# MT-PowerDispatch_V1_0_0.net
KiCad netlist of a schematic drawn in Altium Designer
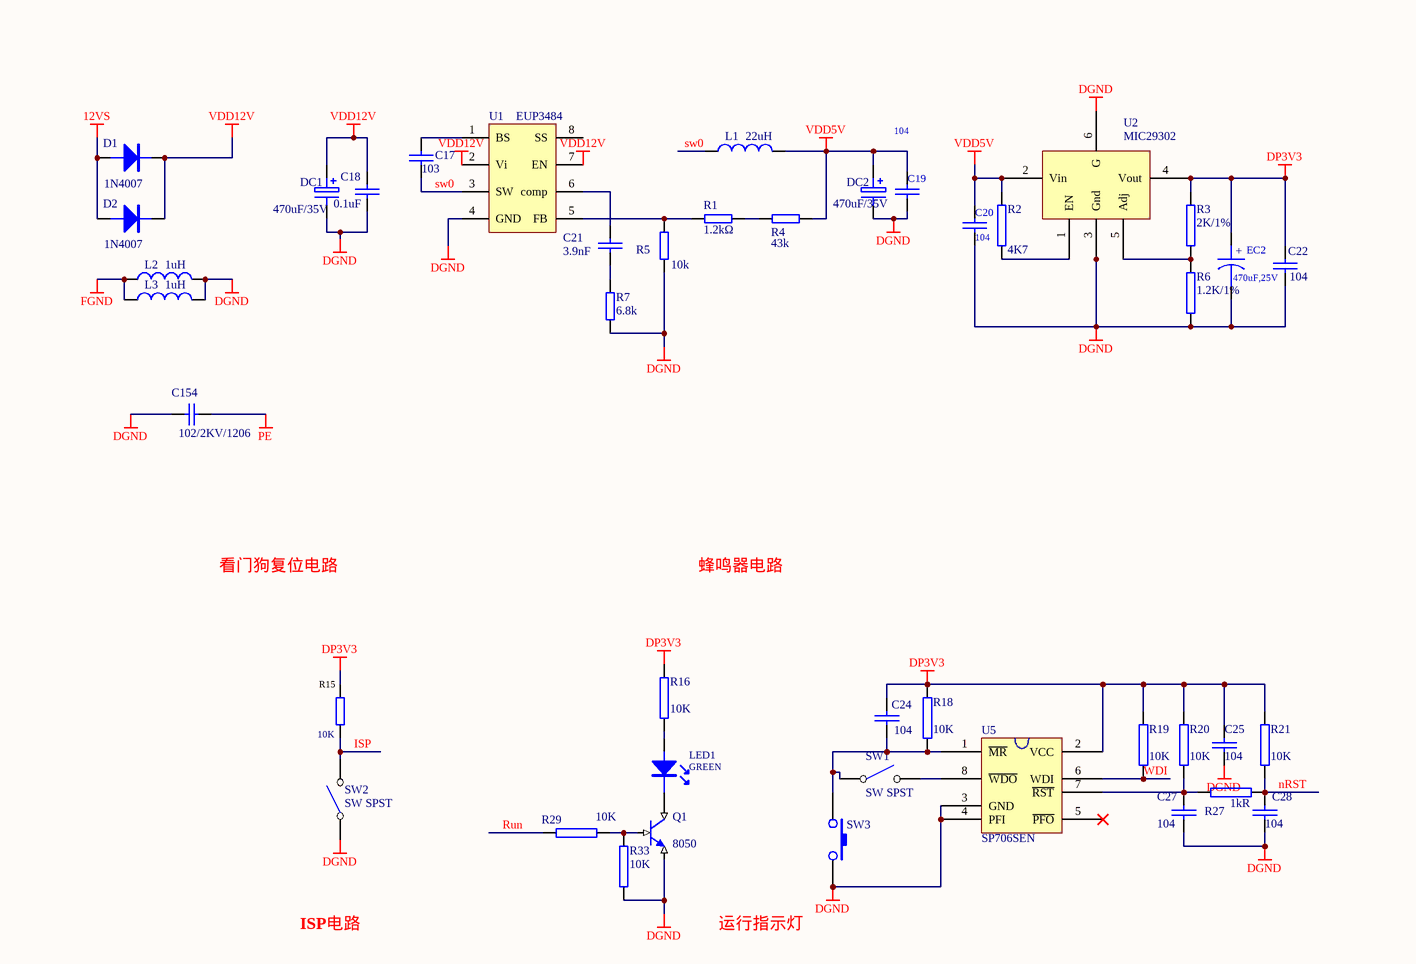
[diagram p0: MT-PowerDispatch V1.0.0.SchDoc, top left]
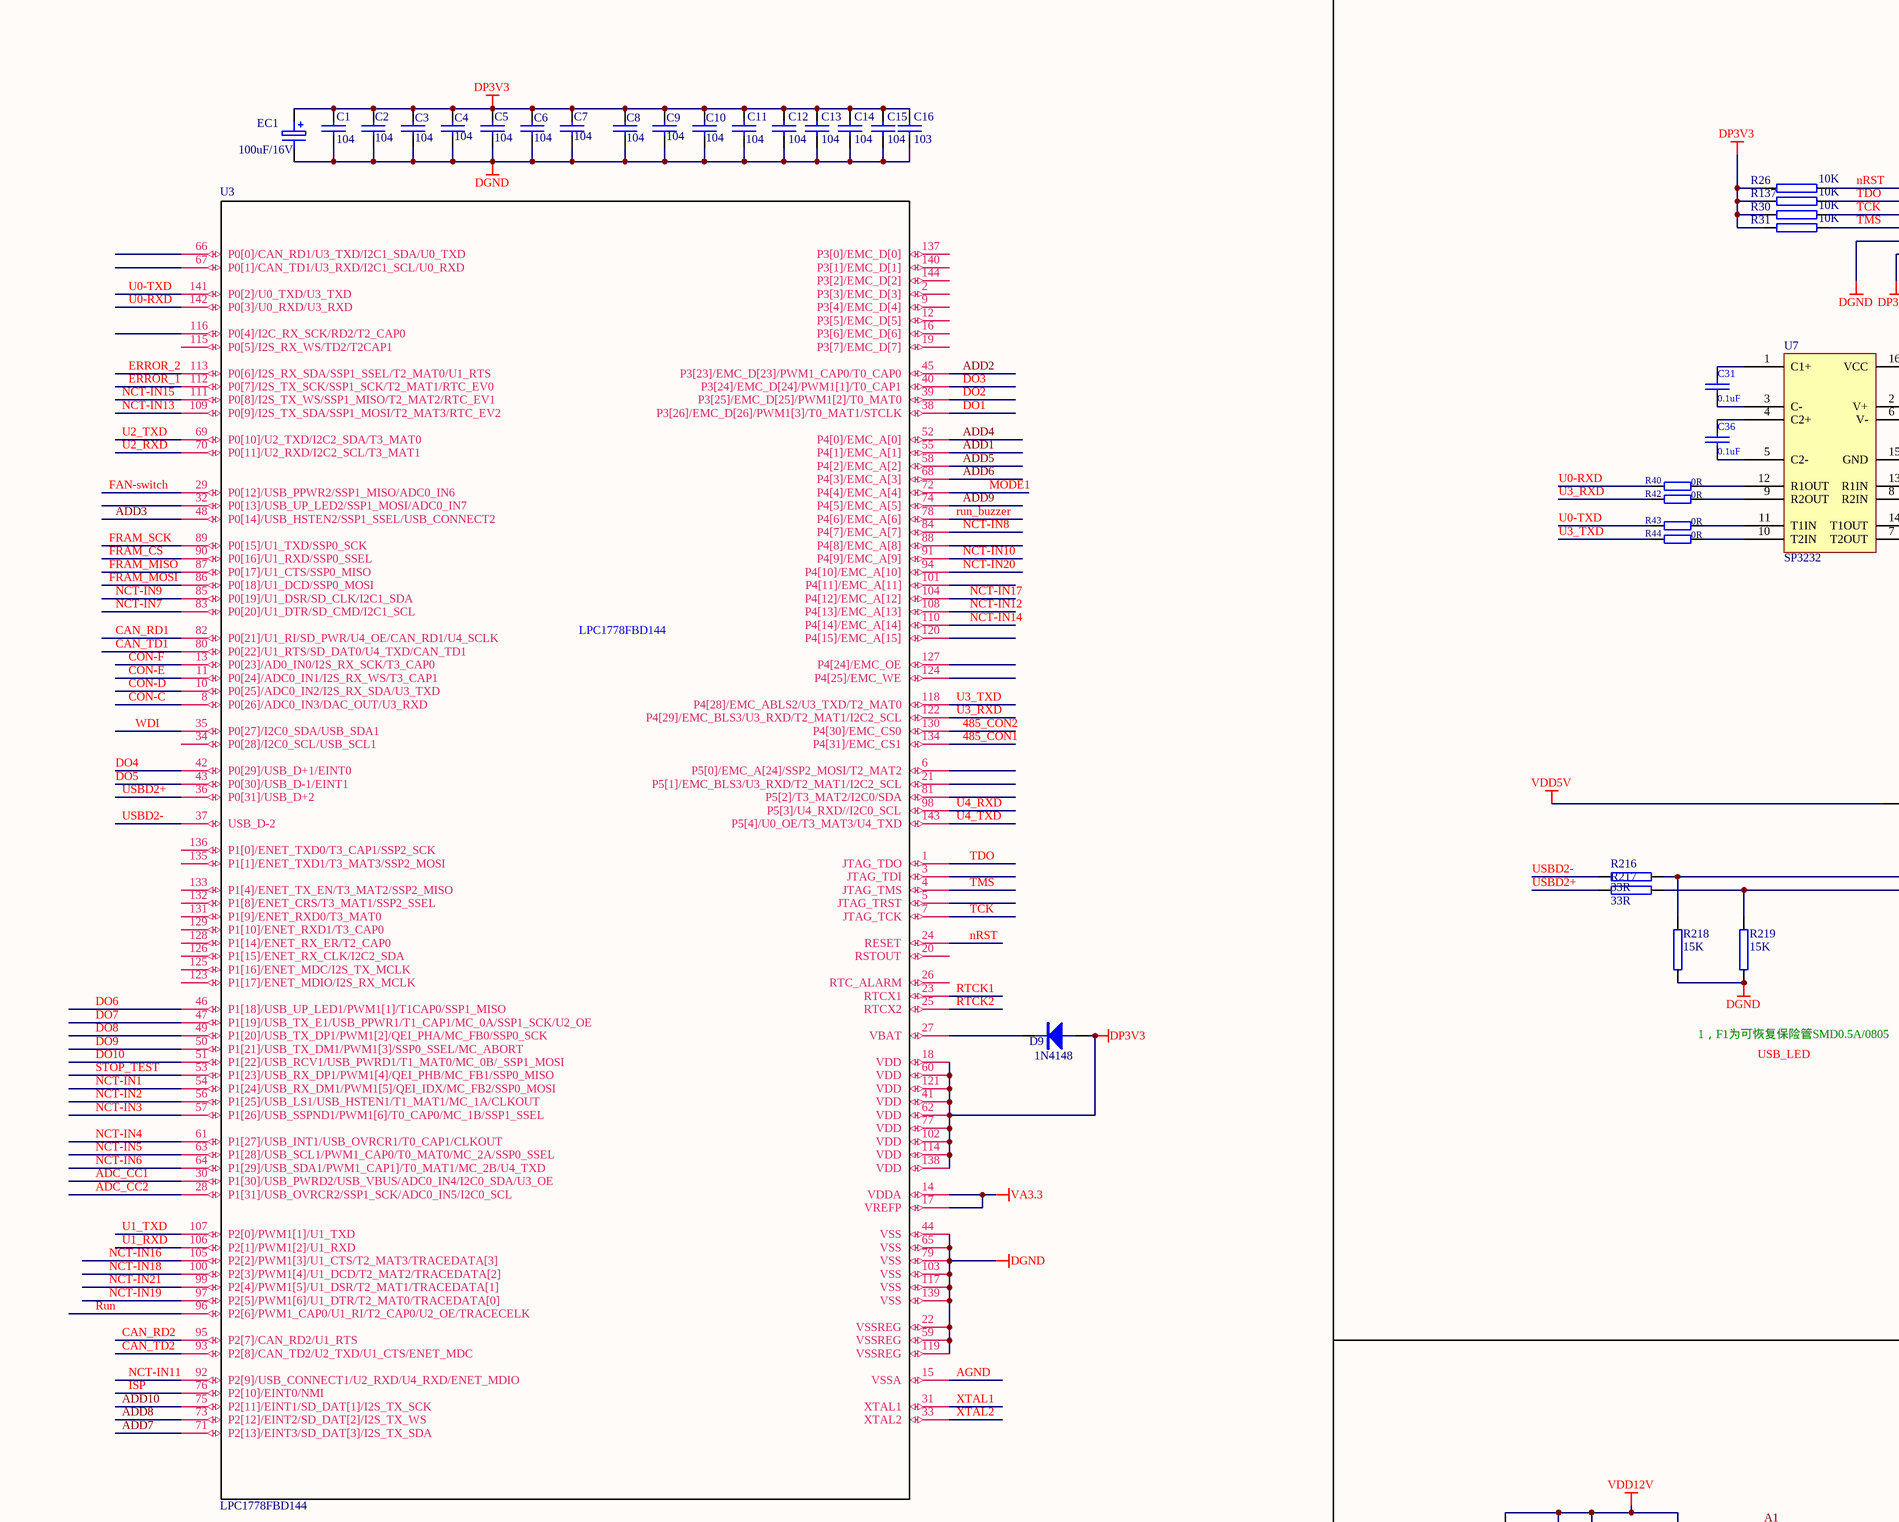
[diagram p1: MT-PowerDispatch V1.0.0.SchDoc, top middle]
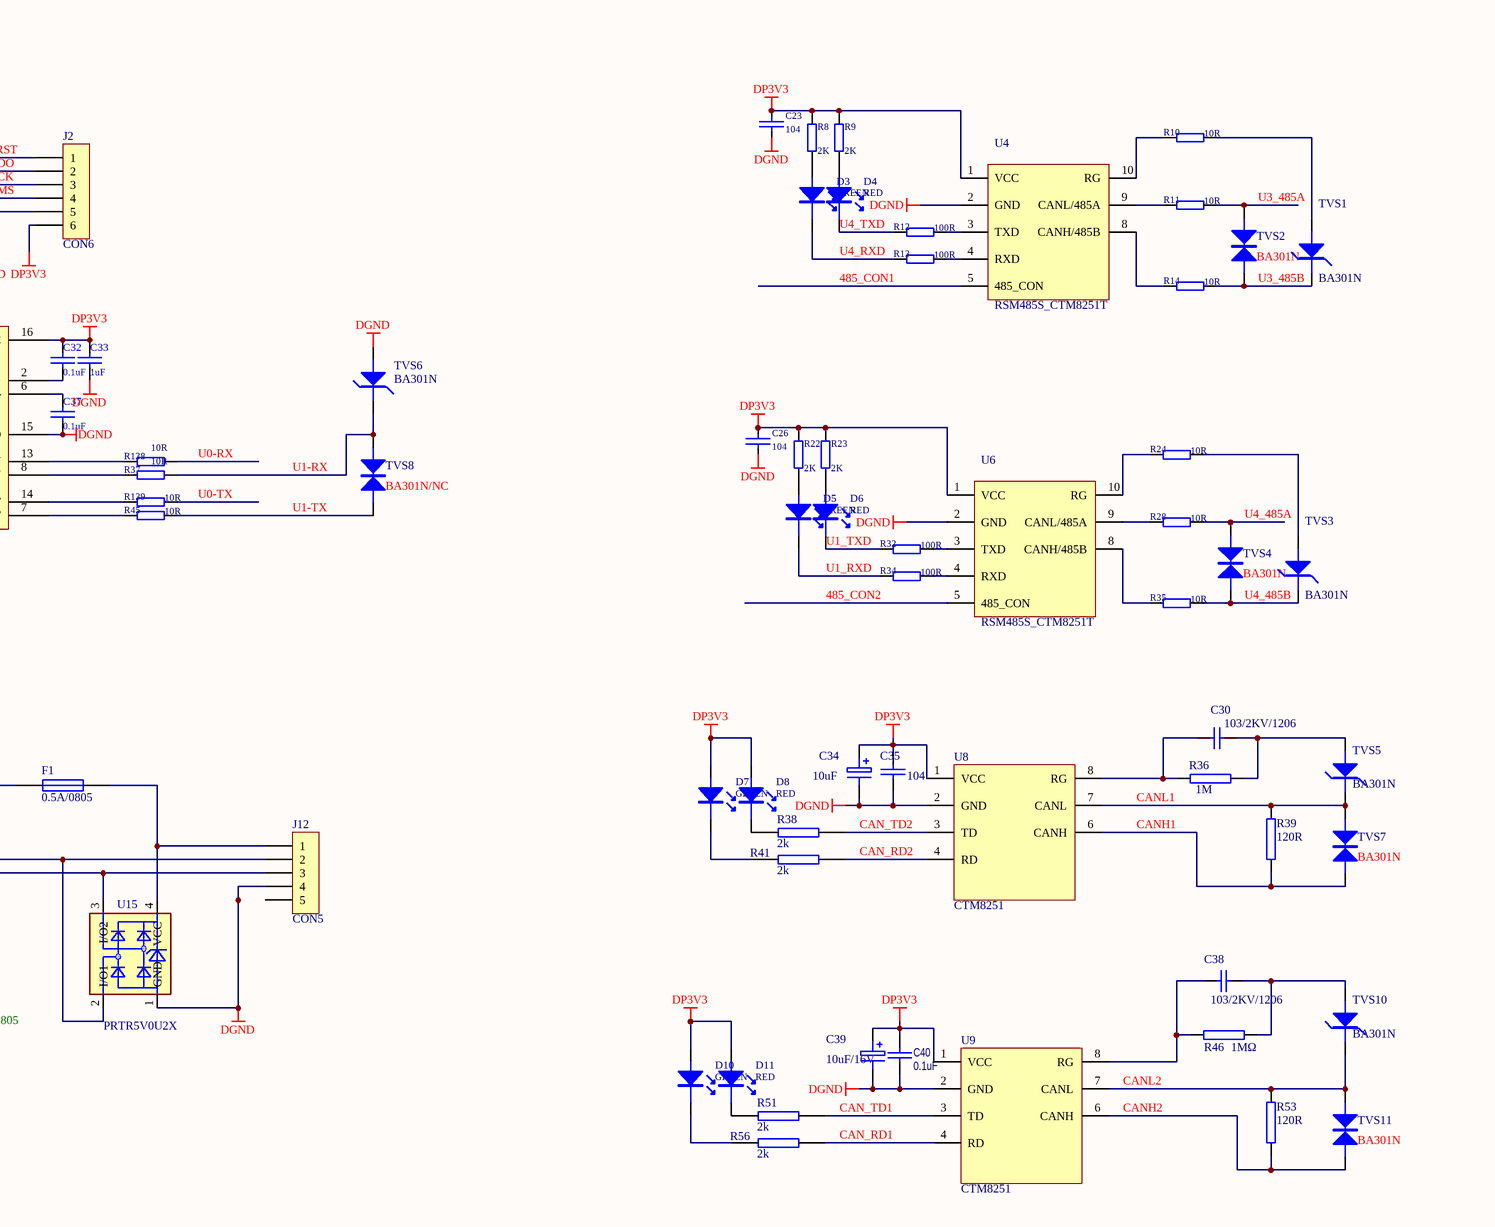
[diagram p2: MT-PowerDispatch V1.0.0.SchDoc, top right]
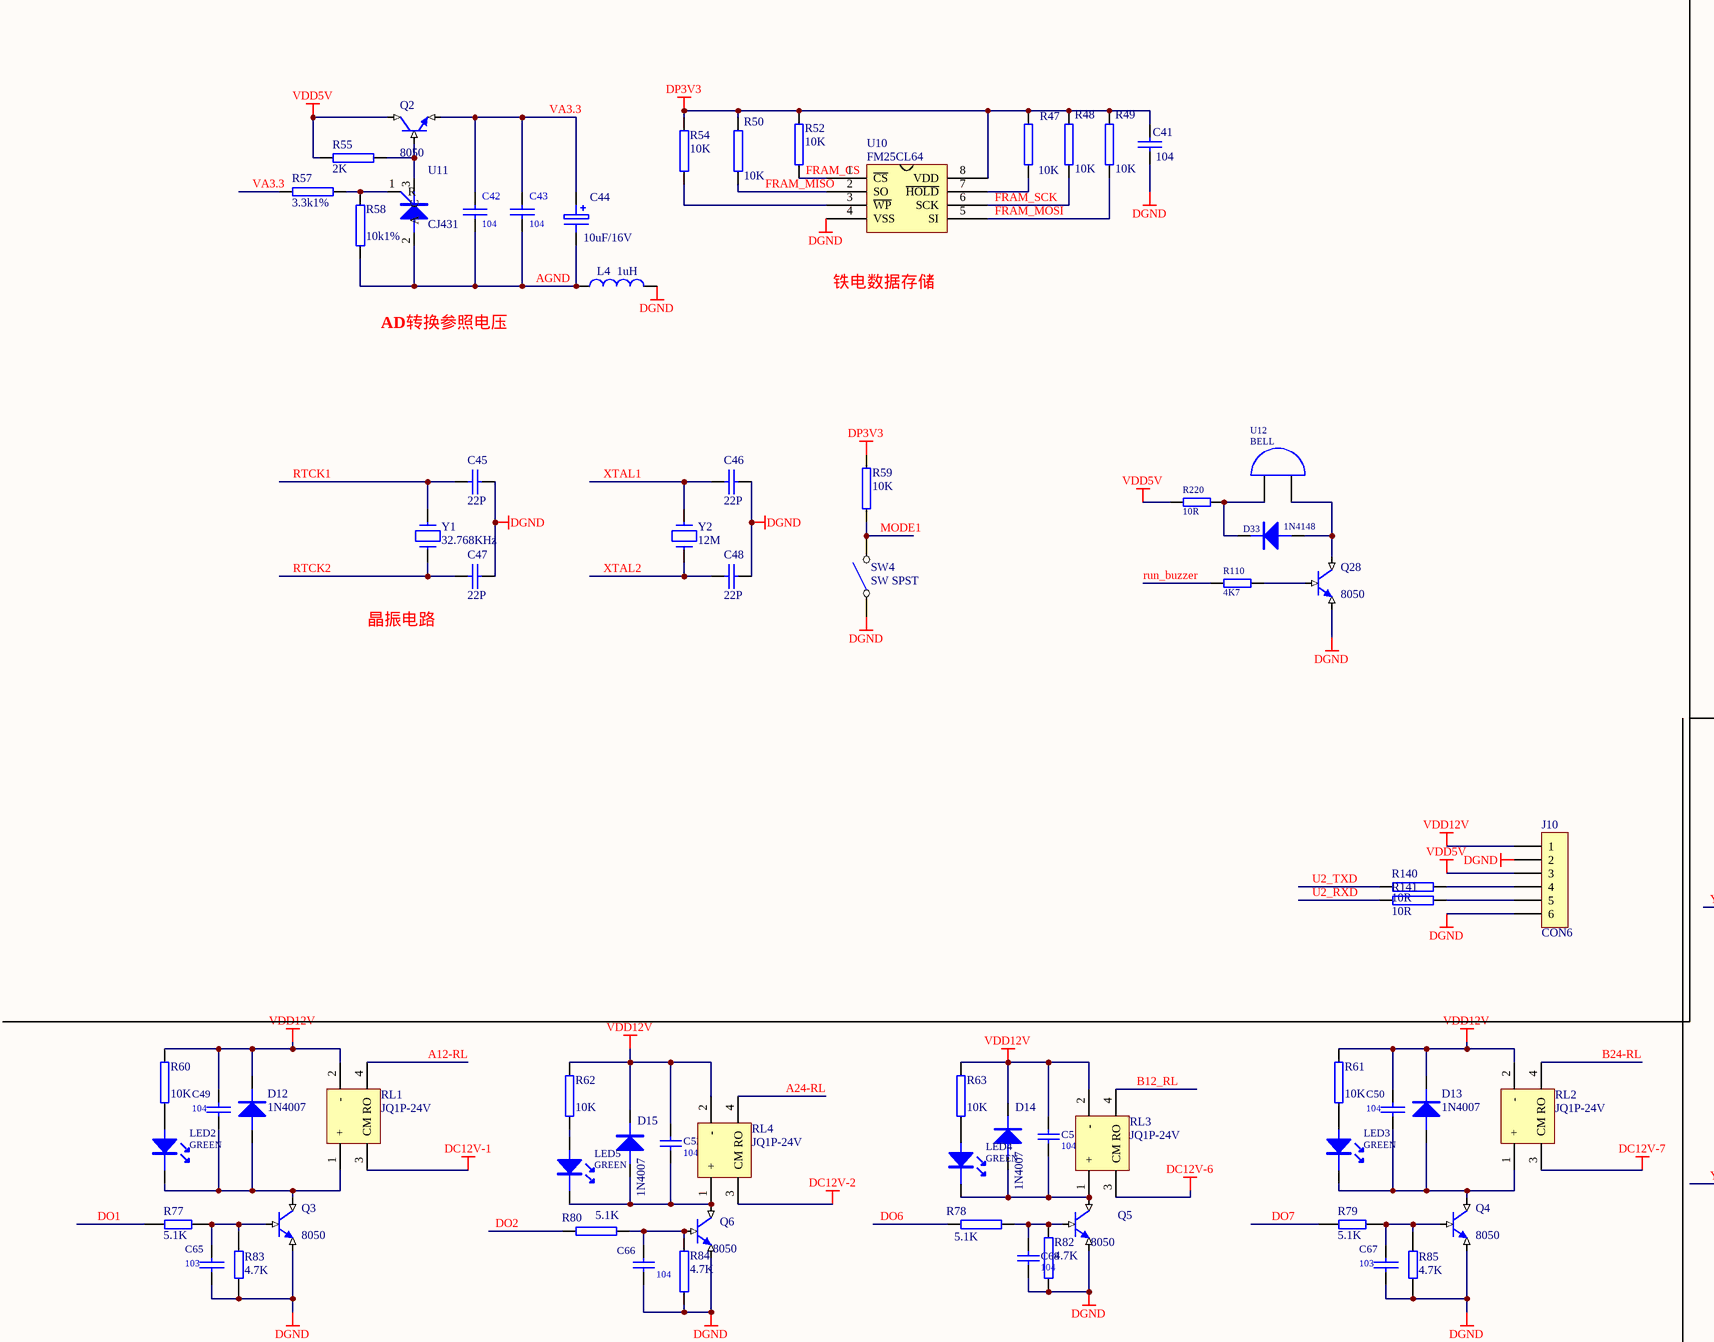
[diagram p3: MT-PowerDispatch V1.0.0.SchDoc, centre left]
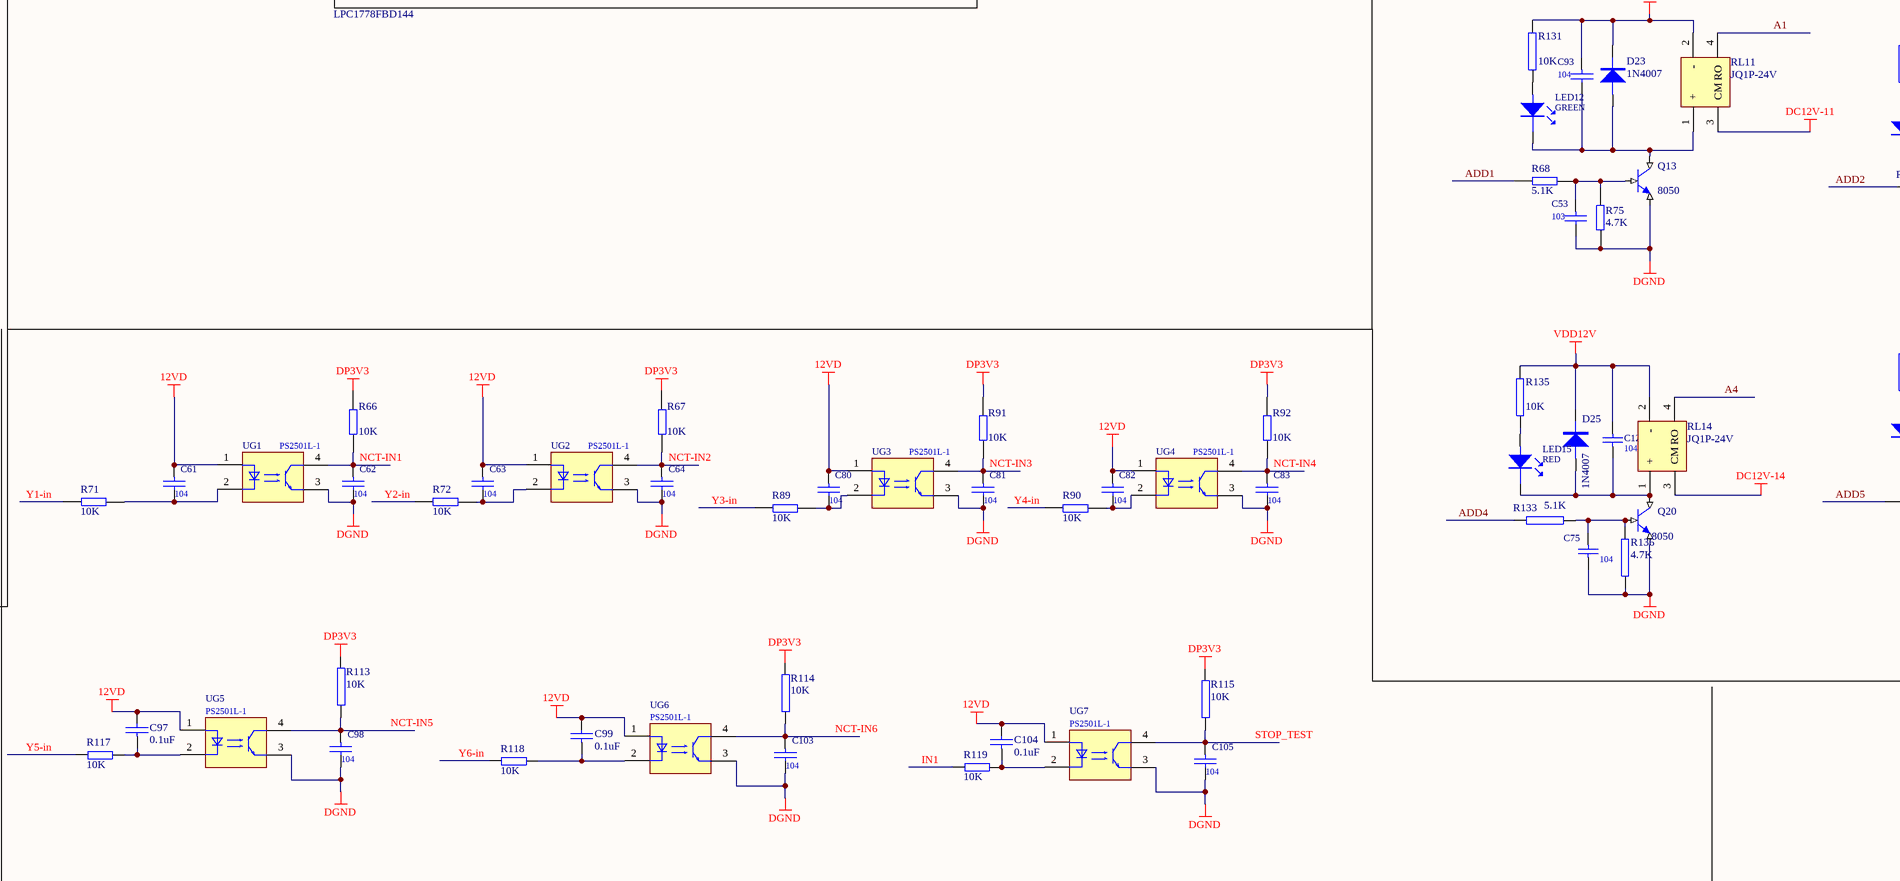
[diagram p4: MT-PowerDispatch V1.0.0.SchDoc, centre middle]
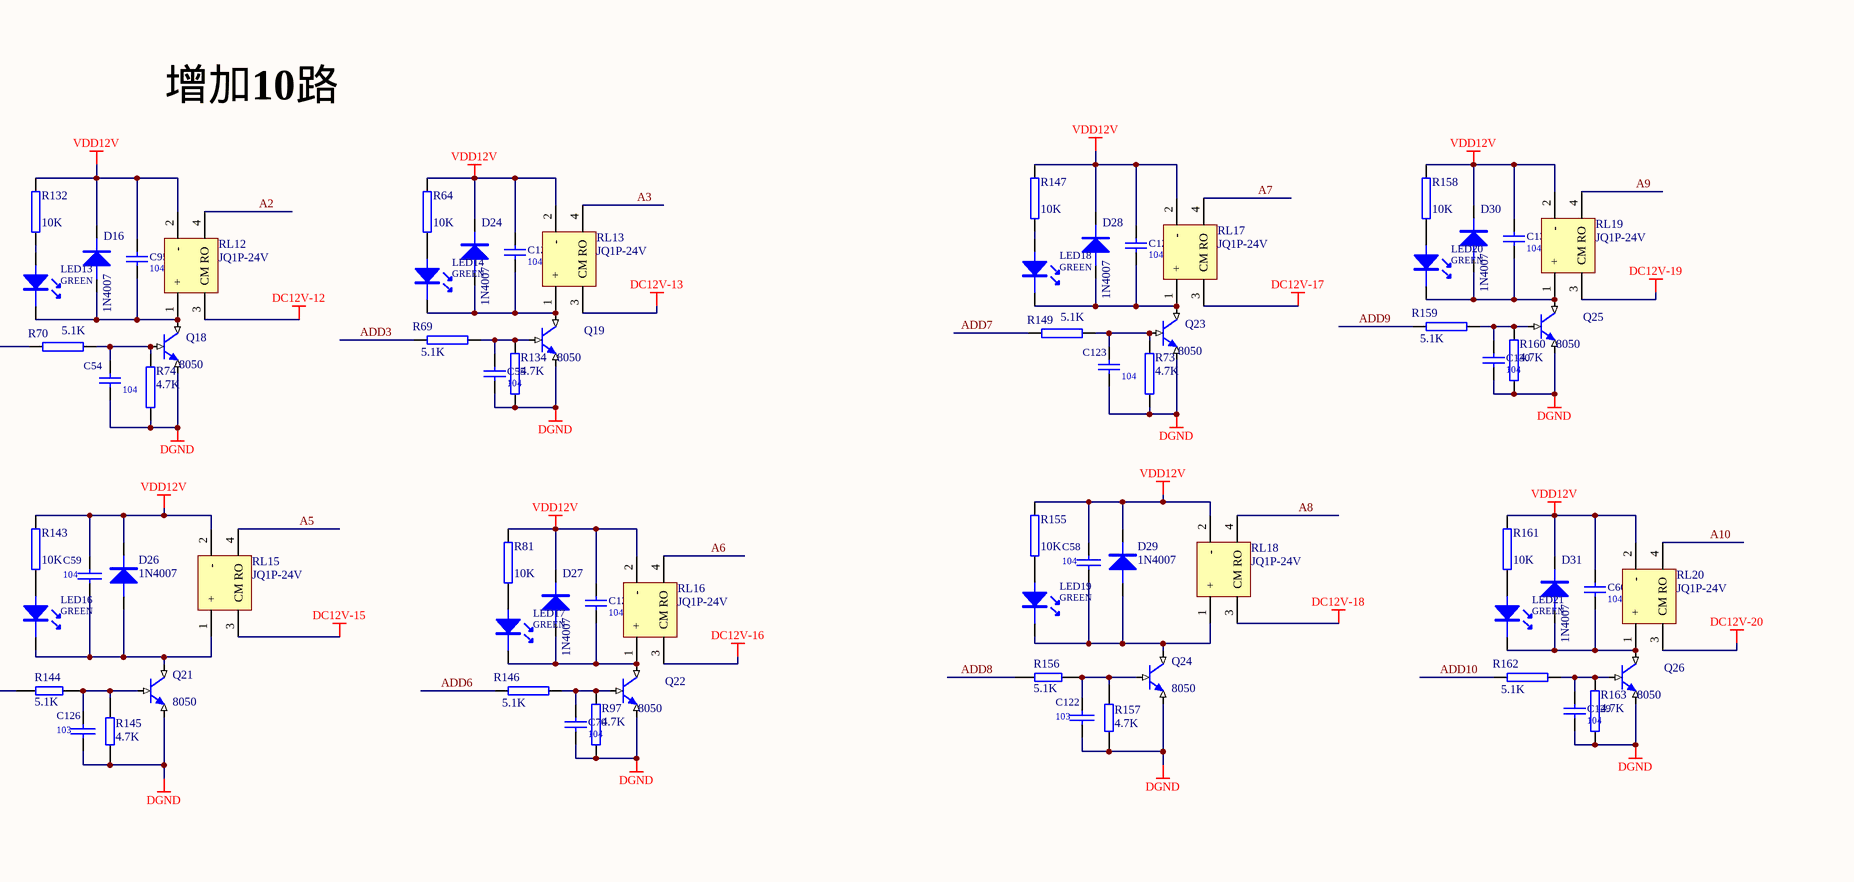
[diagram p5: MT-PowerDispatch V1.0.0.SchDoc, centre right]
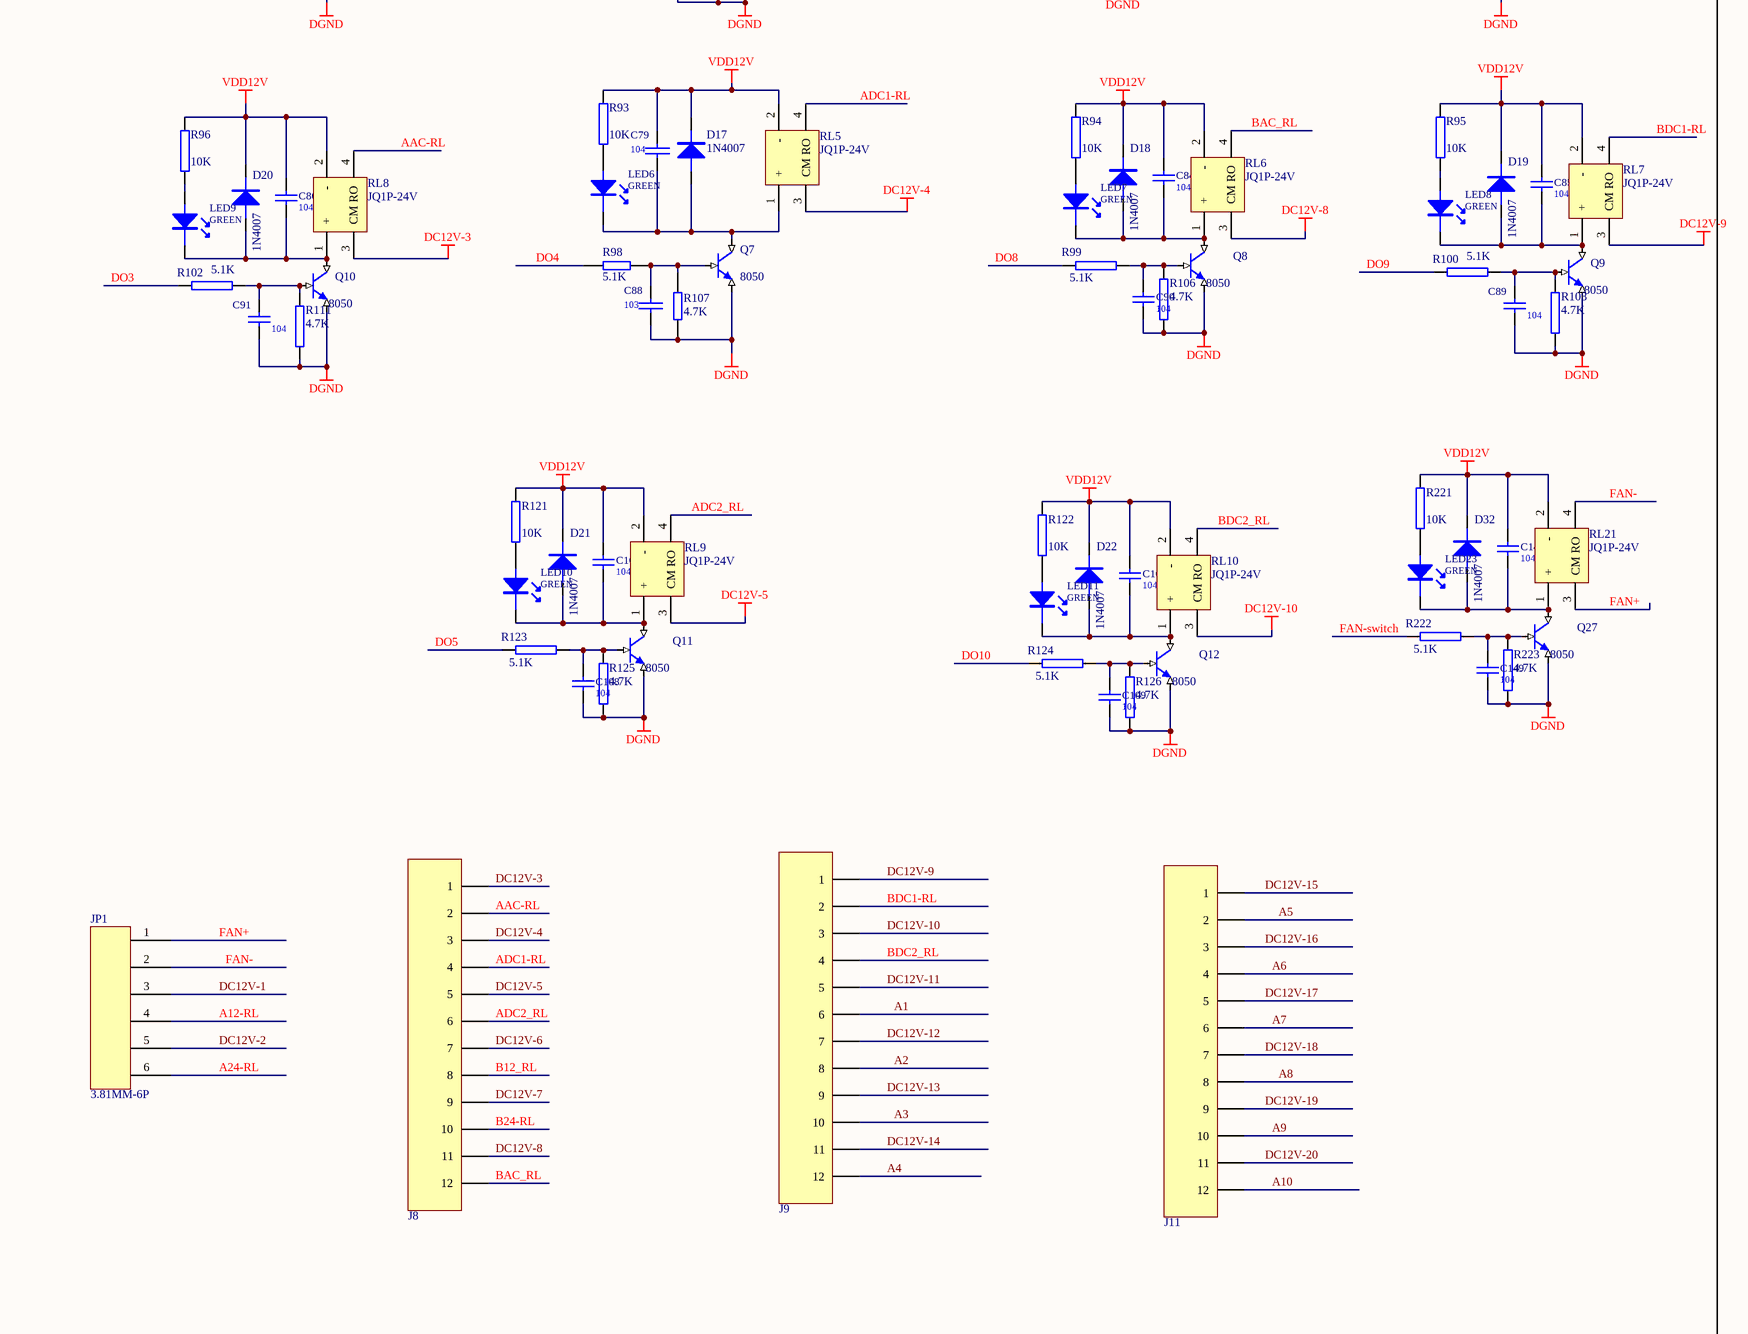
[diagram p6: MT-PowerDispatch V1.0.0.SchDoc, bottom left]
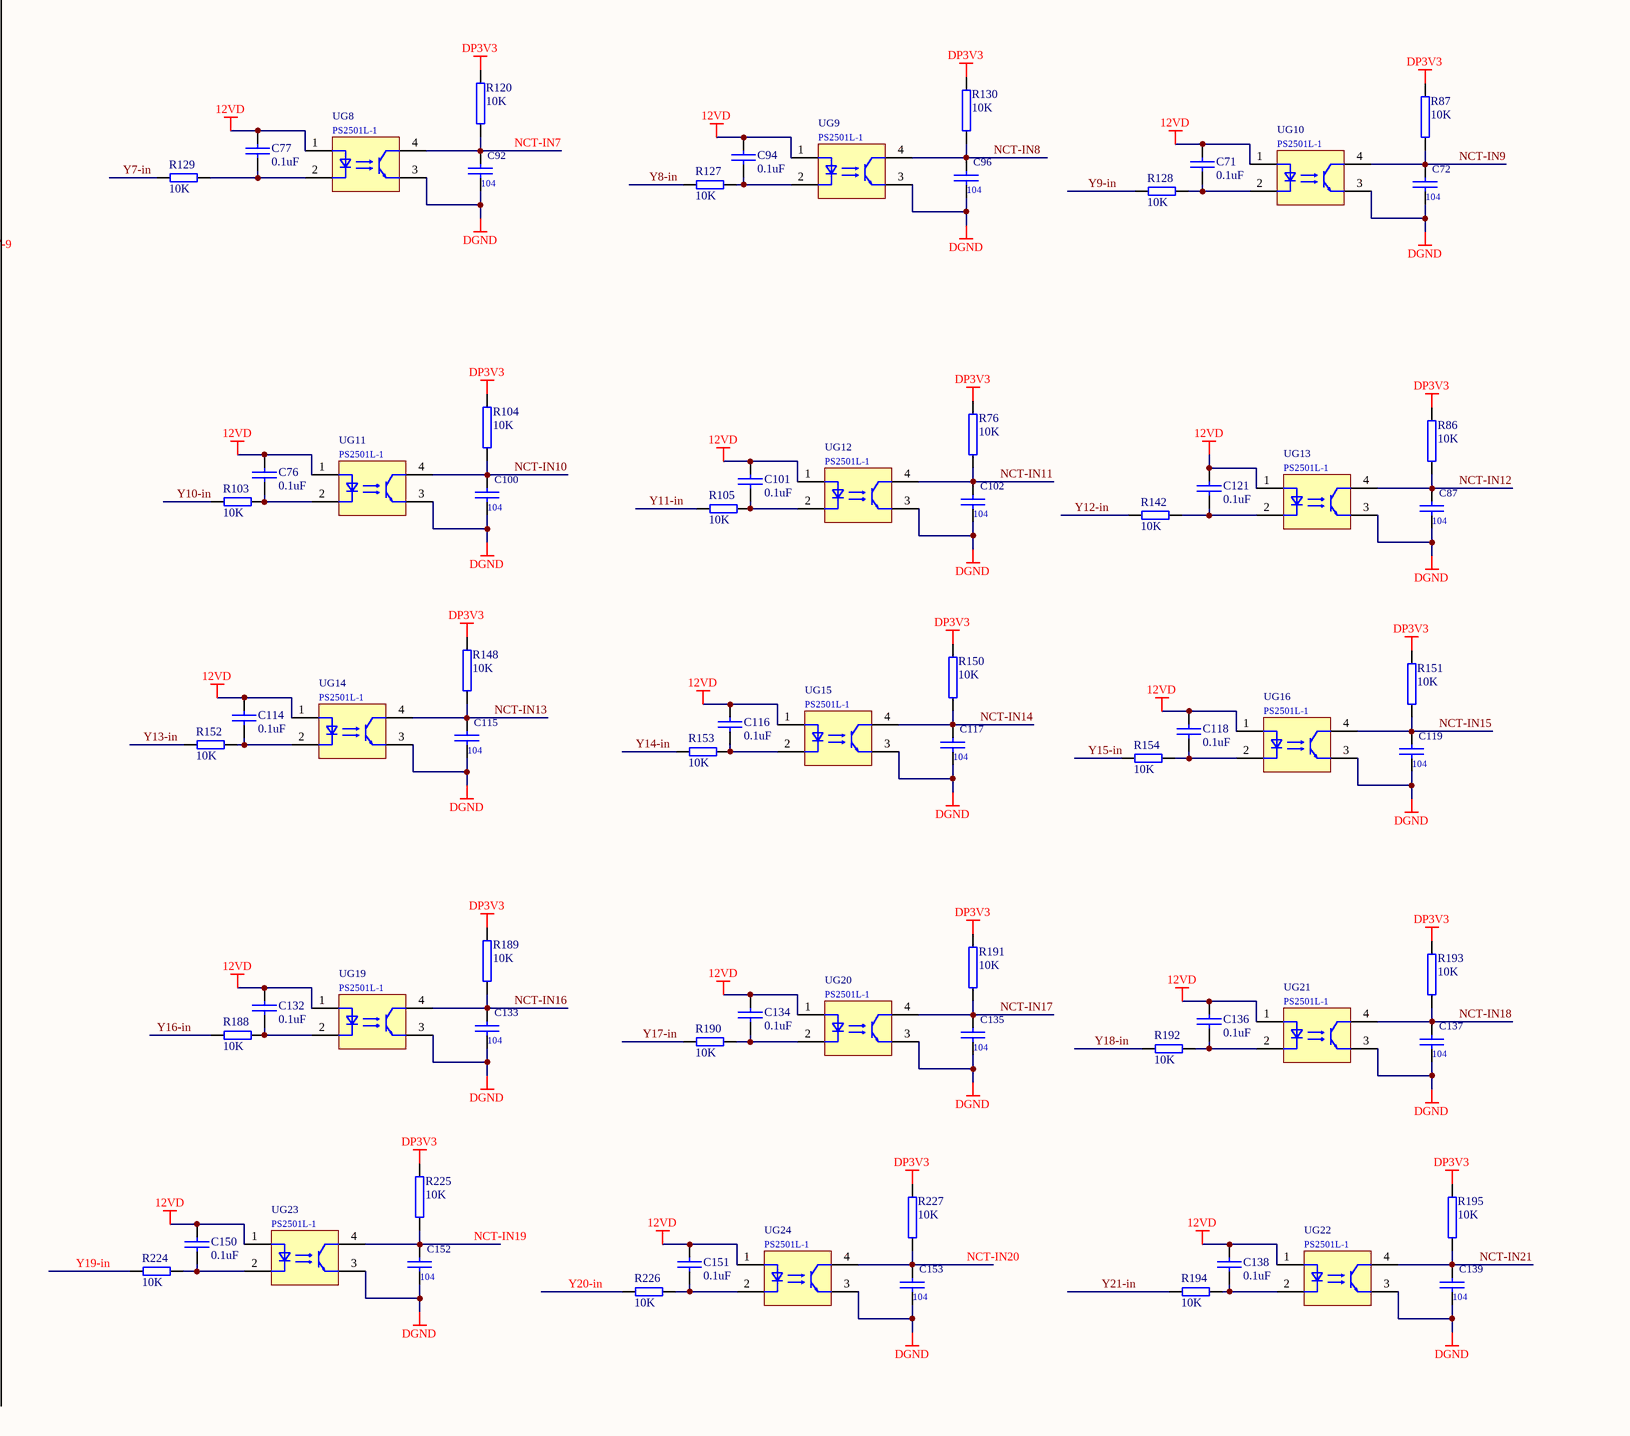
[diagram p7: MT-PowerDispatch V1.0.0.SchDoc, bottom middle]
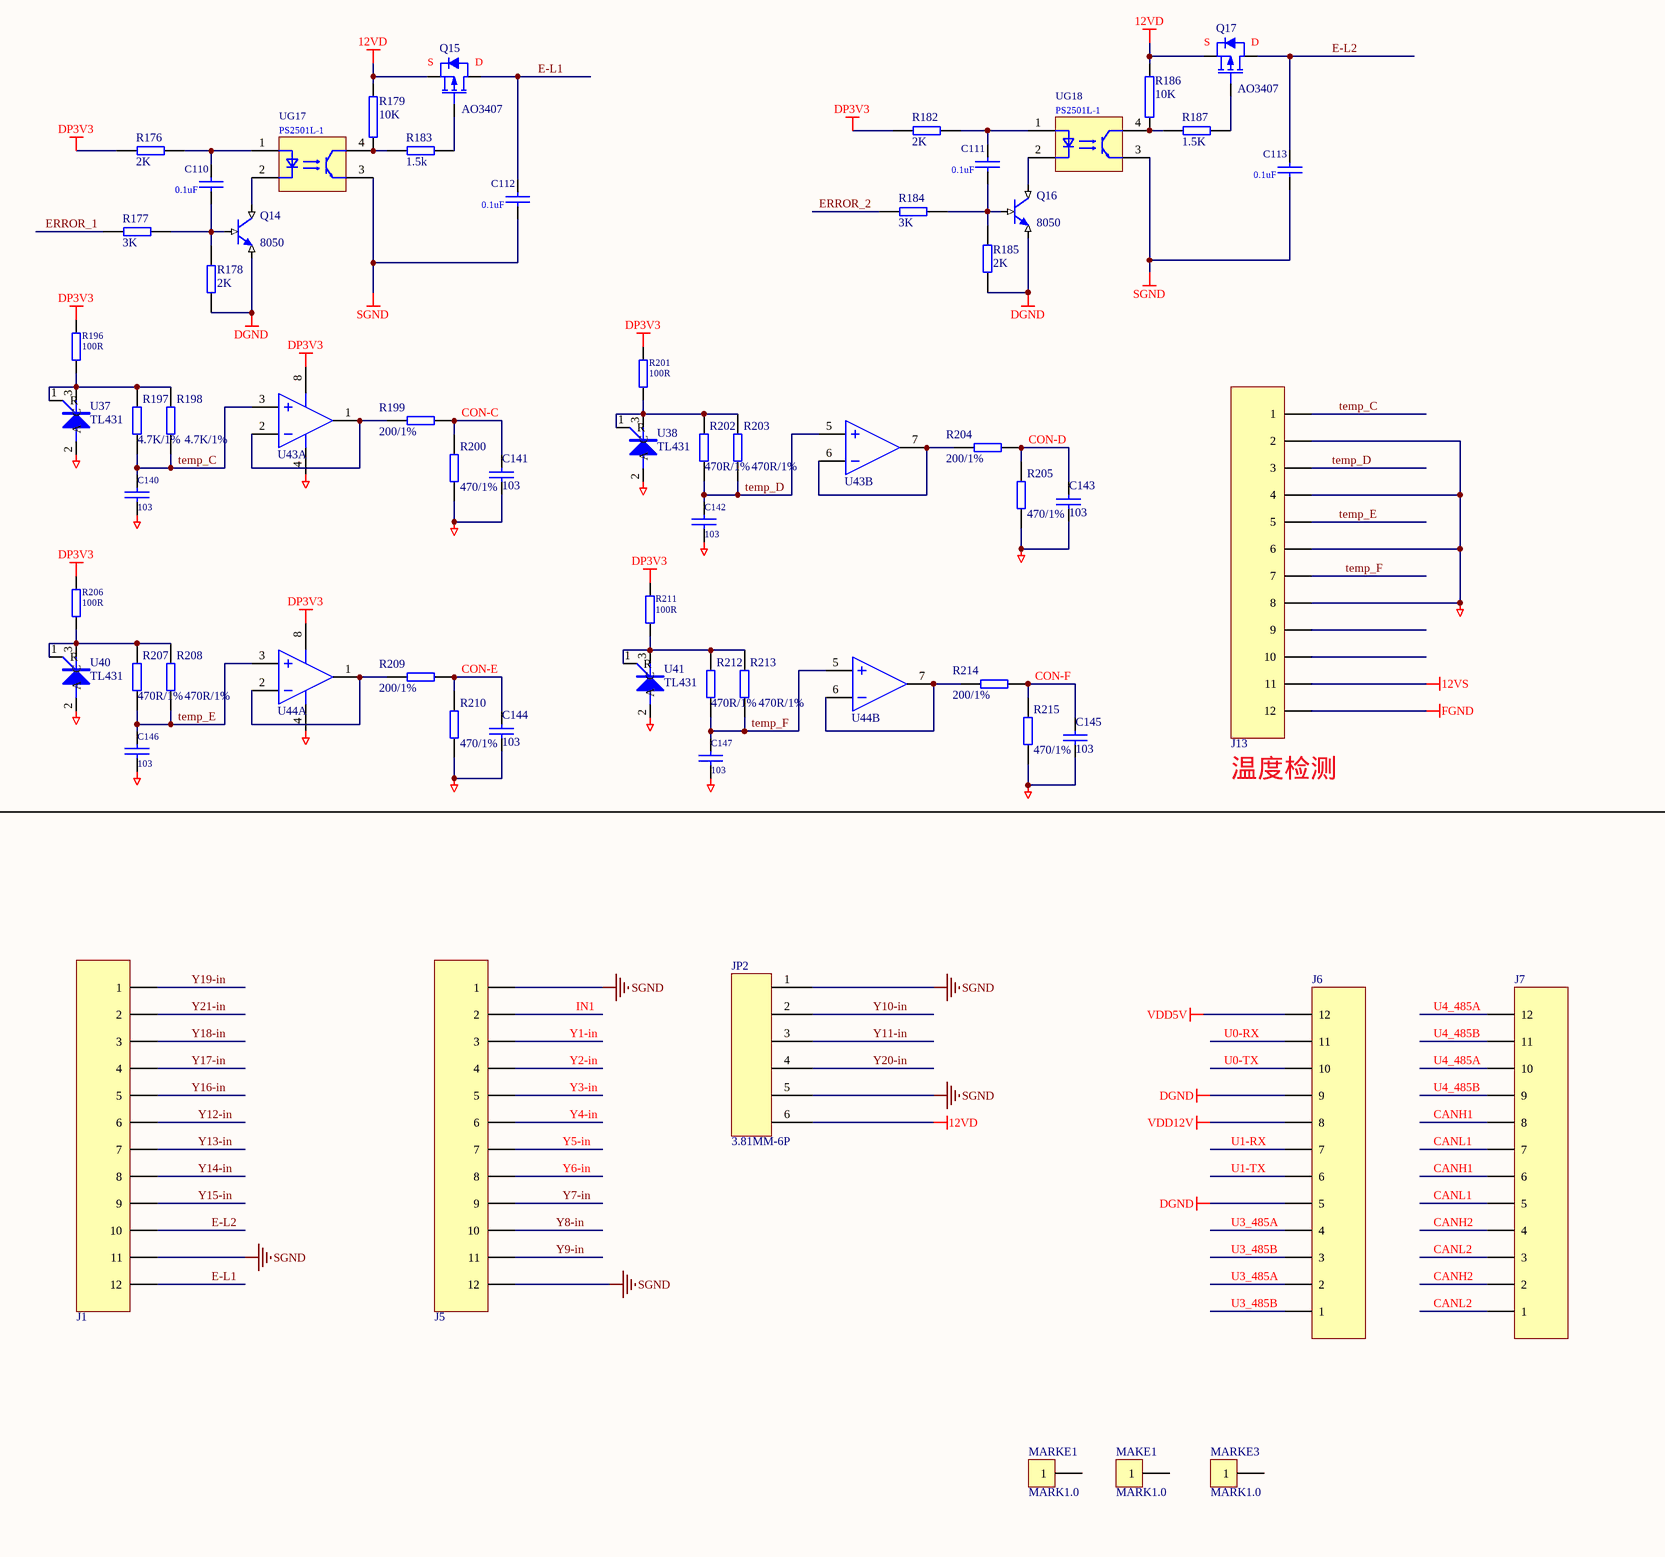
[diagram p8: MT-PowerDispatch V1.0.0.SchDoc, bottom right]

(export (version "E")
  (design (tool "Eeschema 10.0.6"))
  (components
    (comp (ref "C1") (value "104") (footprint "0603C") (libsource (lib "*") (part "CAP1")))
    (comp (ref "C2") (value "104") (footprint "0603C") (libsource (lib "*") (part "CAP1")))
    (comp (ref "C3") (value "104") (footprint "0603C") (libsource (lib "*") (part "CAP1")))
    (comp (ref "C4") (value "104") (footprint "0603C") (libsource (lib "*") (part "CAP1")))
    (comp (ref "C5") (value "104") (footprint "0603C") (libsource (lib "*") (part "CAP1")))
    (comp (ref "C6") (value "104") (footprint "0603C") (libsource (lib "*") (part "CAP1")))
    (comp (ref "C7") (value "104") (footprint "0603C") (libsource (lib "*") (part "CAP1")))
    (comp (ref "C8") (value "104") (footprint "0603C") (libsource (lib "*") (part "CAP1")))
    (comp (ref "C9") (value "104") (footprint "0603C") (libsource (lib "*") (part "CAP1")))
    (comp (ref "C10") (value "104") (footprint "0603C") (libsource (lib "*") (part "CAP1")))
    (comp (ref "C11") (value "104") (footprint "0603C") (libsource (lib "*") (part "CAP1")))
    (comp (ref "C12") (value "104") (footprint "0603C") (libsource (lib "") (part "CAP1_2")))
    (comp (ref "C13") (value "104") (footprint "0603C") (libsource (lib "*") (part "CAP1")))
    (comp (ref "C14") (value "104") (footprint "0603C") (libsource (lib "*") (part "CAP1")))
    (comp (ref "C15") (value "104") (footprint "0603C") (libsource (lib "*") (part "CAP1")))
    (comp (ref "C16") (value "103") (footprint "0603C") (libsource (lib "*") (part "CAP1")))
    (comp (ref "C17") (value "103") (footprint "0603C") (libsource (lib "") (part "CAP_1")))
    (comp (ref "C18") (value "0.1uF") (footprint "0805C") (libsource (lib "") (part "CAP_1")))
    (comp (ref "C19")
      (value "104")
      (footprint "0603C")
      (description "Capacitor")
      (libsource (lib "") (part "CAP_1"))
    )
    (comp (ref "C20")
      (value "104")
      (footprint "0603C")
      (description "Capacitor")
      (libsource (lib "") (part "CAP_1"))
    )
    (comp (ref "C21") (value "3.9nF") (footprint "0603C") (libsource (lib "") (part "CAP_1")))
    (comp (ref "C22")
      (value "104")
      (footprint "0603C")
      (description "CAP")
      (libsource (lib "*") (part "CAP1"))
    )
    (comp (ref "C23") (value "104") (footprint "0603C") (libsource (lib "*") (part "CAP_1")))
    (comp (ref "C24")
      (value "104")
      (footprint "0603C")
      (description "CAP")
      (libsource (lib "*") (part "CAP1"))
    )
    (comp (ref "C25")
      (value "104")
      (footprint "0603C")
      (description "CAP")
      (libsource (lib "*") (part "CAP1"))
    )
    (comp (ref "C26") (value "104") (footprint "0603C") (libsource (lib "*") (part "CAP_1")))
    (comp (ref "C27")
      (value "104")
      (footprint "0603C")
      (description "CAP")
      (libsource (lib "*") (part "CAP1"))
    )
    (comp (ref "C28")
      (value "104")
      (footprint "0603C")
      (description "CAP")
      (libsource (lib "*") (part "CAP1"))
    )
    (comp (ref "C30")
      (value "103/2KV/1206")
      (footprint "1206C")
      (description "C0603")
      (fields (field (name "PUBLISHER") "*"))
      (libsource (lib "*") (part "0.1uF"))
    )
    (comp (ref "C31")
      (value "0.1uF")
      (footprint "0603C")
      (description "Capacitor")
      (libsource (lib "") (part "CAP_1"))
    )
    (comp (ref "C32")
      (value "0.1uF")
      (footprint "0603C")
      (description "Capacitor")
      (libsource (lib "") (part "CAP_1"))
    )
    (comp (ref "C33")
      (value "1uF")
      (footprint "0603C")
      (description "Capacitor")
      (libsource (lib "") (part "CAP_1"))
    )
    (comp (ref "C34") (value "10uF") (footprint "CA1206") (libsource (lib "*") (part "CAP2")))
    (comp (ref "C35")
      (value "104")
      (footprint "0603C")
      (description "Capacitor")
      (libsource (lib "") (part "CAP_1"))
    )
    (comp (ref "C36")
      (value "0.1uF")
      (footprint "0603C")
      (description "Capacitor")
      (libsource (lib "") (part "CAP_1"))
    )
    (comp (ref "C37")
      (value "0.1uF")
      (footprint "0603C")
      (description "Capacitor")
      (libsource (lib "") (part "CAP_1"))
    )
    (comp (ref "C38")
      (value "103/2KV/1206")
      (footprint "1206C")
      (description "C0603")
      (fields (field (name "PUBLISHER") "*"))
      (libsource (lib "*") (part "0.1uF"))
    )
    (comp (ref "C39") (value "10uF/16V") (footprint "CA1206") (libsource (lib "*") (part "CAP2")))
    (comp (ref "C40")
      (value "0.1uF")
      (footprint "0603C")
      (description "Capacitor")
      (libsource (lib "") (part "CAP_1"))
    )
    (comp (ref "C41") (value "104") (footprint "0603C") (libsource (lib "*") (part "CAP1")))
    (comp (ref "C42")
      (value "104")
      (footprint "0603C")
      (description "Capacitor")
      (libsource (lib "") (part "CAP_1"))
    )
    (comp (ref "C43")
      (value "104")
      (footprint "0603C")
      (description "Capacitor")
      (libsource (lib "") (part "CAP_1"))
    )
    (comp (ref "C44") (value "10uF/16V") (footprint "CA1206") (libsource (lib "*") (part "CAP2")))
    (comp (ref "C45") (value "22P") (footprint "0603C") (libsource (lib "*") (part "CAP1")))
    (comp (ref "C46") (value "22P") (footprint "0603C") (libsource (lib "*") (part "CAP1")))
    (comp (ref "C47") (value "22P") (footprint "0603C") (libsource (lib "*") (part "CAP1")))
    (comp (ref "C48") (value "22P") (footprint "0603C") (libsource (lib "*") (part "CAP1")))
    (comp (ref "C49")
      (value "104")
      (footprint "0603C")
      (description "Capacitor")
      (libsource (lib "") (part "CAP_1"))
    )
    (comp (ref "C50")
      (value "104")
      (footprint "0603C")
      (description "Capacitor")
      (libsource (lib "") (part "CAP_1"))
    )
    (comp (ref "C51")
      (value "104")
      (footprint "0603C")
      (description "Capacitor")
      (fields (field (name "PUBLISHER") "*"))
      (libsource (lib "*") (part "Cap"))
    )
    (comp (ref "C52")
      (value "104")
      (footprint "0603C")
      (description "Capacitor")
      (fields (field (name "PUBLISHER") "*"))
      (libsource (lib "*") (part "Cap"))
    )
    (comp (ref "C53")
      (value "103")
      (footprint "0603C")
      (description "Capacitor")
      (libsource (lib "") (part "CAP_1"))
    )
    (comp (ref "C54")
      (value "104")
      (footprint "0603C")
      (description "Capacitor")
      (fields (field (name "PUBLISHER") "*"))
      (libsource (lib "*") (part "Cap"))
    )
    (comp (ref "C55")
      (value "104")
      (footprint "0603C")
      (description "Capacitor")
      (fields (field (name "PUBLISHER") "*"))
      (libsource (lib "*") (part "Cap"))
    )
    (comp (ref "C58")
      (value "104")
      (footprint "0603C")
      (description "Capacitor")
      (libsource (lib "") (part "CAP_1"))
    )
    (comp (ref "C59")
      (value "104")
      (footprint "0603C")
      (description "Capacitor")
      (libsource (lib "") (part "CAP_1"))
    )
    (comp (ref "C60")
      (value "104")
      (footprint "0603C")
      (description "Capacitor")
      (fields (field (name "PUBLISHER") "*"))
      (libsource (lib "*") (part "Cap"))
    )
    (comp (ref "C61")
      (value "104")
      (footprint "0603C")
      (description "Capacitor")
      (libsource (lib "") (part "CAP_1"))
    )
    (comp (ref "C62")
      (value "104")
      (footprint "0603C")
      (description "Capacitor")
      (libsource (lib "") (part "CAP_1"))
    )
    (comp (ref "C63")
      (value "104")
      (footprint "0603C")
      (description "Capacitor")
      (libsource (lib "") (part "CAP_1"))
    )
    (comp (ref "C64")
      (value "104")
      (footprint "0603C")
      (description "Capacitor")
      (libsource (lib "") (part "CAP_1"))
    )
    (comp (ref "C65")
      (value "103")
      (footprint "0603C")
      (description "Capacitor")
      (libsource (lib "") (part "CAP_1"))
    )
    (comp (ref "C66")
      (value "104")
      (footprint "0603C")
      (description "Capacitor")
      (fields (field (name "PUBLISHER") "*"))
      (libsource (lib "*") (part "Cap"))
    )
    (comp (ref "C67")
      (value "103")
      (footprint "0603C")
      (description "Capacitor")
      (libsource (lib "") (part "CAP_1"))
    )
    (comp (ref "C68")
      (value "104")
      (footprint "0603C")
      (description "Capacitor")
      (fields (field (name "PUBLISHER") "*"))
      (libsource (lib "*") (part "Cap"))
    )
    (comp (ref "C70")
      (value "104")
      (footprint "0603C")
      (description "Capacitor")
      (fields (field (name "PUBLISHER") "*"))
      (libsource (lib "*") (part "Cap"))
    )
    (comp (ref "C71")
      (value "0.1uF")
      (footprint "0603C")
      (description "Capacitor")
      (libsource (lib "") (part "CAP_1"))
    )
    (comp (ref "C72")
      (value "104")
      (footprint "0603C")
      (description "Capacitor")
      (libsource (lib "") (part "CAP_1"))
    )
    (comp (ref "C75")
      (value "104")
      (footprint "0603C")
      (description "Capacitor")
      (fields (field (name "PUBLISHER") "*"))
      (libsource (lib "*") (part "Cap"))
    )
    (comp (ref "C76")
      (value "0.1uF")
      (footprint "0603C")
      (description "Capacitor")
      (libsource (lib "") (part "CAP_1"))
    )
    (comp (ref "C77")
      (value "0.1uF")
      (footprint "0603C")
      (description "Capacitor")
      (libsource (lib "") (part "CAP_1"))
    )
    (comp (ref "C79")
      (value "104")
      (footprint "0603C")
      (description "Capacitor")
      (libsource (lib "") (part "CAP_1"))
    )
    (comp (ref "C80")
      (value "104")
      (footprint "0603C")
      (description "Capacitor")
      (libsource (lib "") (part "CAP_1"))
    )
    (comp (ref "C81")
      (value "104")
      (footprint "0603C")
      (description "Capacitor")
      (libsource (lib "") (part "CAP_1"))
    )
    (comp (ref "C82")
      (value "104")
      (footprint "0603C")
      (description "Capacitor")
      (libsource (lib "") (part "CAP_1"))
    )
    (comp (ref "C83")
      (value "104")
      (footprint "0603C")
      (description "Capacitor")
      (libsource (lib "") (part "CAP_1"))
    )
    (comp (ref "C84")
      (value "104")
      (footprint "0603C")
      (description "Capacitor")
      (fields (field (name "PUBLISHER") "*"))
      (libsource (lib "*") (part "Cap"))
    )
    (comp (ref "C85")
      (value "104")
      (footprint "0603C")
      (description "Capacitor")
      (fields (field (name "PUBLISHER") "*"))
      (libsource (lib "*") (part "Cap"))
    )
    (comp (ref "C86")
      (value "104")
      (footprint "0603C")
      (description "Capacitor")
      (fields (field (name "PUBLISHER") "*"))
      (libsource (lib "*") (part "Cap"))
    )
    (comp (ref "C87")
      (value "104")
      (footprint "0603C")
      (description "Capacitor")
      (libsource (lib "") (part "CAP_1"))
    )
    (comp (ref "C88")
      (value "103")
      (footprint "0603C")
      (description "Capacitor")
      (libsource (lib "") (part "CAP_1"))
    )
    (comp (ref "C89")
      (value "104")
      (footprint "0603C")
      (description "Capacitor")
      (fields (field (name "PUBLISHER") "*"))
      (libsource (lib "*") (part "Cap"))
    )
    (comp (ref "C90")
      (value "104")
      (footprint "0603C")
      (description "Capacitor")
      (fields (field (name "PUBLISHER") "*"))
      (libsource (lib "*") (part "Cap"))
    )
    (comp (ref "C91")
      (value "104")
      (footprint "0603C")
      (description "Capacitor")
      (fields (field (name "PUBLISHER") "*"))
      (libsource (lib "*") (part "Cap"))
    )
    (comp (ref "C92")
      (value "104")
      (footprint "0603C")
      (description "Capacitor")
      (libsource (lib "") (part "CAP_1"))
    )
    (comp (ref "C93")
      (value "104")
      (footprint "0603C")
      (description "Capacitor")
      (libsource (lib "") (part "CAP_1"))
    )
    (comp (ref "C94")
      (value "0.1uF")
      (footprint "0603C")
      (description "Capacitor")
      (libsource (lib "") (part "CAP_1"))
    )
    (comp (ref "C95")
      (value "104")
      (footprint "0603C")
      (description "Capacitor")
      (fields (field (name "PUBLISHER") "*"))
      (libsource (lib "*") (part "Cap"))
    )
    (comp (ref "C96")
      (value "104")
      (footprint "0603C")
      (description "Capacitor")
      (libsource (lib "") (part "CAP_1"))
    )
    (comp (ref "C97")
      (value "0.1uF")
      (footprint "0603C")
      (description "Capacitor")
      (libsource (lib "") (part "CAP_1"))
    )
    (comp (ref "C98")
      (value "104")
      (footprint "0603C")
      (description "Capacitor")
      (libsource (lib "") (part "CAP_1"))
    )
    (comp (ref "C99")
      (value "0.1uF")
      (footprint "0603C")
      (description "Capacitor")
      (libsource (lib "") (part "CAP_1"))
    )
    (comp (ref "C100")
      (value "104")
      (footprint "0603C")
      (description "Capacitor")
      (libsource (lib "") (part "CAP_1"))
    )
    (comp (ref "C101")
      (value "0.1uF")
      (footprint "0603C")
      (description "Capacitor")
      (libsource (lib "") (part "CAP_1"))
    )
    (comp (ref "C102")
      (value "104")
      (footprint "0603C")
      (description "Capacitor")
      (libsource (lib "") (part "CAP_1"))
    )
    (comp (ref "C103")
      (value "104")
      (footprint "0603C")
      (description "Capacitor")
      (libsource (lib "") (part "CAP_1"))
    )
    (comp (ref "C104")
      (value "0.1uF")
      (footprint "0603C")
      (description "Capacitor")
      (libsource (lib "") (part "CAP_1"))
    )
    (comp (ref "C105")
      (value "104")
      (footprint "0603C")
      (description "Capacitor")
      (libsource (lib "") (part "CAP_1"))
    )
    (comp (ref "C106")
      (value "104")
      (footprint "0603C")
      (description "Capacitor")
      (fields (field (name "PUBLISHER") "*"))
      (libsource (lib "*") (part "Cap"))
    )
    (comp (ref "C107")
      (value "104")
      (footprint "0603C")
      (description "Capacitor")
      (fields (field (name "PUBLISHER") "*"))
      (libsource (lib "*") (part "Cap"))
    )
    (comp (ref "C108")
      (value "104")
      (footprint "0603C")
      (description "Capacitor")
      (fields (field (name "PUBLISHER") "*"))
      (libsource (lib "*") (part "Cap"))
    )
    (comp (ref "C109")
      (value "104")
      (footprint "0603C")
      (description "Capacitor")
      (fields (field (name "PUBLISHER") "*"))
      (libsource (lib "*") (part "Cap"))
    )
    (comp (ref "C110")
      (value "0.1uF")
      (footprint "0603C")
      (description "Capacitor")
      (libsource (lib "*") (part "CAP"))
    )
    (comp (ref "C111")
      (value "0.1uF")
      (footprint "0603C")
      (description "Capacitor")
      (libsource (lib "*") (part "CAP"))
    )
    (comp (ref "C112")
      (value "0.1uF")
      (footprint "0603C")
      (description "Capacitor")
      (libsource (lib "*") (part "CAP"))
    )
    (comp (ref "C113")
      (value "0.1uF")
      (footprint "0603C")
      (description "Capacitor")
      (libsource (lib "*") (part "CAP"))
    )
    (comp (ref "C114")
      (value "0.1uF")
      (footprint "0603C")
      (description "Capacitor")
      (libsource (lib "") (part "CAP_1"))
    )
    (comp (ref "C115")
      (value "104")
      (footprint "0603C")
      (description "Capacitor")
      (libsource (lib "") (part "CAP_1"))
    )
    (comp (ref "C116")
      (value "0.1uF")
      (footprint "0603C")
      (description "Capacitor")
      (libsource (lib "") (part "CAP_1"))
    )
    (comp (ref "C117")
      (value "104")
      (footprint "0603C")
      (description "Capacitor")
      (libsource (lib "") (part "CAP_1"))
    )
    (comp (ref "C118")
      (value "0.1uF")
      (footprint "0603C")
      (description "Capacitor")
      (libsource (lib "") (part "CAP_1"))
    )
    (comp (ref "C119")
      (value "104")
      (footprint "0603C")
      (description "Capacitor")
      (libsource (lib "") (part "CAP_1"))
    )
    (comp (ref "C121")
      (value "0.1uF")
      (footprint "0603C")
      (description "Capacitor")
      (libsource (lib "") (part "CAP_1"))
    )
    (comp (ref "C122")
      (value "103")
      (footprint "0603C")
      (description "Capacitor")
      (libsource (lib "") (part "CAP_1"))
    )
    (comp (ref "C123")
      (value "104")
      (footprint "0603C")
      (description "Capacitor")
      (fields (field (name "PUBLISHER") "*"))
      (libsource (lib "*") (part "Cap"))
    )
    (comp (ref "C124")
      (value "104")
      (footprint "0603C")
      (description "Capacitor")
      (fields (field (name "PUBLISHER") "*"))
      (libsource (lib "*") (part "Cap"))
    )
    (comp (ref "C125")
      (value "104")
      (footprint "0603C")
      (description "Capacitor")
      (fields (field (name "PUBLISHER") "*"))
      (libsource (lib "*") (part "Cap"))
    )
    (comp (ref "C126")
      (value "103")
      (footprint "0603C")
      (description "Capacitor")
      (libsource (lib "") (part "CAP_1"))
    )
    (comp (ref "C127")
      (value "104")
      (footprint "0603C")
      (description "Capacitor")
      (fields (field (name "PUBLISHER") "*"))
      (libsource (lib "*") (part "Cap"))
    )
    (comp (ref "C128")
      (value "104")
      (footprint "0603C")
      (description "Capacitor")
      (fields (field (name "PUBLISHER") "*"))
      (libsource (lib "*") (part "Cap"))
    )
    (comp (ref "C129")
      (value "104")
      (footprint "0603C")
      (description "Capacitor")
      (fields (field (name "PUBLISHER") "*"))
      (libsource (lib "*") (part "Cap"))
    )
    (comp (ref "C130")
      (value "104")
      (footprint "0603C")
      (description "Capacitor")
      (fields (field (name "PUBLISHER") "*"))
      (libsource (lib "*") (part "Cap"))
    )
    (comp (ref "C131")
      (value "104")
      (footprint "0603C")
      (description "Capacitor")
      (fields (field (name "PUBLISHER") "*"))
      (libsource (lib "*") (part "Cap"))
    )
    (comp (ref "C132")
      (value "0.1uF")
      (footprint "0603C")
      (description "Capacitor")
      (libsource (lib "") (part "CAP_1"))
    )
    (comp (ref "C133")
      (value "104")
      (footprint "0603C")
      (description "Capacitor")
      (libsource (lib "") (part "CAP_1"))
    )
    (comp (ref "C134")
      (value "0.1uF")
      (footprint "0603C")
      (description "Capacitor")
      (libsource (lib "") (part "CAP_1"))
    )
    (comp (ref "C135")
      (value "104")
      (footprint "0603C")
      (description "Capacitor")
      (libsource (lib "") (part "CAP_1"))
    )
    (comp (ref "C136")
      (value "0.1uF")
      (footprint "0603C")
      (description "Capacitor")
      (libsource (lib "") (part "CAP_1"))
    )
    (comp (ref "C137")
      (value "104")
      (footprint "0603C")
      (description "Capacitor")
      (libsource (lib "") (part "CAP_1"))
    )
    (comp (ref "C138")
      (value "0.1uF")
      (footprint "0603C")
      (description "Capacitor")
      (libsource (lib "") (part "CAP_1"))
    )
    (comp (ref "C139")
      (value "104")
      (footprint "0603C")
      (description "Capacitor")
      (libsource (lib "") (part "CAP_1"))
    )
    (comp (ref "C140")
      (value "103")
      (footprint "0603C")
      (description "Capacitor")
      (libsource (lib "") (part "CAP_2"))
    )
    (comp (ref "C141")
      (value "103")
      (footprint "0603C")
      (description "Capacitor")
      (libsource (lib "") (part "CAP1_1"))
    )
    (comp (ref "C142")
      (value "103")
      (footprint "0603C")
      (description "Capacitor")
      (libsource (lib "") (part "CAP_2"))
    )
    (comp (ref "C143")
      (value "103")
      (footprint "0603C")
      (description "Capacitor")
      (libsource (lib "") (part "CAP1_1"))
    )
    (comp (ref "C144")
      (value "103")
      (footprint "0603C")
      (description "Capacitor")
      (libsource (lib "") (part "CAP1_1"))
    )
    (comp (ref "C145")
      (value "103")
      (footprint "0603C")
      (description "Capacitor")
      (libsource (lib "") (part "CAP1_1"))
    )
    (comp (ref "C146")
      (value "103")
      (footprint "0603C")
      (description "Capacitor")
      (libsource (lib "") (part "CAP_2"))
    )
    (comp (ref "C147")
      (value "103")
      (footprint "0603C")
      (description "Capacitor")
      (libsource (lib "") (part "CAP_2"))
    )
    (comp (ref "C148")
      (value "104")
      (footprint "0603C")
      (description "Capacitor")
      (fields (field (name "PUBLISHER") "*"))
      (libsource (lib "*") (part "Cap"))
    )
    (comp (ref "C149")
      (value "104")
      (footprint "0603C")
      (description "Capacitor")
      (fields (field (name "PUBLISHER") "*"))
      (libsource (lib "*") (part "Cap"))
    )
    (comp (ref "C150")
      (value "0.1uF")
      (footprint "0603C")
      (description "Capacitor")
      (libsource (lib "") (part "CAP_1"))
    )
    (comp (ref "C151")
      (value "0.1uF")
      (footprint "0603C")
      (description "Capacitor")
      (libsource (lib "") (part "CAP_1"))
    )
    (comp (ref "C152")
      (value "104")
      (footprint "0603C")
      (description "Capacitor")
      (libsource (lib "") (part "CAP_1"))
    )
    (comp (ref "C153")
      (value "104")
      (footprint "0603C")
      (description "Capacitor")
      (libsource (lib "") (part "CAP_1"))
    )
    (comp (ref "C154")
      (value "102/2KV/1206")
      (footprint "1206C")
      (description "C0603")
      (fields (field (name "PUBLISHER") "*"))
      (libsource (lib "*") (part "0.1uF"))
    )
    (comp (ref "D1") (value "1N4007") (footprint "1206D") (libsource (lib "*") (part "DIODE")))
    (comp (ref "D2") (value "1N4007") (footprint "1206D") (libsource (lib "*") (part "DIODE")))
    (comp (ref "D3") (value "GREEN") (footprint "D0805") (libsource (lib "*") (part "LED")))
    (comp (ref "D4") (value "RED") (footprint "D0805") (libsource (lib "*") (part "LED")))
    (comp (ref "D5") (value "GREEN") (footprint "D0805") (libsource (lib "*") (part "LED")))
    (comp (ref "D6") (value "RED") (footprint "D0805") (libsource (lib "*") (part "LED")))
    (comp (ref "D7") (value "GREEN") (footprint "D0805") (libsource (lib "*") (part "LED")))
    (comp (ref "D8") (value "RED") (footprint "D0805") (libsource (lib "*") (part "LED")))
    (comp (ref "D9") (value "1N4148") (footprint "1206D") (libsource (lib "*") (part "DIODE")))
    (comp (ref "D10") (value "GREEN") (footprint "D0805") (libsource (lib "*") (part "LED")))
    (comp (ref "D11") (value "RED") (footprint "D0805") (libsource (lib "*") (part "LED")))
    (comp (ref "D12") (value "1N4007") (footprint "1206D") (libsource (lib "*") (part "DIODE")))
    (comp (ref "D13") (value "1N4007") (footprint "1206D") (libsource (lib "*") (part "DIODE")))
    (comp (ref "D14") (value "1N4007") (footprint "1206D") (libsource (lib "*") (part "DIODE")))
    (comp (ref "D15") (value "1N4007") (footprint "1206D") (libsource (lib "*") (part "DIODE")))
    (comp (ref "D16") (value "1N4007") (footprint "1206D") (libsource (lib "*") (part "DIODE")))
    (comp (ref "D17") (value "1N4007") (footprint "1206D") (libsource (lib "*") (part "DIODE")))
    (comp (ref "D18") (value "1N4007") (footprint "1206D") (libsource (lib "*") (part "DIODE")))
    (comp (ref "D19") (value "1N4007") (footprint "1206D") (libsource (lib "*") (part "DIODE")))
    (comp (ref "D20") (value "1N4007") (footprint "1206D") (libsource (lib "*") (part "DIODE")))
    (comp (ref "D21") (value "1N4007") (footprint "1206D") (libsource (lib "*") (part "DIODE")))
    (comp (ref "D22") (value "1N4007") (footprint "1206D") (libsource (lib "*") (part "DIODE")))
    (comp (ref "D23") (value "1N4007") (footprint "1206D") (libsource (lib "*") (part "DIODE")))
    (comp (ref "D24") (value "1N4007") (footprint "1206D") (libsource (lib "*") (part "DIODE")))
    (comp (ref "D25") (value "1N4007") (footprint "1206D") (libsource (lib "*") (part "DIODE")))
    (comp (ref "D26") (value "1N4007") (footprint "1206D") (libsource (lib "*") (part "DIODE")))
    (comp (ref "D27") (value "1N4007") (footprint "1206D") (libsource (lib "*") (part "DIODE")))
    (comp (ref "D28") (value "1N4007") (footprint "1206D") (libsource (lib "*") (part "DIODE")))
    (comp (ref "D29") (value "1N4007") (footprint "1206D") (libsource (lib "*") (part "DIODE")))
    (comp (ref "D30") (value "1N4007") (footprint "1206D") (libsource (lib "*") (part "DIODE")))
    (comp (ref "D31") (value "1N4007") (footprint "1206D") (libsource (lib "*") (part "DIODE")))
    (comp (ref "D32") (value "1N4007") (footprint "1206D") (libsource (lib "*") (part "DIODE")))
    (comp (ref "D33") (value "1N4148") (footprint "1206D") (libsource (lib "*") (part "DIODE")))
    (comp (ref "DC1") (value "470uF/35V") (footprint "C470UF25VEJ") (libsource (lib "*") (part "CAP2")))
    (comp (ref "DC2") (value "470uF/35V") (footprint "C470UF25VEJ") (libsource (lib "*") (part "CAP2")))
    (comp (ref "EC1") (value "100uF/16V") (footprint "C100UF16VEJ") (libsource (lib "*") (part "CAP2")))
    (comp (ref "EC2")
      (value "470uF,25V")
      (footprint "C470UF25VEJ")
      (description "Capacitor")
      (libsource (lib "*") (part "CAPACITOR POL"))
    )
    (comp (ref "F1")
      (value "0.5A/0805")
      (footprint "0805R")
      (description "Fuse")
      (libsource (lib "EasyCortex M3-1752") (part "FUSE1"))
    )
    (comp (ref "J1")
      (value "J?")
      (footprint "KF2EDG-12P-3.81mm")
      (libsource (lib "UEEE20160408") (part "CON12"))
    )
    (comp (ref "J2")
      (value "CON6")
      (footprint "CON6-2.54mm-90")
      (description "Connector")
      (libsource (lib "*") (part "CON6"))
    )
    (comp (ref "J5")
      (value "J?")
      (footprint "KF2EDG-12P-3.81mm")
      (libsource (lib "UEEE20160408") (part "CON12"))
    )
    (comp (ref "J6") (value "J?") (footprint "KF2EDG-12P-3.81mm") (libsource (lib "") (part "CON12_1")))
    (comp (ref "J7") (value "J?") (footprint "KF2EDG-12P-3.81mm") (libsource (lib "") (part "CON12_1")))
    (comp (ref "J8")
      (value "J?")
      (footprint "KF2EDG-12P-3.81mm")
      (libsource (lib "UEEE20160408") (part "CON12"))
    )
    (comp (ref "J9")
      (value "J?")
      (footprint "KF2EDG-12P-3.81mm")
      (libsource (lib "UEEE20160408") (part "CON12"))
    )
    (comp (ref "J10")
      (value "CON6")
      (footprint "CON6-2.54mm-90")
      (description "Connector")
      (libsource (lib "*") (part "CON6"))
    )
    (comp (ref "J11")
      (value "J?")
      (footprint "KF2EDG-12P-3.81mm")
      (libsource (lib "UEEE20160408") (part "CON12"))
    )
    (comp (ref "J12")
      (value "CON5")
      (footprint "USB-A")
      (description "Connector")
      (libsource (lib "*") (part "CON5"))
    )
    (comp (ref "J13")
      (value "J?")
      (footprint "KF2EDG-12P-3.81mm")
      (libsource (lib "UEEE20160408") (part "CON12"))
    )
    (comp (ref "JP1")
      (value "3.81MM-6P")
      (footprint "CON-3.81MM-6P")
      (libsource (lib "xiaodong") (part "3.81MM-6P"))
    )
    (comp (ref "JP2")
      (value "3.81MM-6P")
      (footprint "CON-3.81MM-6P")
      (libsource (lib "xiaodong") (part "3.81MM-6P"))
    )
    (comp (ref "L1") (value "22uH") (footprint "LC7*7*3_L") (libsource (lib "*") (part "INDUCTOR")))
    (comp (ref "L2") (value "1uH") (footprint "1206R") (libsource (lib "*") (part "INDUCTOR")))
    (comp (ref "L3") (value "1uH") (footprint "1206R") (libsource (lib "*") (part "INDUCTOR")))
    (comp (ref "L4") (value "1uH") (footprint "1206R") (libsource (lib "*") (part "INDUCTOR")))
    (comp (ref "LED1") (value "GREEN") (footprint "D0805") (libsource (lib "*") (part "LED")))
    (comp (ref "LED2") (value "GREEN") (footprint "D0805") (libsource (lib "*") (part "LED")))
    (comp (ref "LED3") (value "GREEN") (footprint "D0805") (libsource (lib "*") (part "LED")))
    (comp (ref "LED4") (value "GREEN") (footprint "D0805") (libsource (lib "*") (part "LED")))
    (comp (ref "LED5") (value "GREEN") (footprint "D0805") (libsource (lib "*") (part "LED")))
    (comp (ref "LED6") (value "GREEN") (footprint "D0805") (libsource (lib "*") (part "LED")))
    (comp (ref "LED7") (value "GREEN") (footprint "D0805") (libsource (lib "*") (part "LED")))
    (comp (ref "LED8") (value "GREEN") (footprint "D0805") (libsource (lib "*") (part "LED")))
    (comp (ref "LED9") (value "GREEN") (footprint "D0805") (libsource (lib "*") (part "LED")))
    (comp (ref "LED10") (value "GREEN") (footprint "D0805") (libsource (lib "*") (part "LED")))
    (comp (ref "LED11") (value "GREEN") (footprint "D0805") (libsource (lib "*") (part "LED")))
    (comp (ref "LED12") (value "GREEN") (footprint "D0805") (libsource (lib "*") (part "LED")))
    (comp (ref "LED13") (value "GREEN") (footprint "D0805") (libsource (lib "*") (part "LED")))
    (comp (ref "LED14") (value "GREEN") (footprint "D0805") (libsource (lib "*") (part "LED")))
    (comp (ref "LED15") (value "RED") (footprint "D0805") (libsource (lib "*") (part "LED")))
    (comp (ref "LED16") (value "GREEN") (footprint "D0805") (libsource (lib "*") (part "LED")))
    (comp (ref "LED17") (value "GREEN") (footprint "D0805") (libsource (lib "*") (part "LED")))
    (comp (ref "LED18") (value "GREEN") (footprint "D0805") (libsource (lib "*") (part "LED")))
    (comp (ref "LED19") (value "GREEN") (footprint "D0805") (libsource (lib "*") (part "LED")))
    (comp (ref "LED20") (value "GREEN") (footprint "D0805") (libsource (lib "*") (part "LED")))
    (comp (ref "LED21") (value "GREEN") (footprint "D0805") (libsource (lib "*") (part "LED")))
    (comp (ref "LED23") (value "GREEN") (footprint "D0805") (libsource (lib "*") (part "LED")))
    (comp (ref "MAKE1")
      (value "MARK1.0")
      (footprint "MARK1.0")
      (description "Connector")
      (libsource (lib "*") (part "CON1"))
    )
    (comp (ref "MARKE1")
      (value "MARK1.0")
      (footprint "MARK1.0")
      (description "Connector")
      (libsource (lib "*") (part "CON1"))
    )
    (comp (ref "MARKE3")
      (value "MARK1.0")
      (footprint "MARK1.0")
      (description "Connector")
      (libsource (lib "*") (part "CON1"))
    )
    (comp (ref "Q1") (value "8050") (footprint "SOT23") (libsource (lib "*") (part "NPN")))
    (comp (ref "Q2") (value "8050") (footprint "SOT23") (libsource (lib "*") (part "NPN")))
    (comp (ref "Q3") (value "8050") (footprint "SOT23") (libsource (lib "*") (part "NPN")))
    (comp (ref "Q4") (value "8050") (footprint "SOT23") (libsource (lib "*") (part "NPN")))
    (comp (ref "Q5") (value "8050") (footprint "SOT23") (libsource (lib "*") (part "NPN")))
    (comp (ref "Q6") (value "8050") (footprint "SOT23") (libsource (lib "*") (part "NPN")))
    (comp (ref "Q7") (value "8050") (footprint "SOT23") (libsource (lib "*") (part "NPN")))
    (comp (ref "Q8") (value "8050") (footprint "SOT23") (libsource (lib "*") (part "NPN")))
    (comp (ref "Q9") (value "8050") (footprint "SOT23") (libsource (lib "*") (part "NPN")))
    (comp (ref "Q10") (value "8050") (footprint "SOT23") (libsource (lib "*") (part "NPN")))
    (comp (ref "Q11") (value "8050") (footprint "SOT23") (libsource (lib "*") (part "NPN")))
    (comp (ref "Q12") (value "8050") (footprint "SOT23") (libsource (lib "*") (part "NPN")))
    (comp (ref "Q13") (value "8050") (footprint "SOT23") (libsource (lib "*") (part "NPN")))
    (comp (ref "Q14") (value "8050") (footprint "SOT23") (libsource (lib "*") (part "NPN")))
    (comp (ref "Q15") (value "AO3407") (footprint "SOT-23L") (libsource (lib "SCH") (part "PMOS")))
    (comp (ref "Q16") (value "8050") (footprint "SOT23") (libsource (lib "*") (part "NPN")))
    (comp (ref "Q17") (value "AO3407") (footprint "SOT-23L") (libsource (lib "SCH") (part "PMOS")))
    (comp (ref "Q18") (value "8050") (footprint "SOT23") (libsource (lib "*") (part "NPN")))
    (comp (ref "Q19") (value "8050") (footprint "SOT23") (libsource (lib "*") (part "NPN")))
    (comp (ref "Q20") (value "8050") (footprint "SOT23") (libsource (lib "*") (part "NPN")))
    (comp (ref "Q21") (value "8050") (footprint "SOT23") (libsource (lib "*") (part "NPN")))
    (comp (ref "Q22") (value "8050") (footprint "SOT23") (libsource (lib "*") (part "NPN")))
    (comp (ref "Q23") (value "8050") (footprint "SOT23") (libsource (lib "*") (part "NPN")))
    (comp (ref "Q24") (value "8050") (footprint "SOT23") (libsource (lib "*") (part "NPN")))
    (comp (ref "Q25") (value "8050") (footprint "SOT23") (libsource (lib "*") (part "NPN")))
    (comp (ref "Q26") (value "8050") (footprint "SOT23") (libsource (lib "*") (part "NPN")))
    (comp (ref "Q27") (value "8050") (footprint "SOT23") (libsource (lib "*") (part "NPN")))
    (comp (ref "Q28") (value "8050") (footprint "SOT23") (libsource (lib "*") (part "NPN")))
    (comp (ref "R1") (value "1.2kΩ") (footprint "0603R") (libsource (lib "*") (part "R_S")))
    (comp (ref "R2") (value "4K7") (footprint "0603R") (libsource (lib "*") (part "RES1")))
    (comp (ref "R3") (value "2K/1%") (footprint "0603R") (libsource (lib "*") (part "RES1")))
    (comp (ref "R4") (value "43k") (footprint "0603R") (libsource (lib "*") (part "R_S")))
    (comp (ref "R5") (value "10k") (footprint "0603R") (libsource (lib "*") (part "R_S")))
    (comp (ref "R6") (value "1.2K/1%") (footprint "0603R") (libsource (lib "*") (part "RES1")))
    (comp (ref "R7") (value "6.8k") (footprint "0603R") (libsource (lib "*") (part "R_S")))
    (comp (ref "R8")
      (value "2K")
      (footprint "0603R")
      (description "RES")
      (libsource (lib "*") (part "RES-1"))
    )
    (comp (ref "R9")
      (value "2K")
      (footprint "0603R")
      (description "RES")
      (libsource (lib "*") (part "RES-1"))
    )
    (comp (ref "R10")
      (value "10R")
      (footprint "0603R")
      (description "RES")
      (libsource (lib "*") (part "RES-1"))
    )
    (comp (ref "R11")
      (value "10R")
      (footprint "0603R")
      (description "RES")
      (libsource (lib "*") (part "RES-1"))
    )
    (comp (ref "R12")
      (value "100R")
      (footprint "0603R")
      (description "RES")
      (libsource (lib "*") (part "RES-1"))
    )
    (comp (ref "R13")
      (value "100R")
      (footprint "0603R")
      (description "RES")
      (libsource (lib "*") (part "RES-1"))
    )
    (comp (ref "R14")
      (value "10R")
      (footprint "0603R")
      (description "RES")
      (libsource (lib "*") (part "RES-1"))
    )
    (comp (ref "R15")
      (value "10K")
      (footprint "0603R")
      (description "RES")
      (libsource (lib "*") (part "RES-1"))
    )
    (comp (ref "R16") (value "10K") (footprint "0603R") (libsource (lib "*") (part "RES1")))
    (comp (ref "R18") (value "10K") (footprint "0603R") (libsource (lib "*") (part "RES1")))
    (comp (ref "R19") (value "10K") (footprint "0603R") (libsource (lib "*") (part "RES1")))
    (comp (ref "R20") (value "10K") (footprint "0603R") (libsource (lib "*") (part "RES1")))
    (comp (ref "R21") (value "10K") (footprint "0603R") (libsource (lib "*") (part "RES1")))
    (comp (ref "R22")
      (value "2K")
      (footprint "0603R")
      (description "RES")
      (libsource (lib "*") (part "RES-1"))
    )
    (comp (ref "R23")
      (value "2K")
      (footprint "0603R")
      (description "RES")
      (libsource (lib "*") (part "RES-1"))
    )
    (comp (ref "R24")
      (value "10R")
      (footprint "0603R")
      (description "RES")
      (libsource (lib "*") (part "RES-1"))
    )
    (comp (ref "R26") (value "10K") (footprint "0603R") (libsource (lib "*") (part "RES1")))
    (comp (ref "R27") (value "1kR") (footprint "0603R") (libsource (lib "*") (part "RES1")))
    (comp (ref "R28")
      (value "10R")
      (footprint "0603R")
      (description "RES")
      (libsource (lib "*") (part "RES-1"))
    )
    (comp (ref "R29") (value "10K") (footprint "0603R") (libsource (lib "*") (part "RES1")))
    (comp (ref "R30") (value "10K") (footprint "0603R") (libsource (lib "*") (part "RES1")))
    (comp (ref "R31") (value "10K") (footprint "0603R") (libsource (lib "*") (part "RES1")))
    (comp (ref "R32")
      (value "100R")
      (footprint "0603R")
      (description "RES")
      (libsource (lib "*") (part "RES-1"))
    )
    (comp (ref "R33") (value "10K") (footprint "0603R") (libsource (lib "*") (part "RES1")))
    (comp (ref "R34")
      (value "100R")
      (footprint "0603R")
      (description "RES")
      (libsource (lib "*") (part "RES-1"))
    )
    (comp (ref "R35")
      (value "10R")
      (footprint "0603R")
      (description "RES")
      (libsource (lib "*") (part "RES-1"))
    )
    (comp (ref "R36") (value "1M") (footprint "1206R") (libsource (lib "") (part "RES2_1")))
    (comp (ref "R37")
      (value "10R")
      (footprint "0603R")
      (description "RES")
      (libsource (lib "*") (part "RES-1"))
    )
    (comp (ref "R38") (value "2k") (footprint "0603R") (libsource (lib "*") (part "RES2")))
    (comp (ref "R39") (value "120R") (footprint "1206R") (libsource (lib "") (part "RES2_1")))
    (comp (ref "R40")
      (value "0R")
      (footprint "0603R")
      (description "RES")
      (libsource (lib "*") (part "RES-1"))
    )
    (comp (ref "R41") (value "2k") (footprint "0603R") (libsource (lib "*") (part "RES2")))
    (comp (ref "R42")
      (value "0R")
      (footprint "0603R")
      (description "RES")
      (libsource (lib "*") (part "RES-1"))
    )
    (comp (ref "R43")
      (value "0R")
      (footprint "0603R")
      (description "RES")
      (libsource (lib "*") (part "RES-1"))
    )
    (comp (ref "R44")
      (value "0R")
      (footprint "0603R")
      (description "RES")
      (libsource (lib "*") (part "RES-1"))
    )
    (comp (ref "R45")
      (value "10R")
      (footprint "0603R")
      (description "RES")
      (libsource (lib "*") (part "RES-1"))
    )
    (comp (ref "R46")
      (value "1MΩ")
      (footprint "1206R")
      (fields (field (name "Comment") "1M"))
      (libsource (lib "") (part "RES2_1"))
    )
    (comp (ref "R47") (value "10K") (footprint "0603R") (libsource (lib "*") (part "RES1")))
    (comp (ref "R48") (value "10K") (footprint "0603R") (libsource (lib "*") (part "RES1")))
    (comp (ref "R49") (value "10K") (footprint "0603R") (libsource (lib "*") (part "RES1")))
    (comp (ref "R50") (value "10K") (footprint "0603R") (libsource (lib "*") (part "RES1")))
    (comp (ref "R51") (value "2k") (footprint "0603R") (libsource (lib "*") (part "RES2")))
    (comp (ref "R52") (value "10K") (footprint "0603R") (libsource (lib "*") (part "RES1")))
    (comp (ref "R53") (value "120R") (footprint "1206R") (libsource (lib "") (part "RES2_1")))
    (comp (ref "R54") (value "10K") (footprint "0603R") (libsource (lib "*") (part "RES1")))
    (comp (ref "R55") (value "2K") (footprint "0603R") (libsource (lib "*") (part "RES1")))
    (comp (ref "R56") (value "2k") (footprint "0603R") (libsource (lib "*") (part "RES2")))
    (comp (ref "R57") (value "3.3k1%") (footprint "0603R") (libsource (lib "*") (part "RES1")))
    (comp (ref "R58") (value "10k1%") (footprint "0603R") (libsource (lib "*") (part "RES1")))
    (comp (ref "R59") (value "10K") (footprint "0603R") (libsource (lib "*") (part "RES1")))
    (comp (ref "R60") (value "10K") (footprint "0603R") (libsource (lib "*") (part "RES1")))
    (comp (ref "R61") (value "10K") (footprint "0603R") (libsource (lib "*") (part "RES1")))
    (comp (ref "R62") (value "10K") (footprint "0603R") (libsource (lib "*") (part "RES1")))
    (comp (ref "R63") (value "10K") (footprint "0603R") (libsource (lib "*") (part "RES1")))
    (comp (ref "R64") (value "10K") (footprint "0603R") (libsource (lib "*") (part "RES1")))
    (comp (ref "R66") (value "10K") (footprint "0603R") (libsource (lib "") (part "RES1_1")))
    (comp (ref "R67") (value "10K") (footprint "0603R") (libsource (lib "") (part "RES1_1")))
    (comp (ref "R68") (value "5.1K") (footprint "0603R") (libsource (lib "") (part "RES1_1")))
    (comp (ref "R69") (value "5.1K") (footprint "0603R") (libsource (lib "*") (part "RES1")))
    (comp (ref "R70") (value "5.1K") (footprint "0603R") (libsource (lib "*") (part "RES1")))
    (comp (ref "R71") (value "10K") (footprint "0603R") (libsource (lib "") (part "RES1_1")))
    (comp (ref "R72") (value "10K") (footprint "0603R") (libsource (lib "") (part "RES1_1")))
    (comp (ref "R73") (value "4.7K") (footprint "0603R") (libsource (lib "*") (part "RES1")))
    (comp (ref "R74") (value "4.7K") (footprint "0603R") (libsource (lib "*") (part "RES1")))
    (comp (ref "R75") (value "4.7K") (footprint "0603R") (libsource (lib "") (part "RES1_1")))
    (comp (ref "R76") (value "10K") (footprint "0603R") (libsource (lib "*") (part "RES1")))
    (comp (ref "R77") (value "5.1K") (footprint "0603R") (libsource (lib "") (part "RES1_1")))
    (comp (ref "R78") (value "5.1K") (footprint "0603R") (libsource (lib "*") (part "RES1")))
    (comp (ref "R79") (value "5.1K") (footprint "0603R") (libsource (lib "") (part "RES1_1")))
    (comp (ref "R80") (value "5.1K") (footprint "0603R") (libsource (lib "*") (part "RES1")))
    (comp (ref "R81") (value "10K") (footprint "0603R") (libsource (lib "*") (part "RES1")))
    (comp (ref "R82") (value "4.7K") (footprint "0603R") (libsource (lib "*") (part "RES1")))
    (comp (ref "R83") (value "4.7K") (footprint "0603R") (libsource (lib "") (part "RES1_1")))
    (comp (ref "R84") (value "4.7K") (footprint "0603R") (libsource (lib "*") (part "RES1")))
    (comp (ref "R85") (value "4.7K") (footprint "0603R") (libsource (lib "") (part "RES1_1")))
    (comp (ref "R86") (value "10K") (footprint "0603R") (libsource (lib "*") (part "RES1")))
    (comp (ref "R87") (value "10K") (footprint "0603R") (libsource (lib "*") (part "RES1")))
    (comp (ref "R89") (value "10K") (footprint "0603R") (libsource (lib "") (part "RES1_1")))
    (comp (ref "R90") (value "10K") (footprint "0603R") (libsource (lib "") (part "RES1_1")))
    (comp (ref "R91") (value "10K") (footprint "0603R") (libsource (lib "") (part "RES1_1")))
    (comp (ref "R92") (value "10K") (footprint "0603R") (libsource (lib "") (part "RES1_1")))
    (comp (ref "R93") (value "10K") (footprint "0603R") (libsource (lib "*") (part "RES1")))
    (comp (ref "R94") (value "10K") (footprint "0603R") (libsource (lib "*") (part "RES1")))
    (comp (ref "R95") (value "10K") (footprint "0603R") (libsource (lib "*") (part "RES1")))
    (comp (ref "R96") (value "10K") (footprint "0603R") (libsource (lib "*") (part "RES1")))
    (comp (ref "R97") (value "4.7K") (footprint "0603R") (libsource (lib "*") (part "RES1")))
    (comp (ref "R98") (value "5.1K") (footprint "0603R") (libsource (lib "") (part "RES1_1")))
    (comp (ref "R99") (value "5.1K") (footprint "0603R") (libsource (lib "*") (part "RES1")))
    (comp (ref "R100") (value "5.1K") (footprint "0603R") (libsource (lib "*") (part "RES1")))
    (comp (ref "R102") (value "5.1K") (footprint "0603R") (libsource (lib "*") (part "RES1")))
    (comp (ref "R103")
      (value "10K")
      (footprint "0603R")
      (description "RES")
      (libsource (lib "*") (part "RES-1"))
    )
    (comp (ref "R104") (value "10K") (footprint "0603R") (libsource (lib "*") (part "RES1")))
    (comp (ref "R105")
      (value "10K")
      (footprint "0603R")
      (description "RES")
      (libsource (lib "*") (part "RES-1"))
    )
    (comp (ref "R106") (value "4.7K") (footprint "0603R") (libsource (lib "*") (part "RES1")))
    (comp (ref "R107") (value "4.7K") (footprint "0603R") (libsource (lib "") (part "RES1_1")))
    (comp (ref "R108") (value "4.7K") (footprint "0603R") (libsource (lib "*") (part "RES1")))
    (comp (ref "R110")
      (value "4K7")
      (footprint "0603R")
      (description "RES")
      (libsource (lib "*") (part "RES-1"))
    )
    (comp (ref "R111") (value "4.7K") (footprint "0603R") (libsource (lib "*") (part "RES1")))
    (comp (ref "R113") (value "10K") (footprint "0603R") (libsource (lib "*") (part "RES1")))
    (comp (ref "R114") (value "10K") (footprint "0603R") (libsource (lib "*") (part "RES1")))
    (comp (ref "R115") (value "10K") (footprint "0603R") (libsource (lib "*") (part "RES1")))
    (comp (ref "R117")
      (value "10K")
      (footprint "0603R")
      (description "RES")
      (libsource (lib "*") (part "RES-1"))
    )
    (comp (ref "R118")
      (value "10K")
      (footprint "0603R")
      (description "RES")
      (libsource (lib "*") (part "RES-1"))
    )
    (comp (ref "R119")
      (value "10K")
      (footprint "0603R")
      (description "RES")
      (libsource (lib "*") (part "RES-1"))
    )
    (comp (ref "R120") (value "10K") (footprint "0603R") (libsource (lib "*") (part "RES1")))
    (comp (ref "R121") (value "10K") (footprint "0603R") (libsource (lib "*") (part "RES1")))
    (comp (ref "R122") (value "10K") (footprint "0603R") (libsource (lib "*") (part "RES1")))
    (comp (ref "R123") (value "5.1K") (footprint "0603R") (libsource (lib "*") (part "RES1")))
    (comp (ref "R124") (value "5.1K") (footprint "0603R") (libsource (lib "*") (part "RES1")))
    (comp (ref "R125") (value "4.7K") (footprint "0603R") (libsource (lib "*") (part "RES1")))
    (comp (ref "R126") (value "4.7K") (footprint "0603R") (libsource (lib "*") (part "RES1")))
    (comp (ref "R127")
      (value "10K")
      (footprint "0603R")
      (description "RES")
      (libsource (lib "*") (part "RES-1"))
    )
    (comp (ref "R128")
      (value "10K")
      (footprint "0603R")
      (description "RES")
      (libsource (lib "*") (part "RES-1"))
    )
    (comp (ref "R129")
      (value "10K")
      (footprint "0603R")
      (description "RES")
      (libsource (lib "*") (part "RES-1"))
    )
    (comp (ref "R130") (value "10K") (footprint "0603R") (libsource (lib "*") (part "RES1")))
    (comp (ref "R131") (value "10K") (footprint "0603R") (libsource (lib "*") (part "RES1")))
    (comp (ref "R132") (value "10K") (footprint "0603R") (libsource (lib "*") (part "RES1")))
    (comp (ref "R133") (value "5.1K") (footprint "0603R") (libsource (lib "*") (part "RES1")))
    (comp (ref "R134") (value "4.7K") (footprint "0603R") (libsource (lib "*") (part "RES1")))
    (comp (ref "R135") (value "10K") (footprint "0603R") (libsource (lib "*") (part "RES1")))
    (comp (ref "R136") (value "4.7K") (footprint "0603R") (libsource (lib "*") (part "RES1")))
    (comp (ref "R137") (value "10K") (footprint "0603R") (libsource (lib "*") (part "RES1")))
    (comp (ref "R138")
      (value "10R")
      (footprint "0603R")
      (description "RES")
      (libsource (lib "*") (part "RES-1"))
    )
    (comp (ref "R139")
      (value "10R")
      (footprint "0603R")
      (description "RES")
      (libsource (lib "*") (part "RES-1"))
    )
    (comp (ref "R140") (value "10R") (footprint "0603R") (libsource (lib "*") (part "RES1")))
    (comp (ref "R141") (value "10R") (footprint "0603R") (libsource (lib "*") (part "RES1")))
    (comp (ref "R142")
      (value "10K")
      (footprint "0603R")
      (description "RES")
      (libsource (lib "*") (part "RES-1"))
    )
    (comp (ref "R143") (value "10K") (footprint "0603R") (libsource (lib "*") (part "RES1")))
    (comp (ref "R144") (value "5.1K") (footprint "0603R") (libsource (lib "") (part "RES1_1")))
    (comp (ref "R145") (value "4.7K") (footprint "0603R") (libsource (lib "") (part "RES1_1")))
    (comp (ref "R146") (value "5.1K") (footprint "0603R") (libsource (lib "*") (part "RES1")))
    (comp (ref "R147") (value "10K") (footprint "0603R") (libsource (lib "*") (part "RES1")))
    (comp (ref "R148") (value "10K") (footprint "0603R") (libsource (lib "*") (part "RES1")))
    (comp (ref "R149") (value "5.1K") (footprint "0603R") (libsource (lib "*") (part "RES1")))
    (comp (ref "R150") (value "10K") (footprint "0603R") (libsource (lib "*") (part "RES1")))
    (comp (ref "R151") (value "10K") (footprint "0603R") (libsource (lib "*") (part "RES1")))
    (comp (ref "R152")
      (value "10K")
      (footprint "0603R")
      (description "RES")
      (libsource (lib "*") (part "RES-1"))
    )
    (comp (ref "R153")
      (value "10K")
      (footprint "0603R")
      (description "RES")
      (libsource (lib "*") (part "RES-1"))
    )
    (comp (ref "R154")
      (value "10K")
      (footprint "0603R")
      (description "RES")
      (libsource (lib "*") (part "RES-1"))
    )
    (comp (ref "R155") (value "10K") (footprint "0603R") (libsource (lib "*") (part "RES1")))
    (comp (ref "R156") (value "5.1K") (footprint "0603R") (libsource (lib "") (part "RES1_1")))
    (comp (ref "R157") (value "4.7K") (footprint "0603R") (libsource (lib "") (part "RES1_1")))
    (comp (ref "R158") (value "10K") (footprint "0603R") (libsource (lib "*") (part "RES1")))
    (comp (ref "R159") (value "5.1K") (footprint "0603R") (libsource (lib "*") (part "RES1")))
    (comp (ref "R160") (value "4.7K") (footprint "0603R") (libsource (lib "*") (part "RES1")))
    (comp (ref "R161") (value "10K") (footprint "0603R") (libsource (lib "*") (part "RES1")))
    (comp (ref "R162") (value "5.1K") (footprint "0603R") (libsource (lib "*") (part "RES1")))
    (comp (ref "R163") (value "4.7K") (footprint "0603R") (libsource (lib "*") (part "RES1")))
    (comp (ref "R176") (value "2K") (footprint "0603R") (libsource (lib "") (part "RES1_2")))
    (comp (ref "R177") (value "3K") (footprint "0603R") (libsource (lib "") (part "RES1_2")))
    (comp (ref "R178") (value "2K") (footprint "0603R") (libsource (lib "") (part "RES1_2")))
    (comp (ref "R179") (value "10K") (footprint "0603R") (libsource (lib "") (part "RES1_3")))
    (comp (ref "R182") (value "2K") (footprint "0603R") (libsource (lib "") (part "RES1_2")))
    (comp (ref "R183") (value "1.5k") (footprint "0603R") (libsource (lib "") (part "RES1_2")))
    (comp (ref "R184") (value "3K") (footprint "0603R") (libsource (lib "") (part "RES1_2")))
    (comp (ref "R185") (value "2K") (footprint "0603R") (libsource (lib "") (part "RES1_2")))
    (comp (ref "R186") (value "10K") (footprint "0603R") (libsource (lib "") (part "RES1_3")))
    (comp (ref "R187") (value "1.5K") (footprint "0603R") (libsource (lib "") (part "RES1_2")))
    (comp (ref "R188")
      (value "10K")
      (footprint "0603R")
      (description "RES")
      (libsource (lib "*") (part "RES-1"))
    )
    (comp (ref "R189") (value "10K") (footprint "0603R") (libsource (lib "*") (part "RES1")))
    (comp (ref "R190")
      (value "10K")
      (footprint "0603R")
      (description "RES")
      (libsource (lib "*") (part "RES-1"))
    )
    (comp (ref "R191") (value "10K") (footprint "0603R") (libsource (lib "*") (part "RES1")))
    (comp (ref "R192")
      (value "10K")
      (footprint "0603R")
      (description "RES")
      (libsource (lib "*") (part "RES-1"))
    )
    (comp (ref "R193") (value "10K") (footprint "0603R") (libsource (lib "*") (part "RES1")))
    (comp (ref "R194")
      (value "10K")
      (footprint "0603R")
      (description "RES")
      (libsource (lib "*") (part "RES-1"))
    )
    (comp (ref "R195") (value "10K") (footprint "0603R") (libsource (lib "*") (part "RES1")))
    (comp (ref "R196")
      (value "100R")
      (footprint "0603R")
      (description "RES")
      (libsource (lib "*") (part "RES-1"))
    )
    (comp (ref "R197") (value "4.7K/1%") (footprint "0603R") (libsource (lib "") (part "RES1_2")))
    (comp (ref "R198") (value "4.7K/1%") (footprint "0603R") (libsource (lib "") (part "RES1_2")))
    (comp (ref "R199") (value "200/1%") (footprint "0603R") (libsource (lib "") (part "RES1_2")))
    (comp (ref "R200") (value "470/1%") (footprint "0603R") (libsource (lib "") (part "RES1_2")))
    (comp (ref "R201")
      (value "100R")
      (footprint "0603R")
      (description "RES")
      (libsource (lib "*") (part "RES-1"))
    )
    (comp (ref "R202") (value "470R/1%") (footprint "0603R") (libsource (lib "") (part "RES1_2")))
    (comp (ref "R203") (value "470R/1%") (footprint "0603R") (libsource (lib "") (part "RES1_2")))
    (comp (ref "R204") (value "200/1%") (footprint "0603R") (libsource (lib "") (part "RES1_2")))
    (comp (ref "R205") (value "470/1%") (footprint "0603R") (libsource (lib "") (part "RES1_2")))
    (comp (ref "R206")
      (value "100R")
      (footprint "0603R")
      (description "RES")
      (libsource (lib "*") (part "RES-1"))
    )
    (comp (ref "R207") (value "470R/1%") (footprint "0603R") (libsource (lib "") (part "RES1_2")))
    (comp (ref "R208") (value "470R/1%") (footprint "0603R") (libsource (lib "") (part "RES1_2")))
    (comp (ref "R209") (value "200/1%") (footprint "0603R") (libsource (lib "") (part "RES1_2")))
    (comp (ref "R210") (value "470/1%") (footprint "0603R") (libsource (lib "") (part "RES1_2")))
    (comp (ref "R211")
      (value "100R")
      (footprint "0603R")
      (description "RES")
      (libsource (lib "*") (part "RES-1"))
    )
    (comp (ref "R212") (value "470R/1%") (footprint "0603R") (libsource (lib "") (part "RES1_2")))
    (comp (ref "R213") (value "470R/1%") (footprint "0603R") (libsource (lib "") (part "RES1_2")))
    (comp (ref "R214") (value "200/1%") (footprint "0603R") (libsource (lib "") (part "RES1_2")))
    (comp (ref "R215") (value "470/1%") (footprint "0603R") (libsource (lib "") (part "RES1_2")))
    (comp (ref "R216") (value "33R") (footprint "0603R") (libsource (lib "UEEE160329") (part "RES2")))
    (comp (ref "R217") (value "33R") (footprint "0603R") (libsource (lib "UEEE160329") (part "RES2")))
    (comp (ref "R218") (value "15K") (footprint "0603R") (libsource (lib "UEEE160329") (part "RES2")))
    (comp (ref "R219") (value "15K") (footprint "0603R") (libsource (lib "UEEE160329") (part "RES2")))
    (comp (ref "R220")
      (value "10R")
      (footprint "0603R")
      (description "RES")
      (libsource (lib "*") (part "RES-1"))
    )
    (comp (ref "R221") (value "10K") (footprint "0603R") (libsource (lib "*") (part "RES1")))
    (comp (ref "R222") (value "5.1K") (footprint "0603R") (libsource (lib "*") (part "RES1")))
    (comp (ref "R223") (value "4.7K") (footprint "0603R") (libsource (lib "*") (part "RES1")))
    (comp (ref "R224")
      (value "10K")
      (footprint "0603R")
      (description "RES")
      (libsource (lib "*") (part "RES-1"))
    )
    (comp (ref "R225") (value "10K") (footprint "0603R") (libsource (lib "*") (part "RES1")))
    (comp (ref "R226")
      (value "10K")
      (footprint "0603R")
      (description "RES")
      (libsource (lib "*") (part "RES-1"))
    )
    (comp (ref "R227") (value "10K") (footprint "0603R") (libsource (lib "*") (part "RES1")))
    (comp (ref "RL1")
      (value "JQ1P-24V")
      (footprint "HF32F-12V")
      (libsource (lib "UEEE20160408") (part "JQ1P-12V"))
    )
    (comp (ref "RL2")
      (value "JQ1P-24V")
      (footprint "HF32F-12V")
      (libsource (lib "UEEE20160408") (part "JQ1P-12V"))
    )
    (comp (ref "RL3")
      (value "JQ1P-24V")
      (footprint "HF32F-12V")
      (libsource (lib "UEEE20160408") (part "JQ1P-12V"))
    )
    (comp (ref "RL4")
      (value "JQ1P-24V")
      (footprint "HF32F-12V")
      (libsource (lib "UEEE20160408") (part "JQ1P-12V"))
    )
    (comp (ref "RL5")
      (value "JQ1P-24V")
      (footprint "HF32F-12V")
      (libsource (lib "UEEE20160408") (part "JQ1P-12V"))
    )
    (comp (ref "RL6")
      (value "JQ1P-24V")
      (footprint "HF32F-12V")
      (libsource (lib "UEEE20160408") (part "JQ1P-12V"))
    )
    (comp (ref "RL7")
      (value "JQ1P-24V")
      (footprint "HF32F-12V")
      (libsource (lib "UEEE20160408") (part "JQ1P-12V"))
    )
    (comp (ref "RL8")
      (value "JQ1P-24V")
      (footprint "HF32F-12V")
      (libsource (lib "UEEE20160408") (part "JQ1P-12V"))
    )
    (comp (ref "RL9")
      (value "JQ1P-24V")
      (footprint "HF32F-12V")
      (libsource (lib "UEEE20160408") (part "JQ1P-12V"))
    )
    (comp (ref "RL10")
      (value "JQ1P-24V")
      (footprint "HF32F-12V")
      (libsource (lib "UEEE20160408") (part "JQ1P-12V"))
    )
    (comp (ref "RL11")
      (value "JQ1P-24V")
      (footprint "HF32F-12V")
      (libsource (lib "UEEE20160408") (part "JQ1P-12V"))
    )
    (comp (ref "RL12")
      (value "JQ1P-24V")
      (footprint "HF32F-12V")
      (libsource (lib "UEEE20160408") (part "JQ1P-12V"))
    )
    (comp (ref "RL13")
      (value "JQ1P-24V")
      (footprint "HF32F-12V")
      (libsource (lib "UEEE20160408") (part "JQ1P-12V"))
    )
    (comp (ref "RL14")
      (value "JQ1P-24V")
      (footprint "HF32F-12V")
      (libsource (lib "UEEE20160408") (part "JQ1P-12V"))
    )
    (comp (ref "RL15")
      (value "JQ1P-24V")
      (footprint "HF32F-12V")
      (libsource (lib "UEEE20160408") (part "JQ1P-12V"))
    )
    (comp (ref "RL16")
      (value "JQ1P-24V")
      (footprint "HF32F-12V")
      (libsource (lib "UEEE20160408") (part "JQ1P-12V"))
    )
    (comp (ref "RL17")
      (value "JQ1P-24V")
      (footprint "HF32F-12V")
      (libsource (lib "UEEE20160408") (part "JQ1P-12V"))
    )
    (comp (ref "RL18")
      (value "JQ1P-24V")
      (footprint "HF32F-12V")
      (libsource (lib "UEEE20160408") (part "JQ1P-12V"))
    )
    (comp (ref "RL19")
      (value "JQ1P-24V")
      (footprint "HF32F-12V")
      (libsource (lib "UEEE20160408") (part "JQ1P-12V"))
    )
    (comp (ref "RL20")
      (value "JQ1P-24V")
      (footprint "HF32F-12V")
      (libsource (lib "UEEE20160408") (part "JQ1P-12V"))
    )
    (comp (ref "RL21")
      (value "JQ1P-24V")
      (footprint "HF32F-12V")
      (libsource (lib "UEEE20160408") (part "JQ1P-12V"))
    )
    (comp (ref "SW1") (value "SW SPST") (footprint "SW1") (libsource (lib "*") (part "SW SPST")))
    (comp (ref "SW2") (value "SW SPST") (footprint "SW1") (libsource (lib "*") (part "SW SPST")))
    (comp (ref "SW3") (value "按键") (footprint "SW") (libsource (lib "*") (part "SW-PB")))
    (comp (ref "SW4") (value "SW SPST") (footprint "SW1") (libsource (lib "*") (part "SW SPST")))
    (comp (ref "TVS1") (value "BA301N") (footprint "3528TVS") (libsource (lib "*") (part "TVS-D")))
    (comp (ref "TVS2") (value "BA301N") (footprint "3528TVS") (libsource (lib "*") (part "TVS")))
    (comp (ref "TVS3") (value "BA301N") (footprint "3528TVS") (libsource (lib "*") (part "TVS-D")))
    (comp (ref "TVS4") (value "BA301N") (footprint "3528TVS") (libsource (lib "*") (part "TVS")))
    (comp (ref "TVS5") (value "BA301N") (footprint "3528TVS") (libsource (lib "*") (part "TVS-D")))
    (comp (ref "TVS6") (value "BA301N") (footprint "3528TVS") (libsource (lib "*") (part "TVS-D")))
    (comp (ref "TVS7") (value "BA301N") (footprint "3528TVS") (libsource (lib "*") (part "TVS")))
    (comp (ref "TVS8") (value "BA301N/NC") (footprint "3528TVS") (libsource (lib "*") (part "TVS")))
    (comp (ref "TVS10") (value "BA301N") (footprint "3528TVS") (libsource (lib "*") (part "TVS-D")))
    (comp (ref "TVS11") (value "BA301N") (footprint "3528TVS") (libsource (lib "*") (part "TVS")))
    (comp (ref "U1") (value "EUP3484") (footprint "SOP-8") (libsource (lib "*") (part "EUP3484")))
    (comp (ref "U2") (value "MIC29302") (footprint "TO5B") (libsource (lib "*") (part "MIC29302")))
    (comp (ref "U3")
      (value "LPC1778FBD144")
      (footprint "LC-LQFP-144_20x20x05P")
      (libsource (lib "直流原理图库") (part "LPC1778LQFP144"))
    )
    (comp (ref "U4")
      (value "RSM485S_CTM8251T")
      (footprint "RSM485")
      (libsource (lib "*") (part "RSM485S_CTM8251T"))
    )
    (comp (ref "U5") (value "SP706SEN") (footprint "SOP8") (libsource (lib "*") (part "SP706SEN")))
    (comp (ref "U6")
      (value "RSM485S_CTM8251T")
      (footprint "RSM485")
      (libsource (lib "*") (part "RSM485S_CTM8251T"))
    )
    (comp (ref "U7") (value "SP3232") (footprint "SO-16") (libsource (lib "*") (part "MAX232ESE")))
    (comp (ref "U8") (value "CTM8251") (footprint "CTM8251KT") (libsource (lib "直流原理图库") (part "CTM8251")))
    (comp (ref "U9") (value "CTM8251") (footprint "CTM8251KT") (libsource (lib "直流原理图库") (part "CTM8251")))
    (comp (ref "U10") (value "FM25CL64") (footprint "SOP8") (libsource (lib "*") (part "FM25CL64")))
    (comp (ref "U11")
      (value "CJ431")
      (footprint "SOT23")
      (description "TL431,SOT23/ST/ON")
      (libsource (lib "*") (part "TL431"))
    )
    (comp (ref "U12")
      (value "BELL")
      (footprint "BUZ")
      (description "Bell")
      (libsource (lib "*") (part "BELL"))
    )
    (comp (ref "U15") (value "PRTR5V0U2X") (footprint "SOT-143B") (libsource (lib "*") (part "PRTR5V0U2X_1")))
    (comp (ref "U37") (value "TL431") (footprint "SOT23") (libsource (lib "*") (part "TL431")))
    (comp (ref "U38") (value "TL431") (footprint "SOT23") (libsource (lib "*") (part "TL431")))
    (comp (ref "U40") (value "TL431") (footprint "SOT23") (libsource (lib "*") (part "TL431")))
    (comp (ref "U41") (value "TL431") (footprint "SOT23") (libsource (lib "*") (part "TL431")))
    (comp (ref "U43") (value "LM258") (footprint "SOP8") (libsource (lib "Mini9") (part "AS358P-E1")))
    (comp (ref "U44") (value "LM258") (footprint "SOP8") (libsource (lib "Mini9") (part "AS358P-E1")))
    (comp (ref "UG1") (value "PS2501L-1") (footprint "DIP-4") (libsource (lib "*") (part "PS2501-1")))
    (comp (ref "UG2") (value "PS2501L-1") (footprint "DIP-4") (libsource (lib "*") (part "PS2501-1")))
    (comp (ref "UG3") (value "PS2501L-1") (footprint "DIP-4") (libsource (lib "*") (part "PS2501-1")))
    (comp (ref "UG4") (value "PS2501L-1") (footprint "DIP-4") (libsource (lib "*") (part "PS2501-1")))
    (comp (ref "UG5") (value "PS2501L-1") (footprint "DIP-4") (libsource (lib "*") (part "PS2501-1")))
    (comp (ref "UG6") (value "PS2501L-1") (footprint "DIP-4") (libsource (lib "*") (part "PS2501-1")))
    (comp (ref "UG7") (value "PS2501L-1") (footprint "DIP-4") (libsource (lib "*") (part "PS2501-1")))
    (comp (ref "UG8") (value "PS2501L-1") (footprint "DIP-4") (libsource (lib "*") (part "PS2501-1")))
    (comp (ref "UG9") (value "PS2501L-1") (footprint "DIP-4") (libsource (lib "*") (part "PS2501-1")))
    (comp (ref "UG10") (value "PS2501L-1") (footprint "DIP-4") (libsource (lib "*") (part "PS2501-1")))
    (comp (ref "UG11") (value "PS2501L-1") (footprint "DIP-4") (libsource (lib "*") (part "PS2501-1")))
    (comp (ref "UG12") (value "PS2501L-1") (footprint "DIP-4") (libsource (lib "*") (part "PS2501-1")))
    (comp (ref "UG13") (value "PS2501L-1") (footprint "DIP-4") (libsource (lib "*") (part "PS2501-1")))
    (comp (ref "UG14") (value "PS2501L-1") (footprint "DIP-4") (libsource (lib "*") (part "PS2501-1")))
    (comp (ref "UG15") (value "PS2501L-1") (footprint "DIP-4") (libsource (lib "*") (part "PS2501-1")))
    (comp (ref "UG16") (value "PS2501L-1") (footprint "DIP-4") (libsource (lib "*") (part "PS2501-1")))
    (comp (ref "UG17") (value "PS2501L-1") (footprint "DIP-4") (libsource (lib "*") (part "PS2501-1")))
    (comp (ref "UG18") (value "PS2501L-1") (footprint "DIP-4") (libsource (lib "*") (part "PS2501-1")))
    (comp (ref "UG19") (value "PS2501L-1") (footprint "DIP-4") (libsource (lib "*") (part "PS2501-1")))
    (comp (ref "UG20") (value "PS2501L-1") (footprint "DIP-4") (libsource (lib "*") (part "PS2501-1")))
    (comp (ref "UG21") (value "PS2501L-1") (footprint "DIP-4") (libsource (lib "*") (part "PS2501-1")))
    (comp (ref "UG22") (value "PS2501L-1") (footprint "DIP-4") (libsource (lib "*") (part "PS2501-1")))
    (comp (ref "UG23") (value "PS2501L-1") (footprint "DIP-4") (libsource (lib "*") (part "PS2501-1")))
    (comp (ref "UG24") (value "PS2501L-1") (footprint "DIP-4") (libsource (lib "*") (part "PS2501-1")))
    (comp (ref "Y1") (value "32.768KHz") (footprint "ZS-32.768") (libsource (lib "*") (part "CRYSTAL")))
    (comp (ref "Y2") (value "12M") (footprint "ZS_SMD") (libsource (lib "*") (part "CRYSTAL")))
  )
  (nets
    (net (code "1") (name "/485_CON1") (class "Default")
      (node (ref "U3") (pin "134") (pinfunction "P4[31]/EMC_CS1_134") (pintype "bidirectional"))
      (node (ref "U4") (pin "5") (pinfunction "485_CON_5") (pintype "passive"))
    )
    (net (code "2") (name "/485_CON2") (class "Default")
      (node (ref "U3") (pin "130") (pinfunction "P4[30]/EMC_CS0_130") (pintype "bidirectional"))
      (node (ref "U6") (pin "5") (pinfunction "485_CON_5") (pintype "passive"))
    )
    (net (code "3") (name "/A1") (class "Default")
      (node (ref "J9") (pin "6") (pinfunction "6_6") (pintype "passive"))
      (node (ref "RL11") (pin "4") (pinfunction "RO_4") (pintype "passive"))
    )
    (net (code "4") (name "/A2") (class "Default")
      (node (ref "J9") (pin "8") (pinfunction "8_8") (pintype "passive"))
      (node (ref "RL12") (pin "4") (pinfunction "RO_4") (pintype "passive"))
    )
    (net (code "5") (name "/A3") (class "Default")
      (node (ref "J9") (pin "10") (pinfunction "10_10") (pintype "passive"))
      (node (ref "RL13") (pin "4") (pinfunction "RO_4") (pintype "passive"))
    )
    (net (code "6") (name "/A4") (class "Default")
      (node (ref "J9") (pin "12") (pinfunction "12_12") (pintype "passive"))
      (node (ref "RL14") (pin "4") (pinfunction "RO_4") (pintype "passive"))
    )
    (net (code "7") (name "/A5") (class "Default")
      (node (ref "J11") (pin "2") (pinfunction "2_2") (pintype "passive"))
      (node (ref "RL15") (pin "4") (pinfunction "RO_4") (pintype "passive"))
    )
    (net (code "8") (name "/A6") (class "Default")
      (node (ref "J11") (pin "4") (pinfunction "4_4") (pintype "passive"))
      (node (ref "RL16") (pin "4") (pinfunction "RO_4") (pintype "passive"))
    )
    (net (code "9") (name "/A7") (class "Default")
      (node (ref "J11") (pin "6") (pinfunction "6_6") (pintype "passive"))
      (node (ref "RL17") (pin "4") (pinfunction "RO_4") (pintype "passive"))
    )
    (net (code "10") (name "/A8") (class "Default")
      (node (ref "J11") (pin "8") (pinfunction "8_8") (pintype "passive"))
      (node (ref "RL18") (pin "4") (pinfunction "RO_4") (pintype "passive"))
    )
    (net (code "11") (name "/A9") (class "Default")
      (node (ref "J11") (pin "10") (pinfunction "10_10") (pintype "passive"))
      (node (ref "RL19") (pin "4") (pinfunction "RO_4") (pintype "passive"))
    )
    (net (code "12") (name "/A10") (class "Default")
      (node (ref "J11") (pin "12") (pinfunction "12_12") (pintype "passive"))
      (node (ref "RL20") (pin "4") (pinfunction "RO_4") (pintype "passive"))
    )
    (net (code "13") (name "/A12-RL") (class "Default")
      (node (ref "JP1") (pin "4") (pinfunction "4_4") (pintype "passive"))
      (node (ref "RL1") (pin "4") (pinfunction "RO_4") (pintype "passive"))
    )
    (net (code "14") (name "/A24-RL") (class "Default")
      (node (ref "JP1") (pin "6") (pinfunction "6_6") (pintype "passive"))
      (node (ref "RL4") (pin "4") (pinfunction "RO_4") (pintype "passive"))
    )
    (net (code "15") (name "/AAC-RL") (class "Default")
      (node (ref "J8") (pin "2") (pinfunction "2_2") (pintype "passive"))
      (node (ref "RL8") (pin "4") (pinfunction "RO_4") (pintype "passive"))
    )
    (net (code "16") (name "/ADC1-RL") (class "Default")
      (node (ref "J8") (pin "4") (pinfunction "4_4") (pintype "passive"))
      (node (ref "RL5") (pin "4") (pinfunction "RO_4") (pintype "passive"))
    )
    (net (code "17") (name "/ADC2_RL") (class "Default")
      (node (ref "J8") (pin "6") (pinfunction "6_6") (pintype "passive"))
      (node (ref "RL9") (pin "4") (pinfunction "RO_4") (pintype "passive"))
    )
    (net (code "18") (name "/ADC_CC1") (class "Default")
      (node (ref "U3") (pin "30") (pinfunction "P1[30]/USB_PWRD2/USB_VBUS/ADC0_IN4/I2C0_SDA/U3_OE_30") (pintype "bidirectional"))
    )
    (net (code "19") (name "/ADC_CC2") (class "Default")
      (node (ref "U3") (pin "28") (pinfunction "P1[31]/USB_OVRCR2/SSP1_SCK/ADC0_IN5/I2C0_SCL_28") (pintype "bidirectional"))
    )
    (net (code "20") (name "/ADD1") (class "Default")
      (node (ref "R68") (pin "1") (pinfunction "1_1") (pintype "passive"))
      (node (ref "U3") (pin "55") (pinfunction "P4[1]/EMC_A[1]_55") (pintype "bidirectional"))
    )
    (net (code "21") (name "/ADD2") (class "Default")
      (node (ref "R70") (pin "1") (pinfunction "1_1") (pintype "passive"))
      (node (ref "U3") (pin "45") (pinfunction "P3[23]/EMC_D[23]/PWM1_CAP0/T0_CAP0_45") (pintype "bidirectional"))
    )
    (net (code "22") (name "/ADD3") (class "Default")
      (node (ref "R69") (pin "1") (pinfunction "1_1") (pintype "passive"))
      (node (ref "U3") (pin "48") (pinfunction "P0[14]/USB_HSTEN2/SSP1_SSEL/USB_CONNECT2_48") (pintype "bidirectional"))
    )
    (net (code "23") (name "/ADD4") (class "Default")
      (node (ref "R133") (pin "1") (pinfunction "1_1") (pintype "passive"))
      (node (ref "U3") (pin "52") (pinfunction "P4[0]/EMC_A[0]_52") (pintype "bidirectional"))
    )
    (net (code "24") (name "/ADD5") (class "Default")
      (node (ref "R144") (pin "1") (pinfunction "1_1") (pintype "passive"))
      (node (ref "U3") (pin "58") (pinfunction "P4[2]/EMC_A[2]_58") (pintype "bidirectional"))
    )
    (net (code "25") (name "/ADD6") (class "Default")
      (node (ref "R146") (pin "1") (pinfunction "1_1") (pintype "passive"))
      (node (ref "U3") (pin "68") (pinfunction "P4[3]/EMC_A[3]_68") (pintype "bidirectional"))
    )
    (net (code "26") (name "/ADD7") (class "Default")
      (node (ref "R149") (pin "1") (pinfunction "1_1") (pintype "passive"))
      (node (ref "U3") (pin "71") (pinfunction "P2[13]/EINT3/SD_DAT[3]/I2S_TX_SDA_71") (pintype "bidirectional"))
    )
    (net (code "27") (name "/ADD8") (class "Default")
      (node (ref "R156") (pin "1") (pinfunction "1_1") (pintype "passive"))
      (node (ref "U3") (pin "73") (pinfunction "P2[12]/EINT2/SD_DAT[2]/I2S_TX_WS_73") (pintype "bidirectional"))
    )
    (net (code "28") (name "/ADD9") (class "Default")
      (node (ref "R159") (pin "1") (pinfunction "1_1") (pintype "passive"))
      (node (ref "U3") (pin "74") (pinfunction "P4[5]/EMC_A[5]_74") (pintype "bidirectional"))
    )
    (net (code "29") (name "/ADD10") (class "Default")
      (node (ref "R162") (pin "1") (pinfunction "1_1") (pintype "passive"))
      (node (ref "U3") (pin "75") (pinfunction "P2[11]/EINT1/SD_DAT[1]/I2S_TX_SCK_75") (pintype "bidirectional"))
    )
    (net (code "30") (name "/AGND") (class "Default")
      (node (ref "C42") (pin "2") (pintype "passive"))
      (node (ref "C43") (pin "2") (pintype "passive"))
      (node (ref "C44") (pin "2") (pinfunction "2_2") (pintype "passive"))
      (node (ref "L4") (pin "1") (pinfunction "1_1") (pintype "passive"))
      (node (ref "R58") (pin "1") (pinfunction "1_1") (pintype "passive"))
      (node (ref "U11") (pin "2") (pinfunction "A_2") (pintype "passive"))
      (node (ref "U3") (pin "15") (pinfunction "VSSA_15") (pintype "bidirectional"))
    )
    (net (code "31") (name "/B12_RL") (class "Default")
      (node (ref "J8") (pin "8") (pinfunction "8_8") (pintype "passive"))
      (node (ref "RL3") (pin "4") (pinfunction "RO_4") (pintype "passive"))
    )
    (net (code "32") (name "/B24-RL") (class "Default")
      (node (ref "J8") (pin "10") (pinfunction "10_10") (pintype "passive"))
      (node (ref "RL2") (pin "4") (pinfunction "RO_4") (pintype "passive"))
    )
    (net (code "33") (name "/BAC_RL") (class "Default")
      (node (ref "J8") (pin "12") (pinfunction "12_12") (pintype "passive"))
      (node (ref "RL6") (pin "4") (pinfunction "RO_4") (pintype "passive"))
    )
    (net (code "34") (name "/BDC1-RL") (class "Default")
      (node (ref "J9") (pin "2") (pinfunction "2_2") (pintype "passive"))
      (node (ref "RL7") (pin "4") (pinfunction "RO_4") (pintype "passive"))
    )
    (net (code "35") (name "/BDC2_RL") (class "Default")
      (node (ref "J9") (pin "4") (pinfunction "4_4") (pintype "passive"))
      (node (ref "RL10") (pin "4") (pinfunction "RO_4") (pintype "passive"))
    )
    (net (code "36") (name "/CANH1") (class "Default")
      (node (ref "J7") (pin "6") (pinfunction "6_6") (pintype "passive"))
      (node (ref "J7") (pin "8") (pinfunction "8_8") (pintype "passive"))
      (node (ref "R39") (pin "2") (pinfunction "2_2") (pintype "passive"))
      (node (ref "TVS7") (pin "1") (pintype "passive"))
      (node (ref "U8") (pin "6") (pinfunction "CANH_6") (pintype "passive"))
    )
    (net (code "37") (name "/CANH2") (class "Default")
      (node (ref "J7") (pin "2") (pinfunction "2_2") (pintype "passive"))
      (node (ref "J7") (pin "4") (pinfunction "4_4") (pintype "passive"))
      (node (ref "R53") (pin "2") (pinfunction "2_2") (pintype "passive"))
      (node (ref "TVS11") (pin "1") (pintype "passive"))
      (node (ref "U9") (pin "6") (pinfunction "CANH_6") (pintype "passive"))
    )
    (net (code "38") (name "/CANL1") (class "Default")
      (node (ref "J7") (pin "5") (pinfunction "5_5") (pintype "passive"))
      (node (ref "J7") (pin "7") (pinfunction "7_7") (pintype "passive"))
      (node (ref "R39") (pin "1") (pinfunction "1_1") (pintype "passive"))
      (node (ref "TVS5") (pin "2") (pintype "passive"))
      (node (ref "TVS7") (pin "2") (pintype "passive"))
      (node (ref "U8") (pin "7") (pinfunction "CANL_7") (pintype "passive"))
    )
    (net (code "39") (name "/CANL2") (class "Default")
      (node (ref "J7") (pin "1") (pinfunction "1_1") (pintype "passive"))
      (node (ref "J7") (pin "3") (pinfunction "3_3") (pintype "passive"))
      (node (ref "R53") (pin "1") (pinfunction "1_1") (pintype "passive"))
      (node (ref "TVS10") (pin "2") (pintype "passive"))
      (node (ref "TVS11") (pin "2") (pintype "passive"))
      (node (ref "U9") (pin "7") (pinfunction "CANL_7") (pintype "passive"))
    )
    (net (code "40") (name "/CAN_RD1") (class "Default")
      (node (ref "R56") (pin "2") (pinfunction "2_2") (pintype "passive"))
      (node (ref "U3") (pin "82") (pinfunction "P0[21]/U1_RI/SD_PWR/U4_OE/CAN_RD1/U4_SCLK_82") (pintype "bidirectional"))
      (node (ref "U9") (pin "4") (pinfunction "RD_4") (pintype "passive"))
    )
    (net (code "41") (name "/CAN_RD2") (class "Default")
      (node (ref "R41") (pin "2") (pinfunction "2_2") (pintype "passive"))
      (node (ref "U3") (pin "95") (pinfunction "P2[7]/CAN_RD2/U1_RTS_95") (pintype "bidirectional"))
      (node (ref "U8") (pin "4") (pinfunction "RD_4") (pintype "passive"))
    )
    (net (code "42") (name "/CAN_TD1") (class "Default")
      (node (ref "R51") (pin "2") (pinfunction "2_2") (pintype "passive"))
      (node (ref "U3") (pin "80") (pinfunction "P0[22]/U1_RTS/SD_DAT0/U4_TXD/CAN_TD1_80") (pintype "bidirectional"))
      (node (ref "U9") (pin "3") (pinfunction "TD_3") (pintype "passive"))
    )
    (net (code "43") (name "/CAN_TD2") (class "Default")
      (node (ref "R38") (pin "2") (pinfunction "2_2") (pintype "passive"))
      (node (ref "U3") (pin "93") (pinfunction "P2[8]/CAN_TD2/U2_TXD/U1_CTS/ENET_MDC_93") (pintype "bidirectional"))
      (node (ref "U8") (pin "3") (pinfunction "TD_3") (pintype "passive"))
    )
    (net (code "44") (name "/CON-C") (class "Default")
      (node (ref "C141") (pin "2") (pinfunction "2_2") (pintype "passive"))
      (node (ref "R199") (pin "1") (pinfunction "1_1") (pintype "passive"))
      (node (ref "R200") (pin "2") (pinfunction "2_2") (pintype "passive"))
      (node (ref "U3") (pin "8") (pinfunction "P0[26]/ADC0_IN3/DAC_OUT/U3_RXD_8") (pintype "bidirectional"))
    )
    (net (code "45") (name "/CON-D") (class "Default")
      (node (ref "C143") (pin "2") (pinfunction "2_2") (pintype "passive"))
      (node (ref "R204") (pin "1") (pinfunction "1_1") (pintype "passive"))
      (node (ref "R205") (pin "2") (pinfunction "2_2") (pintype "passive"))
      (node (ref "U3") (pin "10") (pinfunction "P0[25]/ADC0_IN2/I2S_RX_SDA/U3_TXD_10") (pintype "bidirectional"))
    )
    (net (code "46") (name "/CON-E") (class "Default")
      (node (ref "C144") (pin "2") (pinfunction "2_2") (pintype "passive"))
      (node (ref "R209") (pin "1") (pinfunction "1_1") (pintype "passive"))
      (node (ref "R210") (pin "2") (pinfunction "2_2") (pintype "passive"))
      (node (ref "U3") (pin "11") (pinfunction "P0[24]/ADC0_IN1/I2S_RX_WS/T3_CAP1_11") (pintype "bidirectional"))
    )
    (net (code "47") (name "/CON-F") (class "Default")
      (node (ref "C145") (pin "2") (pinfunction "2_2") (pintype "passive"))
      (node (ref "R214") (pin "1") (pinfunction "1_1") (pintype "passive"))
      (node (ref "R215") (pin "2") (pinfunction "2_2") (pintype "passive"))
      (node (ref "U3") (pin "13") (pinfunction "P0[23]/AD0_IN0/I2S_RX_SCK/T3_CAP0_13") (pintype "bidirectional"))
    )
    (net (code "48") (name "/DO1") (class "Default")
      (node (ref "R77") (pin "1") (pinfunction "1_1") (pintype "passive"))
      (node (ref "U3") (pin "38") (pinfunction "P3[26]/EMC_D[26]/PWM1[3]/T0_MAT1/STCLK_38") (pintype "bidirectional"))
    )
    (net (code "49") (name "/DO2") (class "Default")
      (node (ref "R80") (pin "1") (pinfunction "1_1") (pintype "passive"))
      (node (ref "U3") (pin "39") (pinfunction "P3[25]/EMC_D[25]/PWM1[2]/T0_MAT0_39") (pintype "bidirectional"))
    )
    (net (code "50") (name "/DO3") (class "Default")
      (node (ref "R102") (pin "1") (pinfunction "1_1") (pintype "passive"))
      (node (ref "U3") (pin "40") (pinfunction "P3[24]/EMC_D[24]/PWM1[1]/T0_CAP1_40") (pintype "bidirectional"))
    )
    (net (code "51") (name "/DO4") (class "Default")
      (node (ref "R98") (pin "1") (pinfunction "1_1") (pintype "passive"))
      (node (ref "U3") (pin "42") (pinfunction "P0[29]/USB_D+1/EINT0_42") (pintype "bidirectional"))
    )
    (net (code "52") (name "/DO5") (class "Default")
      (node (ref "R123") (pin "1") (pinfunction "1_1") (pintype "passive"))
      (node (ref "U3") (pin "43") (pinfunction "P0[30]/USB_D-1/EINT1_43") (pintype "bidirectional"))
    )
    (net (code "53") (name "/DO6") (class "Default")
      (node (ref "R78") (pin "1") (pinfunction "1_1") (pintype "passive"))
      (node (ref "U3") (pin "46") (pinfunction "P1[18]/USB_UP_LED1/PWM1[1]/T1CAP0/SSP1_MISO_46") (pintype "bidirectional"))
    )
    (net (code "54") (name "/DO7") (class "Default")
      (node (ref "R79") (pin "1") (pinfunction "1_1") (pintype "passive"))
      (node (ref "U3") (pin "47") (pinfunction "P1[19]/USB_TX_E1/USB_PPWR1/T1_CAP1/MC_0A/SSP1_SCK/U2_OE_47") (pintype "bidirectional"))
    )
    (net (code "55") (name "/DO8") (class "Default")
      (node (ref "R99") (pin "1") (pinfunction "1_1") (pintype "passive"))
      (node (ref "U3") (pin "49") (pinfunction "P1[20]/USB_TX_DP1/PWM1[2]/QEI_PHA/MC_FB0/SSP0_SCK_49") (pintype "bidirectional"))
    )
    (net (code "56") (name "/DO9") (class "Default")
      (node (ref "R100") (pin "1") (pinfunction "1_1") (pintype "passive"))
      (node (ref "U3") (pin "50") (pinfunction "P1[21]/USB_TX_DM1/PWM1[3]/SSP0_SSEL/MC_ABORT_50") (pintype "bidirectional"))
    )
    (net (code "57") (name "/DO10") (class "Default")
      (node (ref "R124") (pin "1") (pinfunction "1_1") (pintype "passive"))
      (node (ref "U3") (pin "51") (pinfunction "P1[22]/USB_RCV1/USB_PWRD1/T1_MAT0/MC_0B/_SSP1_MOSI_51") (pintype "bidirectional"))
    )
    (net (code "58") (name "/E-L1") (class "Default")
      (node (ref "C112") (pin "1") (pintype "passive"))
      (node (ref "J1") (pin "12") (pinfunction "12_12") (pintype "passive"))
      (node (ref "Q15") (pin "2") (pinfunction "D_2") (pintype "passive"))
    )
    (net (code "59") (name "/E-L2") (class "Default")
      (node (ref "C113") (pin "1") (pintype "passive"))
      (node (ref "J1") (pin "10") (pinfunction "10_10") (pintype "passive"))
      (node (ref "Q17") (pin "2") (pinfunction "D_2") (pintype "passive"))
    )
    (net (code "60") (name "/ERROR_1") (class "Default")
      (node (ref "R177") (pin "2") (pinfunction "2_2") (pintype "passive"))
      (node (ref "U3") (pin "112") (pinfunction "P0[7]/I2S_TX_SCK/SSP1_SCK/T2_MAT1/RTC_EV0_112") (pintype "bidirectional"))
    )
    (net (code "61") (name "/ERROR_2") (class "Default")
      (node (ref "R184") (pin "2") (pinfunction "2_2") (pintype "passive"))
      (node (ref "U3") (pin "113") (pinfunction "P0[6]/I2S_RX_SDA/SSP1_SSEL/T2_MAT0/U1_RTS_113") (pintype "bidirectional"))
    )
    (net (code "62") (name "/FAN+") (class "Default")
      (node (ref "JP1") (pin "1") (pinfunction "1_1") (pintype "passive"))
      (node (ref "RL21") (pin "3") (pinfunction "CM_3") (pintype "passive"))
    )
    (net (code "63") (name "/FAN-") (class "Default")
      (node (ref "JP1") (pin "2") (pinfunction "2_2") (pintype "passive"))
      (node (ref "RL21") (pin "4") (pinfunction "RO_4") (pintype "passive"))
    )
    (net (code "64") (name "/FAN-switch") (class "Default")
      (node (ref "R222") (pin "1") (pinfunction "1_1") (pintype "passive"))
      (node (ref "U3") (pin "29") (pinfunction "P0[12]/USB_PPWR2/SSP1_MISO/ADC0_IN6_29") (pintype "bidirectional"))
    )
    (net (code "65") (name "/FRAM_CS") (class "Default")
      (node (ref "R52") (pin "2") (pinfunction "2_2") (pintype "passive"))
      (node (ref "U10") (pin "1") (pinfunction "~{CS}_1") (pintype "passive"))
      (node (ref "U3") (pin "90") (pinfunction "P0[16]/U1_RXD/SSP0_SSEL_90") (pintype "bidirectional"))
    )
    (net (code "66") (name "/FRAM_MISO") (class "Default")
      (node (ref "R50") (pin "2") (pinfunction "2_2") (pintype "passive"))
      (node (ref "U10") (pin "2") (pinfunction "SO_2") (pintype "passive"))
      (node (ref "U3") (pin "87") (pinfunction "P0[17]/U1_CTS/SSP0_MISO_87") (pintype "bidirectional"))
    )
    (net (code "67") (name "/FRAM_MOSI") (class "Default")
      (node (ref "R49") (pin "2") (pinfunction "2_2") (pintype "passive"))
      (node (ref "U10") (pin "5") (pinfunction "SI_5") (pintype "passive"))
      (node (ref "U3") (pin "86") (pinfunction "P0[18]/U1_DCD/SSP0_MOSI_86") (pintype "bidirectional"))
    )
    (net (code "68") (name "/FRAM_SCK") (class "Default")
      (node (ref "R48") (pin "2") (pinfunction "2_2") (pintype "passive"))
      (node (ref "U10") (pin "6") (pinfunction "SCK_6") (pintype "passive"))
      (node (ref "U3") (pin "89") (pinfunction "P0[15]/U1_TXD/SSP0_SCK_89") (pintype "bidirectional"))
    )
    (net (code "69") (name "/IN1") (class "Default")
      (node (ref "J5") (pin "2") (pinfunction "2_2") (pintype "passive"))
      (node (ref "R119") (pin "1") (pintype "passive"))
    )
    (net (code "70") (name "/ISP") (class "Default")
      (node (ref "R15") (pin "1") (pintype "passive"))
      (node (ref "SW2") (pin "2") (pinfunction "NO_2") (pintype "passive"))
      (node (ref "U3") (pin "76") (pinfunction "P2[10]/EINT0/NMI_76") (pintype "bidirectional"))
    )
    (net (code "71") (name "/MODE1") (class "Default")
      (node (ref "R59") (pin "1") (pinfunction "1_1") (pintype "passive"))
      (node (ref "SW4") (pin "2") (pinfunction "NO_2") (pintype "passive"))
      (node (ref "U3") (pin "72") (pinfunction "P4[4]/EMC_A[4]_72") (pintype "bidirectional"))
    )
    (net (code "72") (name "/NCT-IN1") (class "Default")
      (node (ref "C62") (pin "1") (pintype "passive"))
      (node (ref "R66") (pin "2") (pinfunction "2_2") (pintype "passive"))
      (node (ref "U3") (pin "54") (pinfunction "P1[24]/USB_RX_DM1/PWM1[5]/QEI_IDX/MC_FB2/SSP0_MOSI_54") (pintype "bidirectional"))
      (node (ref "UG1") (pin "4") (pintype "passive"))
    )
    (net (code "73") (name "/NCT-IN2") (class "Default")
      (node (ref "C64") (pin "1") (pintype "passive"))
      (node (ref "R67") (pin "2") (pinfunction "2_2") (pintype "passive"))
      (node (ref "U3") (pin "56") (pinfunction "P1[25]/USB_LS1/USB_HSTEN1/T1_MAT1/MC_1A/CLKOUT_56") (pintype "bidirectional"))
      (node (ref "UG2") (pin "4") (pintype "passive"))
    )
    (net (code "74") (name "/NCT-IN3") (class "Default")
      (node (ref "C81") (pin "1") (pintype "passive"))
      (node (ref "R91") (pin "2") (pinfunction "2_2") (pintype "passive"))
      (node (ref "U3") (pin "57") (pinfunction "P1[26]/USB_SSPND1/PWM1[6]/T0_CAP0/MC_1B/SSP1_SSEL_57") (pintype "bidirectional"))
      (node (ref "UG3") (pin "4") (pintype "passive"))
    )
    (net (code "75") (name "/NCT-IN4") (class "Default")
      (node (ref "C83") (pin "1") (pintype "passive"))
      (node (ref "R92") (pin "2") (pinfunction "2_2") (pintype "passive"))
      (node (ref "U3") (pin "61") (pinfunction "P1[27]/USB_INT1/USB_OVRCR1/T0_CAP1/CLKOUT_61") (pintype "bidirectional"))
      (node (ref "UG4") (pin "4") (pintype "passive"))
    )
    (net (code "76") (name "/NCT-IN5") (class "Default")
      (node (ref "C98") (pin "1") (pintype "passive"))
      (node (ref "R113") (pin "2") (pinfunction "2_2") (pintype "passive"))
      (node (ref "U3") (pin "63") (pinfunction "P1[28]/USB_SCL1/PWM1_CAP0/T0_MAT0/MC_2A/SSP0_SSEL_63") (pintype "bidirectional"))
      (node (ref "UG5") (pin "4") (pintype "passive"))
    )
    (net (code "77") (name "/NCT-IN6") (class "Default")
      (node (ref "C103") (pin "1") (pintype "passive"))
      (node (ref "R114") (pin "2") (pinfunction "2_2") (pintype "passive"))
      (node (ref "U3") (pin "64") (pinfunction "P1[29]/USB_SDA1/PWM1_CAP1]/T0_MAT1/MC_2B/U4_TXD_64") (pintype "bidirectional"))
      (node (ref "UG6") (pin "4") (pintype "passive"))
    )
    (net (code "78") (name "/NCT-IN7") (class "Default")
      (node (ref "C92") (pin "1") (pintype "passive"))
      (node (ref "R120") (pin "2") (pinfunction "2_2") (pintype "passive"))
      (node (ref "U3") (pin "83") (pinfunction "P0[20]/U1_DTR/SD_CMD/I2C1_SCL_83") (pintype "bidirectional"))
      (node (ref "UG8") (pin "4") (pintype "passive"))
    )
    (net (code "79") (name "/NCT-IN8") (class "Default")
      (node (ref "C96") (pin "1") (pintype "passive"))
      (node (ref "R130") (pin "2") (pinfunction "2_2") (pintype "passive"))
      (node (ref "U3") (pin "84") (pinfunction "P4[7]/EMC_A[7]_84") (pintype "bidirectional"))
      (node (ref "UG9") (pin "4") (pintype "passive"))
    )
    (net (code "80") (name "/NCT-IN9") (class "Default")
      (node (ref "C72") (pin "1") (pintype "passive"))
      (node (ref "R87") (pin "2") (pinfunction "2_2") (pintype "passive"))
      (node (ref "U3") (pin "85") (pinfunction "P0[19]/U1_DSR/SD_CLK/I2C1_SDA_85") (pintype "bidirectional"))
      (node (ref "UG10") (pin "4") (pintype "passive"))
    )
    (net (code "81") (name "/NCT-IN10") (class "Default")
      (node (ref "C100") (pin "1") (pintype "passive"))
      (node (ref "R104") (pin "2") (pinfunction "2_2") (pintype "passive"))
      (node (ref "U3") (pin "91") (pinfunction "P4[9]/EMC_A[9]_91") (pintype "bidirectional"))
      (node (ref "UG11") (pin "4") (pintype "passive"))
    )
    (net (code "82") (name "/NCT-IN11") (class "Default")
      (node (ref "C102") (pin "1") (pintype "passive"))
      (node (ref "R76") (pin "2") (pinfunction "2_2") (pintype "passive"))
      (node (ref "U3") (pin "92") (pinfunction "P2[9]/USB_CONNECT1/U2_RXD/U4_RXD/ENET_MDIO_92") (pintype "bidirectional"))
      (node (ref "UG12") (pin "4") (pintype "passive"))
    )
    (net (code "83") (name "/NCT-IN12") (class "Default")
      (node (ref "C87") (pin "1") (pintype "passive"))
      (node (ref "R86") (pin "2") (pinfunction "2_2") (pintype "passive"))
      (node (ref "U3") (pin "108") (pinfunction "P4[13]/EMC_A[13]_108") (pintype "bidirectional"))
      (node (ref "UG13") (pin "4") (pintype "passive"))
    )
    (net (code "84") (name "/NCT-IN13") (class "Default")
      (node (ref "C115") (pin "1") (pintype "passive"))
      (node (ref "R148") (pin "2") (pinfunction "2_2") (pintype "passive"))
      (node (ref "U3") (pin "109") (pinfunction "P0[9]/I2S_TX_SDA/SSP1_MOSI/T2_MAT3/RTC_EV2_109") (pintype "bidirectional"))
      (node (ref "UG14") (pin "4") (pintype "passive"))
    )
    (net (code "85") (name "/NCT-IN14") (class "Default")
      (node (ref "C117") (pin "1") (pintype "passive"))
      (node (ref "R150") (pin "2") (pinfunction "2_2") (pintype "passive"))
      (node (ref "U3") (pin "110") (pinfunction "P4[14]/EMC_A[14]_110") (pintype "bidirectional"))
      (node (ref "UG15") (pin "4") (pintype "passive"))
    )
    (net (code "86") (name "/NCT-IN15") (class "Default")
      (node (ref "C119") (pin "1") (pintype "passive"))
      (node (ref "R151") (pin "2") (pinfunction "2_2") (pintype "passive"))
      (node (ref "U3") (pin "111") (pinfunction "P0[8]/I2S_TX_WS/SSP1_MISO/T2_MAT2/RTC_EV1_111") (pintype "bidirectional"))
      (node (ref "UG16") (pin "4") (pintype "passive"))
    )
    (net (code "87") (name "/NCT-IN16") (class "Default")
      (node (ref "C133") (pin "1") (pintype "passive"))
      (node (ref "R189") (pin "2") (pinfunction "2_2") (pintype "passive"))
      (node (ref "U3") (pin "105") (pinfunction "P2[2]/PWM1[3]/U1_CTS/T2_MAT3/TRACEDATA[3]_105") (pintype "bidirectional"))
      (node (ref "UG19") (pin "4") (pintype "passive"))
    )
    (net (code "88") (name "/NCT-IN17") (class "Default")
      (node (ref "C135") (pin "1") (pintype "passive"))
      (node (ref "R191") (pin "2") (pinfunction "2_2") (pintype "passive"))
      (node (ref "U3") (pin "104") (pinfunction "P4[12]/EMC_A[12]_104") (pintype "bidirectional"))
      (node (ref "UG20") (pin "4") (pintype "passive"))
    )
    (net (code "89") (name "/NCT-IN18") (class "Default")
      (node (ref "C137") (pin "1") (pintype "passive"))
      (node (ref "R193") (pin "2") (pinfunction "2_2") (pintype "passive"))
      (node (ref "U3") (pin "100") (pinfunction "P2[3]/PWM1[4]/U1_DCD/T2_MAT2/TRACEDATA[2]_100") (pintype "bidirectional"))
      (node (ref "UG21") (pin "4") (pintype "passive"))
    )
    (net (code "90") (name "/NCT-IN19") (class "Default")
      (node (ref "C152") (pin "1") (pintype "passive"))
      (node (ref "R225") (pin "2") (pinfunction "2_2") (pintype "passive"))
      (node (ref "U3") (pin "97") (pinfunction "P2[5]/PWM1[6]/U1_DTR/T2_MAT0/TRACEDATA[0]_97") (pintype "bidirectional"))
      (node (ref "UG23") (pin "4") (pintype "passive"))
    )
    (net (code "91") (name "/NCT-IN20") (class "Default")
      (node (ref "C153") (pin "1") (pintype "passive"))
      (node (ref "R227") (pin "2") (pinfunction "2_2") (pintype "passive"))
      (node (ref "U3") (pin "94") (pinfunction "P4[10]/EMC_A[10]_94") (pintype "bidirectional"))
      (node (ref "UG24") (pin "4") (pintype "passive"))
    )
    (net (code "92") (name "/NCT-IN21") (class "Default")
      (node (ref "C139") (pin "1") (pintype "passive"))
      (node (ref "R195") (pin "2") (pinfunction "2_2") (pintype "passive"))
      (node (ref "U3") (pin "99") (pinfunction "P2[4]/PWM1[5]/U1_DSR/T2_MAT1/TRACEDATA[1]_99") (pintype "bidirectional"))
      (node (ref "UG22") (pin "4") (pintype "passive"))
    )
    (net (code "93") (name "/RTCK1") (class "Default")
      (node (ref "C45") (pin "1") (pinfunction "1_1") (pintype "passive"))
      (node (ref "U3") (pin "23") (pinfunction "RTCX1_23") (pintype "bidirectional"))
      (node (ref "Y1") (pin "1") (pinfunction "1_1") (pintype "passive"))
    )
    (net (code "94") (name "/RTCK2") (class "Default")
      (node (ref "C47") (pin "1") (pinfunction "1_1") (pintype "passive"))
      (node (ref "U3") (pin "25") (pinfunction "RTCX2_25") (pintype "bidirectional"))
      (node (ref "Y1") (pin "2") (pinfunction "2_2") (pintype "passive"))
    )
    (net (code "95") (name "/Run") (class "Default")
      (node (ref "R29") (pin "1") (pinfunction "1_1") (pintype "passive"))
      (node (ref "U3") (pin "96") (pinfunction "P2[6]/PWM1_CAP0/U1_RI/T2_CAP0/U2_OE/TRACECELK_96") (pintype "bidirectional"))
    )
    (net (code "96") (name "/STOP_TEST") (class "Default")
      (node (ref "C105") (pin "1") (pintype "passive"))
      (node (ref "R115") (pin "2") (pinfunction "2_2") (pintype "passive"))
      (node (ref "U3") (pin "53") (pinfunction "P1[23]/USB_RX_DP1/PWM1[4]/QEI_PHB/MC_FB1/SSP0_MISO_53") (pintype "bidirectional"))
      (node (ref "UG7") (pin "4") (pintype "passive"))
    )
    (net (code "97") (name "/TCK") (class "Default")
      (node (ref "J2") (pin "3") (pinfunction "3_3") (pintype "passive"))
      (node (ref "R30") (pin "1") (pinfunction "1_1") (pintype "passive"))
      (node (ref "U3") (pin "7") (pinfunction "JTAG_TCK_7") (pintype "bidirectional"))
    )
    (net (code "98") (name "/TDO") (class "Default")
      (node (ref "J2") (pin "2") (pinfunction "2_2") (pintype "passive"))
      (node (ref "R137") (pin "1") (pinfunction "1_1") (pintype "passive"))
      (node (ref "U3") (pin "1") (pinfunction "JTAG_TDO_1") (pintype "bidirectional"))
    )
    (net (code "99") (name "/TMS") (class "Default")
      (node (ref "J2") (pin "4") (pinfunction "4_4") (pintype "passive"))
      (node (ref "R31") (pin "1") (pinfunction "1_1") (pintype "passive"))
      (node (ref "U3") (pin "4") (pinfunction "JTAG_TMS_4") (pintype "bidirectional"))
    )
    (net (code "100") (name "/U0-RX") (class "Default")
      (node (ref "J6") (pin "11") (pinfunction "11_11") (pintype "passive"))
      (node (ref "R138") (pin "2") (pintype "passive"))
    )
    (net (code "101") (name "/U0-RXD") (class "Default")
      (node (ref "R40") (pin "1") (pintype "passive"))
      (node (ref "U3") (pin "142") (pinfunction "P0[3]/U0_RXD/U3_RXD_142") (pintype "bidirectional"))
    )
    (net (code "102") (name "/U0-TX") (class "Default")
      (node (ref "J6") (pin "10") (pinfunction "10_10") (pintype "passive"))
      (node (ref "R139") (pin "2") (pintype "passive"))
    )
    (net (code "103") (name "/U0-TXD") (class "Default")
      (node (ref "R43") (pin "1") (pintype "passive"))
      (node (ref "U3") (pin "141") (pinfunction "P0[2]/U0_TXD/U3_TXD_141") (pintype "bidirectional"))
    )
    (net (code "104") (name "/U1-RX") (class "Default")
      (node (ref "J6") (pin "7") (pinfunction "7_7") (pintype "passive"))
      (node (ref "R37") (pin "2") (pintype "passive"))
      (node (ref "TVS6") (pin "2") (pintype "passive"))
      (node (ref "TVS8") (pin "2") (pintype "passive"))
    )
    (net (code "105") (name "/U1-TX") (class "Default")
      (node (ref "J6") (pin "6") (pinfunction "6_6") (pintype "passive"))
      (node (ref "R45") (pin "2") (pintype "passive"))
      (node (ref "TVS8") (pin "1") (pintype "passive"))
    )
    (net (code "106") (name "/U1_RXD") (class "Default")
      (node (ref "D5") (pin "2") (pintype "passive"))
      (node (ref "R34") (pin "1") (pintype "passive"))
      (node (ref "U3") (pin "106") (pinfunction "P2[1]/PWM1[2]/U1_RXD_106") (pintype "bidirectional"))
    )
    (net (code "107") (name "/U1_TXD") (class "Default")
      (node (ref "D6") (pin "2") (pintype "passive"))
      (node (ref "R32") (pin "1") (pintype "passive"))
      (node (ref "U3") (pin "107") (pinfunction "P2[0]/PWM1[1]/U1_TXD_107") (pintype "bidirectional"))
    )
    (net (code "108") (name "/U2_RXD") (class "Default")
      (node (ref "R141") (pin "2") (pinfunction "2_2") (pintype "passive"))
      (node (ref "U3") (pin "70") (pinfunction "P0[11]/U2_RXD/I2C2_SCL/T3_MAT1_70") (pintype "bidirectional"))
    )
    (net (code "109") (name "/U2_TXD") (class "Default")
      (node (ref "R140") (pin "2") (pinfunction "2_2") (pintype "passive"))
      (node (ref "U3") (pin "69") (pinfunction "P0[10]/U2_TXD/I2C2_SDA/T3_MAT0_69") (pintype "bidirectional"))
    )
    (net (code "110") (name "/U3_485A") (class "Default")
      (node (ref "J6") (pin "2") (pinfunction "2_2") (pintype "passive"))
      (node (ref "J6") (pin "4") (pinfunction "4_4") (pintype "passive"))
      (node (ref "R11") (pin "2") (pintype "passive"))
      (node (ref "TVS2") (pin "2") (pintype "passive"))
    )
    (net (code "111") (name "/U3_485B") (class "Default")
      (node (ref "J6") (pin "1") (pinfunction "1_1") (pintype "passive"))
      (node (ref "J6") (pin "3") (pinfunction "3_3") (pintype "passive"))
      (node (ref "R14") (pin "2") (pintype "passive"))
      (node (ref "TVS1") (pin "2") (pintype "passive"))
      (node (ref "TVS2") (pin "1") (pintype "passive"))
    )
    (net (code "112") (name "/U3_RXD") (class "Default")
      (node (ref "R42") (pin "1") (pintype "passive"))
      (node (ref "U3") (pin "122") (pinfunction "P4[29]/EMC_BLS3/U3_RXD/T2_MAT1/I2C2_SCL_122") (pintype "bidirectional"))
    )
    (net (code "113") (name "/U3_TXD") (class "Default")
      (node (ref "R44") (pin "1") (pintype "passive"))
      (node (ref "U3") (pin "118") (pinfunction "P4[28]/EMC_ABLS2/U3_TXD/T2_MAT0_118") (pintype "bidirectional"))
    )
    (net (code "114") (name "/U4_485A") (class "Default")
      (node (ref "J7") (pin "10") (pinfunction "10_10") (pintype "passive"))
      (node (ref "J7") (pin "12") (pinfunction "12_12") (pintype "passive"))
      (node (ref "R28") (pin "2") (pintype "passive"))
      (node (ref "TVS4") (pin "2") (pintype "passive"))
    )
    (net (code "115") (name "/U4_485B") (class "Default")
      (node (ref "J7") (pin "11") (pinfunction "11_11") (pintype "passive"))
      (node (ref "J7") (pin "9") (pinfunction "9_9") (pintype "passive"))
      (node (ref "R35") (pin "2") (pintype "passive"))
      (node (ref "TVS3") (pin "2") (pintype "passive"))
      (node (ref "TVS4") (pin "1") (pintype "passive"))
    )
    (net (code "116") (name "/U4_RXD") (class "Default")
      (node (ref "D3") (pin "2") (pintype "passive"))
      (node (ref "R13") (pin "1") (pintype "passive"))
      (node (ref "U3") (pin "98") (pinfunction "P5[3]/U4_RXD//I2C0_SCL_98") (pintype "bidirectional"))
    )
    (net (code "117") (name "/U4_TXD") (class "Default")
      (node (ref "D4") (pin "2") (pintype "passive"))
      (node (ref "R12") (pin "1") (pintype "passive"))
      (node (ref "U3") (pin "143") (pinfunction "P5[4]/U0_OE/T3_MAT3/U4_TXD_143") (pintype "bidirectional"))
    )
    (net (code "118") (name "/USBD2+") (class "Default")
      (node (ref "R217") (pin "2") (pinfunction "2_2") (pintype "passive"))
      (node (ref "U3") (pin "36") (pinfunction "P0[31]/USB_D+2_36") (pintype "bidirectional"))
    )
    (net (code "119") (name "/USBD2-") (class "Default")
      (node (ref "R216") (pin "2") (pinfunction "2_2") (pintype "passive"))
      (node (ref "U3") (pin "37") (pinfunction "USB_D-2_37") (pintype "bidirectional"))
    )
    (net (code "121") (name "/WDI") (class "Default")
      (node (ref "R19") (pin "2") (pinfunction "2_2") (pintype "passive"))
      (node (ref "U3") (pin "35") (pinfunction "P0[27]/I2C0_SDA/USB_SDA1_35") (pintype "bidirectional"))
      (node (ref "U5") (pin "6") (pinfunction "WDI_6") (pintype "passive"))
    )
    (net (code "122") (name "/XTAL1") (class "Default")
      (node (ref "C46") (pin "1") (pinfunction "1_1") (pintype "passive"))
      (node (ref "U3") (pin "31") (pinfunction "XTAL1_31") (pintype "bidirectional"))
      (node (ref "Y2") (pin "2") (pinfunction "2_2") (pintype "passive"))
    )
    (net (code "123") (name "/XTAL2") (class "Default")
      (node (ref "C48") (pin "1") (pinfunction "1_1") (pintype "passive"))
      (node (ref "U3") (pin "33") (pinfunction "XTAL2_33") (pintype "bidirectional"))
      (node (ref "Y2") (pin "1") (pinfunction "1_1") (pintype "passive"))
    )
    (net (code "124") (name "/Y1-in") (class "Default")
      (node (ref "J5") (pin "3") (pinfunction "3_3") (pintype "passive"))
      (node (ref "R71") (pin "1") (pinfunction "1_1") (pintype "passive"))
    )
    (net (code "125") (name "/Y2-in") (class "Default")
      (node (ref "J5") (pin "4") (pinfunction "4_4") (pintype "passive"))
      (node (ref "R72") (pin "1") (pinfunction "1_1") (pintype "passive"))
    )
    (net (code "126") (name "/Y3-in") (class "Default")
      (node (ref "J5") (pin "5") (pinfunction "5_5") (pintype "passive"))
      (node (ref "R89") (pin "1") (pinfunction "1_1") (pintype "passive"))
    )
    (net (code "127") (name "/Y4-in") (class "Default")
      (node (ref "J5") (pin "6") (pinfunction "6_6") (pintype "passive"))
      (node (ref "R90") (pin "1") (pinfunction "1_1") (pintype "passive"))
    )
    (net (code "128") (name "/Y5-in") (class "Default")
      (node (ref "J5") (pin "7") (pinfunction "7_7") (pintype "passive"))
      (node (ref "R117") (pin "1") (pintype "passive"))
    )
    (net (code "129") (name "/Y6-in") (class "Default")
      (node (ref "J5") (pin "8") (pinfunction "8_8") (pintype "passive"))
      (node (ref "R118") (pin "1") (pintype "passive"))
    )
    (net (code "130") (name "/Y7-in") (class "Default")
      (node (ref "J5") (pin "9") (pinfunction "9_9") (pintype "passive"))
      (node (ref "R129") (pin "1") (pintype "passive"))
    )
    (net (code "131") (name "/Y8-in") (class "Default")
      (node (ref "J5") (pin "10") (pinfunction "10_10") (pintype "passive"))
      (node (ref "R127") (pin "1") (pintype "passive"))
    )
    (net (code "132") (name "/Y9-in") (class "Default")
      (node (ref "J5") (pin "11") (pinfunction "11_11") (pintype "passive"))
      (node (ref "R128") (pin "1") (pintype "passive"))
    )
    (net (code "133") (name "/Y10-in") (class "Default")
      (node (ref "JP2") (pin "2") (pinfunction "2_2") (pintype "passive"))
      (node (ref "R103") (pin "1") (pintype "passive"))
    )
    (net (code "134") (name "/Y11-in") (class "Default")
      (node (ref "JP2") (pin "3") (pinfunction "3_3") (pintype "passive"))
      (node (ref "R105") (pin "1") (pintype "passive"))
    )
    (net (code "135") (name "/Y12-in") (class "Default")
      (node (ref "J1") (pin "6") (pinfunction "6_6") (pintype "passive"))
      (node (ref "R142") (pin "1") (pintype "passive"))
    )
    (net (code "136") (name "/Y13-in") (class "Default")
      (node (ref "J1") (pin "7") (pinfunction "7_7") (pintype "passive"))
      (node (ref "R152") (pin "1") (pintype "passive"))
    )
    (net (code "137") (name "/Y14-in") (class "Default")
      (node (ref "J1") (pin "8") (pinfunction "8_8") (pintype "passive"))
      (node (ref "R153") (pin "1") (pintype "passive"))
    )
    (net (code "138") (name "/Y15-in") (class "Default")
      (node (ref "J1") (pin "9") (pinfunction "9_9") (pintype "passive"))
      (node (ref "R154") (pin "1") (pintype "passive"))
    )
    (net (code "139") (name "/Y16-in") (class "Default")
      (node (ref "J1") (pin "5") (pinfunction "5_5") (pintype "passive"))
      (node (ref "R188") (pin "1") (pintype "passive"))
    )
    (net (code "140") (name "/Y17-in") (class "Default")
      (node (ref "J1") (pin "4") (pinfunction "4_4") (pintype "passive"))
      (node (ref "R190") (pin "1") (pintype "passive"))
    )
    (net (code "141") (name "/Y18-in") (class "Default")
      (node (ref "J1") (pin "3") (pinfunction "3_3") (pintype "passive"))
      (node (ref "R192") (pin "1") (pintype "passive"))
    )
    (net (code "142") (name "/Y19-in") (class "Default")
      (node (ref "J1") (pin "1") (pinfunction "1_1") (pintype "passive"))
      (node (ref "R224") (pin "1") (pintype "passive"))
    )
    (net (code "143") (name "/Y20-in") (class "Default")
      (node (ref "JP2") (pin "4") (pinfunction "4_4") (pintype "passive"))
      (node (ref "R226") (pin "1") (pintype "passive"))
    )
    (net (code "144") (name "/Y21-in") (class "Default")
      (node (ref "J1") (pin "2") (pinfunction "2_2") (pintype "passive"))
      (node (ref "R194") (pin "1") (pintype "passive"))
    )
    (net (code "145") (name "/nRST") (class "Default")
      (node (ref "C28") (pin "2") (pinfunction "2_2") (pintype "passive"))
      (node (ref "J2") (pin "1") (pinfunction "1_1") (pintype "passive"))
      (node (ref "R21") (pin "2") (pinfunction "2_2") (pintype "passive"))
      (node (ref "R26") (pin "1") (pinfunction "1_1") (pintype "passive"))
      (node (ref "R27") (pin "2") (pinfunction "2_2") (pintype "passive"))
      (node (ref "U3") (pin "24") (pinfunction "RESET_24") (pintype "bidirectional"))
    )
    (net (code "146") (name "/run_buzzer") (class "Default")
      (node (ref "R110") (pin "2") (pintype "passive"))
      (node (ref "U3") (pin "78") (pinfunction "P4[6]/EMC_A[6]_78") (pintype "bidirectional"))
    )
    (net (code "147") (name "/sw0") (class "Default")
      (node (ref "C17") (pin "1") (pintype "passive"))
      (node (ref "L1") (pin "1") (pinfunction "1_1") (pintype "passive"))
      (node (ref "U1") (pin "3") (pinfunction "SW_3") (pintype "passive"))
    )
    (net (code "148") (name "/temp_C") (class "Default")
      (node (ref "C140") (pin "2") (pinfunction "2_2") (pintype "passive"))
      (node (ref "J13") (pin "1") (pinfunction "1_1") (pintype "passive"))
      (node (ref "R197") (pin "1") (pinfunction "1_1") (pintype "passive"))
      (node (ref "R198") (pin "1") (pinfunction "1_1") (pintype "passive"))
      (node (ref "U43") (pin "3") (pinfunction "IN+_3") (pintype "passive"))
    )
    (net (code "149") (name "/temp_D") (class "Default")
      (node (ref "C142") (pin "2") (pinfunction "2_2") (pintype "passive"))
      (node (ref "J13") (pin "3") (pinfunction "3_3") (pintype "passive"))
      (node (ref "R202") (pin "1") (pinfunction "1_1") (pintype "passive"))
      (node (ref "R203") (pin "1") (pinfunction "1_1") (pintype "passive"))
      (node (ref "U43") (pin "5") (pinfunction "IN+_5") (pintype "passive"))
    )
    (net (code "150") (name "/temp_E") (class "Default")
      (node (ref "C146") (pin "2") (pinfunction "2_2") (pintype "passive"))
      (node (ref "J13") (pin "5") (pinfunction "5_5") (pintype "passive"))
      (node (ref "R207") (pin "1") (pinfunction "1_1") (pintype "passive"))
      (node (ref "R208") (pin "1") (pinfunction "1_1") (pintype "passive"))
      (node (ref "U44") (pin "3") (pinfunction "IN+_3") (pintype "passive"))
    )
    (net (code "151") (name "/temp_F") (class "Default")
      (node (ref "C147") (pin "2") (pinfunction "2_2") (pintype "passive"))
      (node (ref "J13") (pin "7") (pinfunction "7_7") (pintype "passive"))
      (node (ref "R212") (pin "1") (pinfunction "1_1") (pintype "passive"))
      (node (ref "R213") (pin "1") (pinfunction "1_1") (pintype "passive"))
      (node (ref "U44") (pin "5") (pinfunction "IN+_5") (pintype "passive"))
    )
    (net (code "152") (name "12VD") (class "Default")
      (node (ref "C101") (pin "2") (pintype "passive"))
      (node (ref "C104") (pin "2") (pintype "passive"))
      (node (ref "C114") (pin "2") (pintype "passive"))
      (node (ref "C116") (pin "2") (pintype "passive"))
      (node (ref "C118") (pin "2") (pintype "passive"))
      (node (ref "C121") (pin "2") (pintype "passive"))
      (node (ref "C132") (pin "2") (pintype "passive"))
      (node (ref "C134") (pin "2") (pintype "passive"))
      (node (ref "C136") (pin "2") (pintype "passive"))
      (node (ref "C138") (pin "2") (pintype "passive"))
      (node (ref "C150") (pin "2") (pintype "passive"))
      (node (ref "C151") (pin "2") (pintype "passive"))
      (node (ref "C61") (pin "1") (pintype "passive"))
      (node (ref "C63") (pin "1") (pintype "passive"))
      (node (ref "C71") (pin "2") (pintype "passive"))
      (node (ref "C76") (pin "2") (pintype "passive"))
      (node (ref "C77") (pin "2") (pintype "passive"))
      (node (ref "C80") (pin "1") (pintype "passive"))
      (node (ref "C82") (pin "1") (pintype "passive"))
      (node (ref "C94") (pin "2") (pintype "passive"))
      (node (ref "C97") (pin "2") (pintype "passive"))
      (node (ref "C99") (pin "2") (pintype "passive"))
      (node (ref "JP2") (pin "6") (pinfunction "6_6") (pintype "passive"))
      (node (ref "Q15") (pin "3") (pinfunction "S_3") (pintype "passive"))
      (node (ref "Q17") (pin "3") (pinfunction "S_3") (pintype "passive"))
      (node (ref "R179") (pin "2") (pinfunction "2_2") (pintype "passive"))
      (node (ref "R186") (pin "2") (pinfunction "2_2") (pintype "passive"))
      (node (ref "UG1") (pin "1") (pintype "passive"))
      (node (ref "UG10") (pin "1") (pintype "passive"))
      (node (ref "UG11") (pin "1") (pintype "passive"))
      (node (ref "UG12") (pin "1") (pintype "passive"))
      (node (ref "UG13") (pin "1") (pintype "passive"))
      (node (ref "UG14") (pin "1") (pintype "passive"))
      (node (ref "UG15") (pin "1") (pintype "passive"))
      (node (ref "UG16") (pin "1") (pintype "passive"))
      (node (ref "UG19") (pin "1") (pintype "passive"))
      (node (ref "UG2") (pin "1") (pintype "passive"))
      (node (ref "UG20") (pin "1") (pintype "passive"))
      (node (ref "UG21") (pin "1") (pintype "passive"))
      (node (ref "UG22") (pin "1") (pintype "passive"))
      (node (ref "UG23") (pin "1") (pintype "passive"))
      (node (ref "UG24") (pin "1") (pintype "passive"))
      (node (ref "UG3") (pin "1") (pintype "passive"))
      (node (ref "UG4") (pin "1") (pintype "passive"))
      (node (ref "UG5") (pin "1") (pintype "passive"))
      (node (ref "UG6") (pin "1") (pintype "passive"))
      (node (ref "UG7") (pin "1") (pintype "passive"))
      (node (ref "UG8") (pin "1") (pintype "passive"))
      (node (ref "UG9") (pin "1") (pintype "passive"))
    )
    (net (code "153") (name "12VS") (class "Default")
      (node (ref "D1") (pin "1") (pinfunction "A_1") (pintype "passive"))
      (node (ref "D2") (pin "1") (pinfunction "A_1") (pintype "passive"))
      (node (ref "J13") (pin "11") (pinfunction "11_11") (pintype "passive"))
    )
    (net (code "154") (name "DC12V-1") (class "Default")
      (node (ref "JP1") (pin "3") (pinfunction "3_3") (pintype "passive"))
      (node (ref "RL1") (pin "3") (pinfunction "CM_3") (pintype "passive"))
    )
    (net (code "155") (name "DC12V-2") (class "Default")
      (node (ref "JP1") (pin "5") (pinfunction "5_5") (pintype "passive"))
      (node (ref "RL4") (pin "3") (pinfunction "CM_3") (pintype "passive"))
    )
    (net (code "156") (name "DC12V-3") (class "Default")
      (node (ref "J8") (pin "1") (pinfunction "1_1") (pintype "passive"))
      (node (ref "RL8") (pin "3") (pinfunction "CM_3") (pintype "passive"))
    )
    (net (code "157") (name "DC12V-4") (class "Default")
      (node (ref "J8") (pin "3") (pinfunction "3_3") (pintype "passive"))
      (node (ref "RL5") (pin "3") (pinfunction "CM_3") (pintype "passive"))
    )
    (net (code "158") (name "DC12V-5") (class "Default")
      (node (ref "J8") (pin "5") (pinfunction "5_5") (pintype "passive"))
      (node (ref "RL9") (pin "3") (pinfunction "CM_3") (pintype "passive"))
    )
    (net (code "159") (name "DC12V-6") (class "Default")
      (node (ref "J8") (pin "7") (pinfunction "7_7") (pintype "passive"))
      (node (ref "RL3") (pin "3") (pinfunction "CM_3") (pintype "passive"))
    )
    (net (code "160") (name "DC12V-7") (class "Default")
      (node (ref "J8") (pin "9") (pinfunction "9_9") (pintype "passive"))
      (node (ref "RL2") (pin "3") (pinfunction "CM_3") (pintype "passive"))
    )
    (net (code "161") (name "DC12V-8") (class "Default")
      (node (ref "J8") (pin "11") (pinfunction "11_11") (pintype "passive"))
      (node (ref "RL6") (pin "3") (pinfunction "CM_3") (pintype "passive"))
    )
    (net (code "162") (name "DC12V-9") (class "Default")
      (node (ref "J9") (pin "1") (pinfunction "1_1") (pintype "passive"))
      (node (ref "RL7") (pin "3") (pinfunction "CM_3") (pintype "passive"))
    )
    (net (code "163") (name "DC12V-10") (class "Default")
      (node (ref "J9") (pin "3") (pinfunction "3_3") (pintype "passive"))
      (node (ref "RL10") (pin "3") (pinfunction "CM_3") (pintype "passive"))
    )
    (net (code "164") (name "DC12V-11") (class "Default")
      (node (ref "J9") (pin "5") (pinfunction "5_5") (pintype "passive"))
      (node (ref "RL11") (pin "3") (pinfunction "CM_3") (pintype "passive"))
    )
    (net (code "165") (name "DC12V-12") (class "Default")
      (node (ref "J9") (pin "7") (pinfunction "7_7") (pintype "passive"))
      (node (ref "RL12") (pin "3") (pinfunction "CM_3") (pintype "passive"))
    )
    (net (code "166") (name "DC12V-13") (class "Default")
      (node (ref "J9") (pin "9") (pinfunction "9_9") (pintype "passive"))
      (node (ref "RL13") (pin "3") (pinfunction "CM_3") (pintype "passive"))
    )
    (net (code "167") (name "DC12V-14") (class "Default")
      (node (ref "J9") (pin "11") (pinfunction "11_11") (pintype "passive"))
      (node (ref "RL14") (pin "3") (pinfunction "CM_3") (pintype "passive"))
    )
    (net (code "168") (name "DC12V-15") (class "Default")
      (node (ref "J11") (pin "1") (pinfunction "1_1") (pintype "passive"))
      (node (ref "RL15") (pin "3") (pinfunction "CM_3") (pintype "passive"))
    )
    (net (code "169") (name "DC12V-16") (class "Default")
      (node (ref "J11") (pin "3") (pinfunction "3_3") (pintype "passive"))
      (node (ref "RL16") (pin "3") (pinfunction "CM_3") (pintype "passive"))
    )
    (net (code "170") (name "DC12V-17") (class "Default")
      (node (ref "J11") (pin "5") (pinfunction "5_5") (pintype "passive"))
      (node (ref "RL17") (pin "3") (pinfunction "CM_3") (pintype "passive"))
    )
    (net (code "171") (name "DC12V-18") (class "Default")
      (node (ref "J11") (pin "7") (pinfunction "7_7") (pintype "passive"))
      (node (ref "RL18") (pin "3") (pinfunction "CM_3") (pintype "passive"))
    )
    (net (code "172") (name "DC12V-19") (class "Default")
      (node (ref "J11") (pin "9") (pinfunction "9_9") (pintype "passive"))
      (node (ref "RL19") (pin "3") (pinfunction "CM_3") (pintype "passive"))
    )
    (net (code "173") (name "DC12V-20") (class "Default")
      (node (ref "J11") (pin "11") (pinfunction "11_11") (pintype "passive"))
      (node (ref "RL20") (pin "3") (pinfunction "CM_3") (pintype "passive"))
    )
    (net (code "174") (name "DGND") (class "Default")
      (node (ref "C1") (pin "2") (pinfunction "2_2") (pintype "passive"))
      (node (ref "C10") (pin "2") (pinfunction "2_2") (pintype "passive"))
      (node (ref "C100") (pin "2") (pintype "passive"))
      (node (ref "C102") (pin "2") (pintype "passive"))
      (node (ref "C103") (pin "2") (pintype "passive"))
      (node (ref "C105") (pin "2") (pintype "passive"))
      (node (ref "C108") (pin "1") (pinfunction "1_1") (pintype "passive"))
      (node (ref "C109") (pin "1") (pinfunction "1_1") (pintype "passive"))
      (node (ref "C11") (pin "2") (pinfunction "2_2") (pintype "passive"))
      (node (ref "C115") (pin "2") (pintype "passive"))
      (node (ref "C117") (pin "2") (pintype "passive"))
      (node (ref "C119") (pin "2") (pintype "passive"))
      (node (ref "C12") (pin "1") (pinfunction "1_1") (pintype "passive"))
      (node (ref "C122") (pin "2") (pintype "passive"))
      (node (ref "C123") (pin "1") (pinfunction "1_1") (pintype "passive"))
      (node (ref "C126") (pin "2") (pintype "passive"))
      (node (ref "C129") (pin "1") (pinfunction "1_1") (pintype "passive"))
      (node (ref "C13") (pin "2") (pinfunction "2_2") (pintype "passive"))
      (node (ref "C130") (pin "1") (pinfunction "1_1") (pintype "passive"))
      (node (ref "C133") (pin "2") (pintype "passive"))
      (node (ref "C135") (pin "2") (pintype "passive"))
      (node (ref "C137") (pin "2") (pintype "passive"))
      (node (ref "C139") (pin "2") (pintype "passive"))
      (node (ref "C14") (pin "2") (pinfunction "2_2") (pintype "passive"))
      (node (ref "C140") (pin "1") (pinfunction "1_1") (pintype "passive"))
      (node (ref "C141") (pin "1") (pinfunction "1_1") (pintype "passive"))
      (node (ref "C142") (pin "1") (pinfunction "1_1") (pintype "passive"))
      (node (ref "C143") (pin "1") (pinfunction "1_1") (pintype "passive"))
      (node (ref "C144") (pin "1") (pinfunction "1_1") (pintype "passive"))
      (node (ref "C145") (pin "1") (pinfunction "1_1") (pintype "passive"))
      (node (ref "C146") (pin "1") (pinfunction "1_1") (pintype "passive"))
      (node (ref "C147") (pin "1") (pinfunction "1_1") (pintype "passive"))
      (node (ref "C149") (pin "1") (pinfunction "1_1") (pintype "passive"))
      (node (ref "C15") (pin "2") (pinfunction "2_2") (pintype "passive"))
      (node (ref "C152") (pin "2") (pintype "passive"))
      (node (ref "C153") (pin "2") (pintype "passive"))
      (node (ref "C154") (pin "1") (pinfunction "1_1") (pintype "passive"))
      (node (ref "C16") (pin "2") (pinfunction "2_2") (pintype "passive"))
      (node (ref "C18") (pin "1") (pintype "passive"))
      (node (ref "C19") (pin "1") (pintype "passive"))
      (node (ref "C2") (pin "2") (pinfunction "2_2") (pintype "passive"))
      (node (ref "C20") (pin "1") (pintype "passive"))
      (node (ref "C22") (pin "2") (pinfunction "2_2") (pintype "passive"))
      (node (ref "C23") (pin "2") (pintype "passive"))
      (node (ref "C25") (pin "2") (pinfunction "2_2") (pintype "passive"))
      (node (ref "C26") (pin "2") (pintype "passive"))
      (node (ref "C27") (pin "1") (pinfunction "1_1") (pintype "passive"))
      (node (ref "C28") (pin "1") (pinfunction "1_1") (pintype "passive"))
      (node (ref "C3") (pin "2") (pinfunction "2_2") (pintype "passive"))
      (node (ref "C33") (pin "1") (pintype "passive"))
      (node (ref "C34") (pin "2") (pinfunction "2_2") (pintype "passive"))
      (node (ref "C35") (pin "2") (pintype "passive"))
      (node (ref "C37") (pin "1") (pintype "passive"))
      (node (ref "C39") (pin "2") (pinfunction "2_2") (pintype "passive"))
      (node (ref "C4") (pin "2") (pinfunction "2_2") (pintype "passive"))
      (node (ref "C40") (pin "1") (pintype "passive"))
      (node (ref "C41") (pin "2") (pinfunction "2_2") (pintype "passive"))
      (node (ref "C45") (pin "2") (pinfunction "2_2") (pintype "passive"))
      (node (ref "C46") (pin "2") (pinfunction "2_2") (pintype "passive"))
      (node (ref "C47") (pin "2") (pinfunction "2_2") (pintype "passive"))
      (node (ref "C48") (pin "2") (pinfunction "2_2") (pintype "passive"))
      (node (ref "C5") (pin "2") (pinfunction "2_2") (pintype "passive"))
      (node (ref "C53") (pin "2") (pintype "passive"))
      (node (ref "C54") (pin "1") (pinfunction "1_1") (pintype "passive"))
      (node (ref "C55") (pin "1") (pinfunction "1_1") (pintype "passive"))
      (node (ref "C6") (pin "2") (pinfunction "2_2") (pintype "passive"))
      (node (ref "C62") (pin "2") (pintype "passive"))
      (node (ref "C64") (pin "2") (pintype "passive"))
      (node (ref "C65") (pin "2") (pintype "passive"))
      (node (ref "C66") (pin "1") (pinfunction "1_1") (pintype "passive"))
      (node (ref "C67") (pin "2") (pintype "passive"))
      (node (ref "C68") (pin "1") (pinfunction "1_1") (pintype "passive"))
      (node (ref "C7") (pin "2") (pinfunction "2_2") (pintype "passive"))
      (node (ref "C70") (pin "1") (pinfunction "1_1") (pintype "passive"))
      (node (ref "C72") (pin "2") (pintype "passive"))
      (node (ref "C75") (pin "1") (pinfunction "1_1") (pintype "passive"))
      (node (ref "C8") (pin "2") (pinfunction "2_2") (pintype "passive"))
      (node (ref "C81") (pin "2") (pintype "passive"))
      (node (ref "C83") (pin "2") (pintype "passive"))
      (node (ref "C87") (pin "2") (pintype "passive"))
      (node (ref "C88") (pin "2") (pintype "passive"))
      (node (ref "C89") (pin "1") (pinfunction "1_1") (pintype "passive"))
      (node (ref "C9") (pin "2") (pinfunction "2_2") (pintype "passive"))
      (node (ref "C90") (pin "1") (pinfunction "1_1") (pintype "passive"))
      (node (ref "C91") (pin "1") (pinfunction "1_1") (pintype "passive"))
      (node (ref "C92") (pin "2") (pintype "passive"))
      (node (ref "C96") (pin "2") (pintype "passive"))
      (node (ref "C98") (pin "2") (pintype "passive"))
      (node (ref "DC1") (pin "2") (pinfunction "2_2") (pintype "passive"))
      (node (ref "DC2") (pin "2") (pinfunction "2_2") (pintype "passive"))
      (node (ref "EC1") (pin "2") (pinfunction "2_2") (pintype "passive"))
      (node (ref "EC2") (pin "2") (pinfunction "2_2") (pintype "passive"))
      (node (ref "J10") (pin "2") (pinfunction "2_2") (pintype "passive"))
      (node (ref "J10") (pin "6") (pinfunction "6_6") (pintype "passive"))
      (node (ref "J12") (pin "4") (pinfunction "4_4") (pintype "passive"))
      (node (ref "J13") (pin "2") (pinfunction "2_2") (pintype "passive"))
      (node (ref "J13") (pin "4") (pinfunction "4_4") (pintype "passive"))
      (node (ref "J13") (pin "6") (pinfunction "6_6") (pintype "passive"))
      (node (ref "J13") (pin "8") (pinfunction "8_8") (pintype "passive"))
      (node (ref "J2") (pin "5") (pinfunction "5_5") (pintype "passive"))
      (node (ref "J6") (pin "5") (pinfunction "5_5") (pintype "passive"))
      (node (ref "J6") (pin "9") (pinfunction "9_9") (pintype "passive"))
      (node (ref "L2") (pin "2") (pinfunction "2_2") (pintype "passive"))
      (node (ref "L3") (pin "2") (pinfunction "2_2") (pintype "passive"))
      (node (ref "L4") (pin "2") (pinfunction "2_2") (pintype "passive"))
      (node (ref "Q1") (pin "3") (pinfunction "E_3") (pintype "input"))
      (node (ref "Q10") (pin "3") (pinfunction "E_3") (pintype "input"))
      (node (ref "Q11") (pin "3") (pinfunction "E_3") (pintype "input"))
      (node (ref "Q12") (pin "3") (pinfunction "E_3") (pintype "input"))
      (node (ref "Q13") (pin "3") (pinfunction "E_3") (pintype "input"))
      (node (ref "Q14") (pin "3") (pinfunction "E_3") (pintype "input"))
      (node (ref "Q16") (pin "3") (pinfunction "E_3") (pintype "input"))
      (node (ref "Q18") (pin "3") (pinfunction "E_3") (pintype "input"))
      (node (ref "Q19") (pin "3") (pinfunction "E_3") (pintype "input"))
      (node (ref "Q20") (pin "3") (pinfunction "E_3") (pintype "input"))
      (node (ref "Q21") (pin "3") (pinfunction "E_3") (pintype "input"))
      (node (ref "Q22") (pin "3") (pinfunction "E_3") (pintype "input"))
      (node (ref "Q23") (pin "3") (pinfunction "E_3") (pintype "input"))
      (node (ref "Q24") (pin "3") (pinfunction "E_3") (pintype "input"))
      (node (ref "Q25") (pin "3") (pinfunction "E_3") (pintype "input"))
      (node (ref "Q26") (pin "3") (pinfunction "E_3") (pintype "input"))
      (node (ref "Q27") (pin "3") (pinfunction "E_3") (pintype "input"))
      (node (ref "Q28") (pin "3") (pinfunction "E_3") (pintype "input"))
      (node (ref "Q3") (pin "3") (pinfunction "E_3") (pintype "input"))
      (node (ref "Q4") (pin "3") (pinfunction "E_3") (pintype "input"))
      (node (ref "Q5") (pin "3") (pinfunction "E_3") (pintype "input"))
      (node (ref "Q6") (pin "3") (pinfunction "E_3") (pintype "input"))
      (node (ref "Q7") (pin "3") (pinfunction "E_3") (pintype "input"))
      (node (ref "Q8") (pin "3") (pinfunction "E_3") (pintype "input"))
      (node (ref "Q9") (pin "3") (pinfunction "E_3") (pintype "input"))
      (node (ref "R106") (pin "1") (pinfunction "1_1") (pintype "passive"))
      (node (ref "R107") (pin "1") (pinfunction "1_1") (pintype "passive"))
      (node (ref "R108") (pin "1") (pinfunction "1_1") (pintype "passive"))
      (node (ref "R111") (pin "1") (pinfunction "1_1") (pintype "passive"))
      (node (ref "R125") (pin "1") (pinfunction "1_1") (pintype "passive"))
      (node (ref "R126") (pin "1") (pinfunction "1_1") (pintype "passive"))
      (node (ref "R134") (pin "1") (pinfunction "1_1") (pintype "passive"))
      (node (ref "R136") (pin "1") (pinfunction "1_1") (pintype "passive"))
      (node (ref "R145") (pin "1") (pinfunction "1_1") (pintype "passive"))
      (node (ref "R157") (pin "1") (pinfunction "1_1") (pintype "passive"))
      (node (ref "R160") (pin "1") (pinfunction "1_1") (pintype "passive"))
      (node (ref "R163") (pin "1") (pinfunction "1_1") (pintype "passive"))
      (node (ref "R178") (pin "1") (pinfunction "1_1") (pintype "passive"))
      (node (ref "R185") (pin "1") (pinfunction "1_1") (pintype "passive"))
      (node (ref "R200") (pin "1") (pinfunction "1_1") (pintype "passive"))
      (node (ref "R205") (pin "1") (pinfunction "1_1") (pintype "passive"))
      (node (ref "R210") (pin "1") (pinfunction "1_1") (pintype "passive"))
      (node (ref "R215") (pin "1") (pinfunction "1_1") (pintype "passive"))
      (node (ref "R218") (pin "1") (pinfunction "1_1") (pintype "passive"))
      (node (ref "R219") (pin "1") (pinfunction "1_1") (pintype "passive"))
      (node (ref "R223") (pin "1") (pinfunction "1_1") (pintype "passive"))
      (node (ref "R33") (pin "1") (pinfunction "1_1") (pintype "passive"))
      (node (ref "R5") (pin "2") (pintype "passive"))
      (node (ref "R6") (pin "1") (pinfunction "1_1") (pintype "passive"))
      (node (ref "R7") (pin "2") (pintype "passive"))
      (node (ref "R73") (pin "1") (pinfunction "1_1") (pintype "passive"))
      (node (ref "R74") (pin "1") (pinfunction "1_1") (pintype "passive"))
      (node (ref "R75") (pin "1") (pinfunction "1_1") (pintype "passive"))
      (node (ref "R82") (pin "1") (pinfunction "1_1") (pintype "passive"))
      (node (ref "R83") (pin "1") (pinfunction "1_1") (pintype "passive"))
      (node (ref "R84") (pin "1") (pinfunction "1_1") (pintype "passive"))
      (node (ref "R85") (pin "1") (pinfunction "1_1") (pintype "passive"))
      (node (ref "R97") (pin "1") (pinfunction "1_1") (pintype "passive"))
      (node (ref "SW2") (pin "1") (pinfunction "COMMON_1") (pintype "passive"))
      (node (ref "SW3") (pin "2") (pinfunction "2_2") (pintype "passive"))
      (node (ref "SW4") (pin "1") (pinfunction "COMMON_1") (pintype "passive"))
      (node (ref "TVS6") (pin "1") (pintype "passive"))
      (node (ref "U1") (pin "4") (pinfunction "GND_4") (pintype "passive"))
      (node (ref "U10") (pin "4") (pinfunction "VSS_4") (pintype "passive"))
      (node (ref "U15") (pin "1") (pinfunction "GND_1") (pintype "passive"))
      (node (ref "U2") (pin "3") (pinfunction "Gnd_3") (pintype "passive"))
      (node (ref "U2") (pin "6") (pinfunction "G_6") (pintype "passive"))
      (node (ref "U3") (pin "103") (pinfunction "VSS_103") (pintype "bidirectional"))
      (node (ref "U3") (pin "117") (pinfunction "VSS_117") (pintype "bidirectional"))
      (node (ref "U3") (pin "119") (pinfunction "VSSREG_119") (pintype "bidirectional"))
      (node (ref "U3") (pin "139") (pinfunction "VSS_139") (pintype "bidirectional"))
      (node (ref "U3") (pin "22") (pinfunction "VSSREG_22") (pintype "bidirectional"))
      (node (ref "U3") (pin "44") (pinfunction "VSS_44") (pintype "bidirectional"))
      (node (ref "U3") (pin "59") (pinfunction "VSSREG_59") (pintype "bidirectional"))
      (node (ref "U3") (pin "65") (pinfunction "VSS_65") (pintype "bidirectional"))
      (node (ref "U3") (pin "79") (pinfunction "VSS_79") (pintype "bidirectional"))
      (node (ref "U37") (pin "2") (pinfunction "A_2") (pintype "passive"))
      (node (ref "U38") (pin "2") (pinfunction "A_2") (pintype "passive"))
      (node (ref "U4") (pin "2") (pinfunction "GND_2") (pintype "passive"))
      (node (ref "U40") (pin "2") (pinfunction "A_2") (pintype "passive"))
      (node (ref "U41") (pin "2") (pinfunction "A_2") (pintype "passive"))
      (node (ref "U43") (pin "4") (pinfunction "GND_4") (pintype "passive"))
      (node (ref "U44") (pin "4") (pinfunction "GND_4") (pintype "passive"))
      (node (ref "U5") (pin "3") (pinfunction "GND_3") (pintype "passive"))
      (node (ref "U5") (pin "4") (pinfunction "PFI_4") (pintype "passive"))
      (node (ref "U6") (pin "2") (pinfunction "GND_2") (pintype "passive"))
      (node (ref "U7") (pin "15") (pinfunction "GND_15") (pintype "passive"))
      (node (ref "U8") (pin "2") (pinfunction "GND_2") (pintype "passive"))
      (node (ref "U9") (pin "2") (pinfunction "GND_2") (pintype "passive"))
      (node (ref "UG1") (pin "3") (pintype "passive"))
      (node (ref "UG10") (pin "3") (pintype "passive"))
      (node (ref "UG11") (pin "3") (pintype "passive"))
      (node (ref "UG12") (pin "3") (pintype "passive"))
      (node (ref "UG13") (pin "3") (pintype "passive"))
      (node (ref "UG14") (pin "3") (pintype "passive"))
      (node (ref "UG15") (pin "3") (pintype "passive"))
      (node (ref "UG16") (pin "3") (pintype "passive"))
      (node (ref "UG19") (pin "3") (pintype "passive"))
      (node (ref "UG2") (pin "3") (pintype "passive"))
      (node (ref "UG20") (pin "3") (pintype "passive"))
      (node (ref "UG21") (pin "3") (pintype "passive"))
      (node (ref "UG22") (pin "3") (pintype "passive"))
      (node (ref "UG23") (pin "3") (pintype "passive"))
      (node (ref "UG24") (pin "3") (pintype "passive"))
      (node (ref "UG3") (pin "3") (pintype "passive"))
      (node (ref "UG4") (pin "3") (pintype "passive"))
      (node (ref "UG5") (pin "3") (pintype "passive"))
      (node (ref "UG6") (pin "3") (pintype "passive"))
      (node (ref "UG7") (pin "3") (pintype "passive"))
      (node (ref "UG8") (pin "3") (pintype "passive"))
      (node (ref "UG9") (pin "3") (pintype "passive"))
    )
    (net (code "175") (name "DP3V3") (class "Default")
      (node (ref "C1") (pin "1") (pinfunction "1_1") (pintype "passive"))
      (node (ref "C10") (pin "1") (pinfunction "1_1") (pintype "passive"))
      (node (ref "C11") (pin "1") (pinfunction "1_1") (pintype "passive"))
      (node (ref "C12") (pin "2") (pinfunction "2_2") (pintype "passive"))
      (node (ref "C13") (pin "1") (pinfunction "1_1") (pintype "passive"))
      (node (ref "C14") (pin "1") (pinfunction "1_1") (pintype "passive"))
      (node (ref "C15") (pin "1") (pinfunction "1_1") (pintype "passive"))
      (node (ref "C16") (pin "1") (pinfunction "1_1") (pintype "passive"))
      (node (ref "C2") (pin "1") (pinfunction "1_1") (pintype "passive"))
      (node (ref "C22") (pin "1") (pinfunction "1_1") (pintype "passive"))
      (node (ref "C23") (pin "1") (pintype "passive"))
      (node (ref "C24") (pin "1") (pinfunction "1_1") (pintype "passive"))
      (node (ref "C25") (pin "1") (pinfunction "1_1") (pintype "passive"))
      (node (ref "C26") (pin "1") (pintype "passive"))
      (node (ref "C3") (pin "1") (pinfunction "1_1") (pintype "passive"))
      (node (ref "C32") (pin "2") (pintype "passive"))
      (node (ref "C33") (pin "2") (pintype "passive"))
      (node (ref "C34") (pin "1") (pinfunction "1_1") (pintype "passive"))
      (node (ref "C35") (pin "1") (pintype "passive"))
      (node (ref "C39") (pin "1") (pinfunction "1_1") (pintype "passive"))
      (node (ref "C4") (pin "1") (pinfunction "1_1") (pintype "passive"))
      (node (ref "C40") (pin "2") (pintype "passive"))
      (node (ref "C41") (pin "1") (pinfunction "1_1") (pintype "passive"))
      (node (ref "C5") (pin "1") (pinfunction "1_1") (pintype "passive"))
      (node (ref "C6") (pin "1") (pinfunction "1_1") (pintype "passive"))
      (node (ref "C7") (pin "1") (pinfunction "1_1") (pintype "passive"))
      (node (ref "C8") (pin "1") (pinfunction "1_1") (pintype "passive"))
      (node (ref "C9") (pin "1") (pinfunction "1_1") (pintype "passive"))
      (node (ref "D10") (pin "1") (pintype "passive"))
      (node (ref "D11") (pin "1") (pintype "passive"))
      (node (ref "D7") (pin "1") (pintype "passive"))
      (node (ref "D8") (pin "1") (pintype "passive"))
      (node (ref "D9") (pin "1") (pinfunction "A_1") (pintype "passive"))
      (node (ref "EC1") (pin "1") (pinfunction "1_1") (pintype "passive"))
      (node (ref "EC2") (pin "1") (pinfunction "1_1") (pintype "passive"))
      (node (ref "J2") (pin "6") (pinfunction "6_6") (pintype "passive"))
      (node (ref "R104") (pin "1") (pinfunction "1_1") (pintype "passive"))
      (node (ref "R113") (pin "1") (pinfunction "1_1") (pintype "passive"))
      (node (ref "R114") (pin "1") (pinfunction "1_1") (pintype "passive"))
      (node (ref "R115") (pin "1") (pinfunction "1_1") (pintype "passive"))
      (node (ref "R120") (pin "1") (pinfunction "1_1") (pintype "passive"))
      (node (ref "R130") (pin "1") (pinfunction "1_1") (pintype "passive"))
      (node (ref "R137") (pin "2") (pinfunction "2_2") (pintype "passive"))
      (node (ref "R148") (pin "1") (pinfunction "1_1") (pintype "passive"))
      (node (ref "R15") (pin "2") (pintype "passive"))
      (node (ref "R150") (pin "1") (pinfunction "1_1") (pintype "passive"))
      (node (ref "R151") (pin "1") (pinfunction "1_1") (pintype "passive"))
      (node (ref "R16") (pin "2") (pinfunction "2_2") (pintype "passive"))
      (node (ref "R176") (pin "1") (pinfunction "1_1") (pintype "passive"))
      (node (ref "R18") (pin "2") (pinfunction "2_2") (pintype "passive"))
      (node (ref "R182") (pin "1") (pinfunction "1_1") (pintype "passive"))
      (node (ref "R189") (pin "1") (pinfunction "1_1") (pintype "passive"))
      (node (ref "R19") (pin "1") (pinfunction "1_1") (pintype "passive"))
      (node (ref "R191") (pin "1") (pinfunction "1_1") (pintype "passive"))
      (node (ref "R193") (pin "1") (pinfunction "1_1") (pintype "passive"))
      (node (ref "R195") (pin "1") (pinfunction "1_1") (pintype "passive"))
      (node (ref "R196") (pin "2") (pintype "passive"))
      (node (ref "R20") (pin "1") (pinfunction "1_1") (pintype "passive"))
      (node (ref "R201") (pin "2") (pintype "passive"))
      (node (ref "R206") (pin "2") (pintype "passive"))
      (node (ref "R21") (pin "1") (pinfunction "1_1") (pintype "passive"))
      (node (ref "R211") (pin "2") (pintype "passive"))
      (node (ref "R22") (pin "2") (pintype "passive"))
      (node (ref "R225") (pin "1") (pinfunction "1_1") (pintype "passive"))
      (node (ref "R227") (pin "1") (pinfunction "1_1") (pintype "passive"))
      (node (ref "R23") (pin "2") (pintype "passive"))
      (node (ref "R26") (pin "2") (pinfunction "2_2") (pintype "passive"))
      (node (ref "R3") (pin "2") (pinfunction "2_2") (pintype "passive"))
      (node (ref "R30") (pin "2") (pinfunction "2_2") (pintype "passive"))
      (node (ref "R31") (pin "2") (pinfunction "2_2") (pintype "passive"))
      (node (ref "R47") (pin "1") (pinfunction "1_1") (pintype "passive"))
      (node (ref "R48") (pin "1") (pinfunction "1_1") (pintype "passive"))
      (node (ref "R49") (pin "1") (pinfunction "1_1") (pintype "passive"))
      (node (ref "R50") (pin "1") (pinfunction "1_1") (pintype "passive"))
      (node (ref "R52") (pin "1") (pinfunction "1_1") (pintype "passive"))
      (node (ref "R54") (pin "1") (pinfunction "1_1") (pintype "passive"))
      (node (ref "R59") (pin "2") (pinfunction "2_2") (pintype "passive"))
      (node (ref "R66") (pin "1") (pinfunction "1_1") (pintype "passive"))
      (node (ref "R67") (pin "1") (pinfunction "1_1") (pintype "passive"))
      (node (ref "R76") (pin "1") (pinfunction "1_1") (pintype "passive"))
      (node (ref "R8") (pin "2") (pintype "passive"))
      (node (ref "R86") (pin "1") (pinfunction "1_1") (pintype "passive"))
      (node (ref "R87") (pin "1") (pinfunction "1_1") (pintype "passive"))
      (node (ref "R9") (pin "2") (pintype "passive"))
      (node (ref "R91") (pin "1") (pinfunction "1_1") (pintype "passive"))
      (node (ref "R92") (pin "1") (pinfunction "1_1") (pintype "passive"))
      (node (ref "U10") (pin "8") (pinfunction "VDD_8") (pintype "passive"))
      (node (ref "U2") (pin "4") (pinfunction "Vout_4") (pintype "passive"))
      (node (ref "U3") (pin "102") (pinfunction "VDD_102") (pintype "bidirectional"))
      (node (ref "U3") (pin "114") (pinfunction "VDD_114") (pintype "bidirectional"))
      (node (ref "U3") (pin "121") (pinfunction "VDD_121") (pintype "bidirectional"))
      (node (ref "U3") (pin "138") (pinfunction "VDD_138") (pintype "bidirectional"))
      (node (ref "U3") (pin "18") (pinfunction "VDD_18") (pintype "bidirectional"))
      (node (ref "U3") (pin "41") (pinfunction "VDD_41") (pintype "bidirectional"))
      (node (ref "U3") (pin "60") (pinfunction "VDD_60") (pintype "bidirectional"))
      (node (ref "U3") (pin "62") (pinfunction "VDD_62") (pintype "bidirectional"))
      (node (ref "U3") (pin "77") (pinfunction "VDD_77") (pintype "bidirectional"))
      (node (ref "U4") (pin "1") (pinfunction "VCC_1") (pintype "passive"))
      (node (ref "U43") (pin "8") (pinfunction "VCC_8") (pintype "passive"))
      (node (ref "U44") (pin "8") (pinfunction "VCC_8") (pintype "passive"))
      (node (ref "U5") (pin "2") (pinfunction "VCC_2") (pintype "passive"))
      (node (ref "U6") (pin "1") (pinfunction "VCC_1") (pintype "passive"))
      (node (ref "U7") (pin "16") (pinfunction "VCC_16") (pintype "passive"))
      (node (ref "U8") (pin "1") (pinfunction "VCC_1") (pintype "passive"))
      (node (ref "U9") (pin "1") (pinfunction "VCC_1") (pintype "passive"))
    )
    (net (code "176") (name "FGND") (class "Default")
      (node (ref "J13") (pin "12") (pinfunction "12_12") (pintype "passive"))
      (node (ref "L2") (pin "1") (pinfunction "1_1") (pintype "passive"))
      (node (ref "L3") (pin "1") (pinfunction "1_1") (pintype "passive"))
    )
    (net (code "177") (name "Net-(C21-Pad2)") (class "Default")
      (node (ref "C21") (pin "2") (pintype "passive"))
      (node (ref "R7") (pin "1") (pintype "passive"))
    )
    (net (code "178") (name "Net-(C30-Pad1)") (class "Default")
      (node (ref "C30") (pin "1") (pinfunction "1_1") (pintype "passive"))
      (node (ref "R36") (pin "1") (pinfunction "1_1") (pintype "passive"))
      (node (ref "TVS5") (pin "1") (pintype "passive"))
    )
    (net (code "179") (name "Net-(C38-Pad2)") (class "Default")
      (node (ref "C38") (pin "2") (pinfunction "2_2") (pintype "passive"))
      (node (ref "R46") (pin "2") (pinfunction "2_2") (pintype "passive"))
      (node (ref "TVS10") (pin "1") (pintype "passive"))
    )
    (net (code "180") (name "Net-(C61-Pad2)") (class "Default")
      (node (ref "C61") (pin "2") (pintype "passive"))
      (node (ref "R71") (pin "2") (pinfunction "2_2") (pintype "passive"))
      (node (ref "UG1") (pin "2") (pintype "passive"))
    )
    (net (code "181") (name "Net-(C63-Pad2)") (class "Default")
      (node (ref "C63") (pin "2") (pintype "passive"))
      (node (ref "R72") (pin "2") (pinfunction "2_2") (pintype "passive"))
      (node (ref "UG2") (pin "2") (pintype "passive"))
    )
    (net (code "182") (name "Net-(C71-Pad1)") (class "Default")
      (node (ref "C71") (pin "1") (pintype "passive"))
      (node (ref "R128") (pin "2") (pintype "passive"))
      (node (ref "UG10") (pin "2") (pintype "passive"))
    )
    (net (code "183") (name "Net-(C76-Pad1)") (class "Default")
      (node (ref "C76") (pin "1") (pintype "passive"))
      (node (ref "R103") (pin "2") (pintype "passive"))
      (node (ref "UG11") (pin "2") (pintype "passive"))
    )
    (net (code "184") (name "Net-(C77-Pad1)") (class "Default")
      (node (ref "C77") (pin "1") (pintype "passive"))
      (node (ref "R129") (pin "2") (pintype "passive"))
      (node (ref "UG8") (pin "2") (pintype "passive"))
    )
    (net (code "185") (name "Net-(C80-Pad2)") (class "Default")
      (node (ref "C80") (pin "2") (pintype "passive"))
      (node (ref "R89") (pin "2") (pinfunction "2_2") (pintype "passive"))
      (node (ref "UG3") (pin "2") (pintype "passive"))
    )
    (net (code "186") (name "Net-(C82-Pad2)") (class "Default")
      (node (ref "C82") (pin "2") (pintype "passive"))
      (node (ref "R90") (pin "2") (pinfunction "2_2") (pintype "passive"))
      (node (ref "UG4") (pin "2") (pintype "passive"))
    )
    (net (code "187") (name "Net-(C94-Pad1)") (class "Default")
      (node (ref "C94") (pin "1") (pintype "passive"))
      (node (ref "R127") (pin "2") (pintype "passive"))
      (node (ref "UG9") (pin "2") (pintype "passive"))
    )
    (net (code "188") (name "Net-(C97-Pad1)") (class "Default")
      (node (ref "C97") (pin "1") (pintype "passive"))
      (node (ref "R117") (pin "2") (pintype "passive"))
      (node (ref "UG5") (pin "2") (pintype "passive"))
    )
    (net (code "189") (name "Net-(C99-Pad1)") (class "Default")
      (node (ref "C99") (pin "1") (pintype "passive"))
      (node (ref "R118") (pin "2") (pintype "passive"))
      (node (ref "UG6") (pin "2") (pintype "passive"))
    )
    (net (code "190") (name "Net-(C101-Pad1)") (class "Default")
      (node (ref "C101") (pin "1") (pintype "passive"))
      (node (ref "R105") (pin "2") (pintype "passive"))
      (node (ref "UG12") (pin "2") (pintype "passive"))
    )
    (net (code "191") (name "Net-(C104-Pad1)") (class "Default")
      (node (ref "C104") (pin "1") (pintype "passive"))
      (node (ref "R119") (pin "2") (pintype "passive"))
      (node (ref "UG7") (pin "2") (pintype "passive"))
    )
    (net (code "192") (name "Net-(C110-Pad1)") (class "Default")
      (node (ref "C110") (pin "1") (pintype "passive"))
      (node (ref "R176") (pin "2") (pinfunction "2_2") (pintype "passive"))
      (node (ref "UG17") (pin "1") (pintype "passive"))
    )
    (net (code "193") (name "Net-(C111-Pad1)") (class "Default")
      (node (ref "C111") (pin "1") (pintype "passive"))
      (node (ref "R182") (pin "2") (pinfunction "2_2") (pintype "passive"))
      (node (ref "UG18") (pin "1") (pintype "passive"))
    )
    (net (code "194") (name "Net-(C114-Pad1)") (class "Default")
      (node (ref "C114") (pin "1") (pintype "passive"))
      (node (ref "R152") (pin "2") (pintype "passive"))
      (node (ref "UG14") (pin "2") (pintype "passive"))
    )
    (net (code "195") (name "Net-(C116-Pad1)") (class "Default")
      (node (ref "C116") (pin "1") (pintype "passive"))
      (node (ref "R153") (pin "2") (pintype "passive"))
      (node (ref "UG15") (pin "2") (pintype "passive"))
    )
    (net (code "196") (name "Net-(C118-Pad1)") (class "Default")
      (node (ref "C118") (pin "1") (pintype "passive"))
      (node (ref "R154") (pin "2") (pintype "passive"))
      (node (ref "UG16") (pin "2") (pintype "passive"))
    )
    (net (code "197") (name "Net-(C121-Pad1)") (class "Default")
      (node (ref "C121") (pin "1") (pintype "passive"))
      (node (ref "R142") (pin "2") (pintype "passive"))
      (node (ref "UG13") (pin "2") (pintype "passive"))
    )
    (net (code "198") (name "Net-(C132-Pad1)") (class "Default")
      (node (ref "C132") (pin "1") (pintype "passive"))
      (node (ref "R188") (pin "2") (pintype "passive"))
      (node (ref "UG19") (pin "2") (pintype "passive"))
    )
    (net (code "199") (name "Net-(C134-Pad1)") (class "Default")
      (node (ref "C134") (pin "1") (pintype "passive"))
      (node (ref "R190") (pin "2") (pintype "passive"))
      (node (ref "UG20") (pin "2") (pintype "passive"))
    )
    (net (code "200") (name "Net-(C136-Pad1)") (class "Default")
      (node (ref "C136") (pin "1") (pintype "passive"))
      (node (ref "R192") (pin "2") (pintype "passive"))
      (node (ref "UG21") (pin "2") (pintype "passive"))
    )
    (net (code "201") (name "Net-(C138-Pad1)") (class "Default")
      (node (ref "C138") (pin "1") (pintype "passive"))
      (node (ref "R194") (pin "2") (pintype "passive"))
      (node (ref "UG22") (pin "2") (pintype "passive"))
    )
    (net (code "202") (name "Net-(C150-Pad1)") (class "Default")
      (node (ref "C150") (pin "1") (pintype "passive"))
      (node (ref "R224") (pin "2") (pintype "passive"))
      (node (ref "UG23") (pin "2") (pintype "passive"))
    )
    (net (code "203") (name "Net-(C151-Pad1)") (class "Default")
      (node (ref "C151") (pin "1") (pintype "passive"))
      (node (ref "R226") (pin "2") (pintype "passive"))
      (node (ref "UG24") (pin "2") (pintype "passive"))
    )
    (net (code "204") (name "Net-(D3-Pad1)") (class "Default")
      (node (ref "D3") (pin "1") (pintype "passive"))
      (node (ref "R8") (pin "1") (pintype "passive"))
    )
    (net (code "205") (name "Net-(D4-Pad1)") (class "Default")
      (node (ref "D4") (pin "1") (pintype "passive"))
      (node (ref "R9") (pin "1") (pintype "passive"))
    )
    (net (code "206") (name "Net-(D5-Pad1)") (class "Default")
      (node (ref "D5") (pin "1") (pintype "passive"))
      (node (ref "R22") (pin "1") (pintype "passive"))
    )
    (net (code "207") (name "Net-(D6-Pad1)") (class "Default")
      (node (ref "D6") (pin "1") (pintype "passive"))
      (node (ref "R23") (pin "1") (pintype "passive"))
    )
    (net (code "208") (name "Net-(D7-Pad2)") (class "Default")
      (node (ref "D7") (pin "2") (pintype "passive"))
      (node (ref "R41") (pin "1") (pinfunction "1_1") (pintype "passive"))
    )
    (net (code "209") (name "Net-(D8-Pad2)") (class "Default")
      (node (ref "D8") (pin "2") (pintype "passive"))
      (node (ref "R38") (pin "1") (pinfunction "1_1") (pintype "passive"))
    )
    (net (code "210") (name "Net-(D9-K)") (class "Default")
      (node (ref "D9") (pin "2") (pinfunction "K_2") (pintype "passive"))
      (node (ref "U3") (pin "27") (pinfunction "VBAT_27") (pintype "bidirectional"))
    )
    (net (code "211") (name "Net-(D10-Pad2)") (class "Default")
      (node (ref "D10") (pin "2") (pintype "passive"))
      (node (ref "R56") (pin "1") (pinfunction "1_1") (pintype "passive"))
    )
    (net (code "212") (name "Net-(D11-Pad2)") (class "Default")
      (node (ref "D11") (pin "2") (pintype "passive"))
      (node (ref "R51") (pin "1") (pinfunction "1_1") (pintype "passive"))
    )
    (net (code "213") (name "Net-(D12-A)") (class "Default")
      (node (ref "C49") (pin "2") (pintype "passive"))
      (node (ref "D12") (pin "1") (pinfunction "A_1") (pintype "passive"))
      (node (ref "LED2") (pin "2") (pintype "passive"))
      (node (ref "Q3") (pin "2") (pinfunction "C_2") (pintype "input"))
      (node (ref "RL1") (pin "1") (pinfunction "+_1") (pintype "passive"))
    )
    (net (code "214") (name "Net-(D13-A)") (class "Default")
      (node (ref "C50") (pin "2") (pintype "passive"))
      (node (ref "D13") (pin "1") (pinfunction "A_1") (pintype "passive"))
      (node (ref "LED3") (pin "2") (pintype "passive"))
      (node (ref "Q4") (pin "2") (pinfunction "C_2") (pintype "input"))
      (node (ref "RL2") (pin "1") (pinfunction "+_1") (pintype "passive"))
    )
    (net (code "215") (name "Net-(D14-A)") (class "Default")
      (node (ref "C51") (pin "1") (pinfunction "1_1") (pintype "passive"))
      (node (ref "D14") (pin "1") (pinfunction "A_1") (pintype "passive"))
      (node (ref "LED4") (pin "2") (pintype "passive"))
      (node (ref "Q5") (pin "2") (pinfunction "C_2") (pintype "input"))
      (node (ref "RL3") (pin "1") (pinfunction "+_1") (pintype "passive"))
    )
    (net (code "216") (name "Net-(D15-A)") (class "Default")
      (node (ref "C52") (pin "1") (pinfunction "1_1") (pintype "passive"))
      (node (ref "D15") (pin "1") (pinfunction "A_1") (pintype "passive"))
      (node (ref "LED5") (pin "2") (pintype "passive"))
      (node (ref "Q6") (pin "2") (pinfunction "C_2") (pintype "input"))
      (node (ref "RL4") (pin "1") (pinfunction "+_1") (pintype "passive"))
    )
    (net (code "217") (name "Net-(D16-A)") (class "Default")
      (node (ref "C95") (pin "1") (pinfunction "1_1") (pintype "passive"))
      (node (ref "D16") (pin "1") (pinfunction "A_1") (pintype "passive"))
      (node (ref "LED13") (pin "2") (pintype "passive"))
      (node (ref "Q18") (pin "2") (pinfunction "C_2") (pintype "input"))
      (node (ref "RL12") (pin "1") (pinfunction "+_1") (pintype "passive"))
    )
    (net (code "218") (name "Net-(D17-A)") (class "Default")
      (node (ref "C79") (pin "2") (pintype "passive"))
      (node (ref "D17") (pin "1") (pinfunction "A_1") (pintype "passive"))
      (node (ref "LED6") (pin "2") (pintype "passive"))
      (node (ref "Q7") (pin "2") (pinfunction "C_2") (pintype "input"))
      (node (ref "RL5") (pin "1") (pinfunction "+_1") (pintype "passive"))
    )
    (net (code "219") (name "Net-(D18-A)") (class "Default")
      (node (ref "C84") (pin "1") (pinfunction "1_1") (pintype "passive"))
      (node (ref "D18") (pin "1") (pinfunction "A_1") (pintype "passive"))
      (node (ref "LED7") (pin "2") (pintype "passive"))
      (node (ref "Q8") (pin "2") (pinfunction "C_2") (pintype "input"))
      (node (ref "RL6") (pin "1") (pinfunction "+_1") (pintype "passive"))
    )
    (net (code "220") (name "Net-(D19-A)") (class "Default")
      (node (ref "C85") (pin "1") (pinfunction "1_1") (pintype "passive"))
      (node (ref "D19") (pin "1") (pinfunction "A_1") (pintype "passive"))
      (node (ref "LED8") (pin "2") (pintype "passive"))
      (node (ref "Q9") (pin "2") (pinfunction "C_2") (pintype "input"))
      (node (ref "RL7") (pin "1") (pinfunction "+_1") (pintype "passive"))
    )
    (net (code "221") (name "Net-(D20-A)") (class "Default")
      (node (ref "C86") (pin "1") (pinfunction "1_1") (pintype "passive"))
      (node (ref "D20") (pin "1") (pinfunction "A_1") (pintype "passive"))
      (node (ref "LED9") (pin "2") (pintype "passive"))
      (node (ref "Q10") (pin "2") (pinfunction "C_2") (pintype "input"))
      (node (ref "RL8") (pin "1") (pinfunction "+_1") (pintype "passive"))
    )
    (net (code "222") (name "Net-(D21-A)") (class "Default")
      (node (ref "C106") (pin "1") (pinfunction "1_1") (pintype "passive"))
      (node (ref "D21") (pin "1") (pinfunction "A_1") (pintype "passive"))
      (node (ref "LED10") (pin "2") (pintype "passive"))
      (node (ref "Q11") (pin "2") (pinfunction "C_2") (pintype "input"))
      (node (ref "RL9") (pin "1") (pinfunction "+_1") (pintype "passive"))
    )
    (net (code "223") (name "Net-(D22-A)") (class "Default")
      (node (ref "C107") (pin "1") (pinfunction "1_1") (pintype "passive"))
      (node (ref "D22") (pin "1") (pinfunction "A_1") (pintype "passive"))
      (node (ref "LED11") (pin "2") (pintype "passive"))
      (node (ref "Q12") (pin "2") (pinfunction "C_2") (pintype "input"))
      (node (ref "RL10") (pin "1") (pinfunction "+_1") (pintype "passive"))
    )
    (net (code "224") (name "Net-(D23-A)") (class "Default")
      (node (ref "C93") (pin "2") (pintype "passive"))
      (node (ref "D23") (pin "1") (pinfunction "A_1") (pintype "passive"))
      (node (ref "LED12") (pin "2") (pintype "passive"))
      (node (ref "Q13") (pin "2") (pinfunction "C_2") (pintype "input"))
      (node (ref "RL11") (pin "1") (pinfunction "+_1") (pintype "passive"))
    )
    (net (code "225") (name "Net-(D24-A)") (class "Default")
      (node (ref "C128") (pin "1") (pinfunction "1_1") (pintype "passive"))
      (node (ref "D24") (pin "1") (pinfunction "A_1") (pintype "passive"))
      (node (ref "LED14") (pin "2") (pintype "passive"))
      (node (ref "Q19") (pin "2") (pinfunction "C_2") (pintype "input"))
      (node (ref "RL13") (pin "1") (pinfunction "+_1") (pintype "passive"))
    )
    (net (code "226") (name "Net-(D25-A)") (class "Default")
      (node (ref "C127") (pin "1") (pinfunction "1_1") (pintype "passive"))
      (node (ref "D25") (pin "1") (pinfunction "A_1") (pintype "passive"))
      (node (ref "LED15") (pin "2") (pintype "passive"))
      (node (ref "Q20") (pin "2") (pinfunction "C_2") (pintype "input"))
      (node (ref "RL14") (pin "1") (pinfunction "+_1") (pintype "passive"))
    )
    (net (code "227") (name "Net-(D26-A)") (class "Default")
      (node (ref "C59") (pin "2") (pintype "passive"))
      (node (ref "D26") (pin "1") (pinfunction "A_1") (pintype "passive"))
      (node (ref "LED16") (pin "2") (pintype "passive"))
      (node (ref "Q21") (pin "2") (pinfunction "C_2") (pintype "input"))
      (node (ref "RL15") (pin "1") (pinfunction "+_1") (pintype "passive"))
    )
    (net (code "228") (name "Net-(D27-A)") (class "Default")
      (node (ref "C125") (pin "1") (pinfunction "1_1") (pintype "passive"))
      (node (ref "D27") (pin "1") (pinfunction "A_1") (pintype "passive"))
      (node (ref "LED17") (pin "2") (pintype "passive"))
      (node (ref "Q22") (pin "2") (pinfunction "C_2") (pintype "input"))
      (node (ref "RL16") (pin "1") (pinfunction "+_1") (pintype "passive"))
    )
    (net (code "229") (name "Net-(D28-A)") (class "Default")
      (node (ref "C124") (pin "1") (pinfunction "1_1") (pintype "passive"))
      (node (ref "D28") (pin "1") (pinfunction "A_1") (pintype "passive"))
      (node (ref "LED18") (pin "2") (pintype "passive"))
      (node (ref "Q23") (pin "2") (pinfunction "C_2") (pintype "input"))
      (node (ref "RL17") (pin "1") (pinfunction "+_1") (pintype "passive"))
    )
    (net (code "230") (name "Net-(D29-A)") (class "Default")
      (node (ref "C58") (pin "2") (pintype "passive"))
      (node (ref "D29") (pin "1") (pinfunction "A_1") (pintype "passive"))
      (node (ref "LED19") (pin "2") (pintype "passive"))
      (node (ref "Q24") (pin "2") (pinfunction "C_2") (pintype "input"))
      (node (ref "RL18") (pin "1") (pinfunction "+_1") (pintype "passive"))
    )
    (net (code "231") (name "Net-(D30-A)") (class "Default")
      (node (ref "C131") (pin "1") (pinfunction "1_1") (pintype "passive"))
      (node (ref "D30") (pin "1") (pinfunction "A_1") (pintype "passive"))
      (node (ref "LED20") (pin "2") (pintype "passive"))
      (node (ref "Q25") (pin "2") (pinfunction "C_2") (pintype "input"))
      (node (ref "RL19") (pin "1") (pinfunction "+_1") (pintype "passive"))
    )
    (net (code "232") (name "Net-(D31-A)") (class "Default")
      (node (ref "C60") (pin "1") (pinfunction "1_1") (pintype "passive"))
      (node (ref "D31") (pin "1") (pinfunction "A_1") (pintype "passive"))
      (node (ref "LED21") (pin "2") (pintype "passive"))
      (node (ref "Q26") (pin "2") (pinfunction "C_2") (pintype "input"))
      (node (ref "RL20") (pin "1") (pinfunction "+_1") (pintype "passive"))
    )
    (net (code "233") (name "Net-(D32-A)") (class "Default")
      (node (ref "C148") (pin "1") (pinfunction "1_1") (pintype "passive"))
      (node (ref "D32") (pin "1") (pinfunction "A_1") (pintype "passive"))
      (node (ref "LED23") (pin "2") (pintype "passive"))
      (node (ref "Q27") (pin "2") (pinfunction "C_2") (pintype "input"))
      (node (ref "RL21") (pin "1") (pinfunction "+_1") (pintype "passive"))
    )
    (net (code "234") (name "Net-(D33-A)") (class "Default")
      (node (ref "D33") (pin "1") (pinfunction "A_1") (pintype "passive"))
      (node (ref "Q28") (pin "2") (pinfunction "C_2") (pintype "input"))
      (node (ref "U12") (pin "2") (pinfunction "B_2") (pintype "passive"))
    )
    (net (code "235") (name "Net-(D33-K)") (class "Default")
      (node (ref "D33") (pin "2") (pinfunction "K_2") (pintype "passive"))
      (node (ref "R220") (pin "1") (pintype "passive"))
      (node (ref "U12") (pin "1") (pinfunction "A_1") (pintype "passive"))
    )
    (net (code "236") (name "Net-(J10-Pad4)") (class "Default")
      (node (ref "J10") (pin "4") (pinfunction "4_4") (pintype "passive"))
      (node (ref "R140") (pin "1") (pinfunction "1_1") (pintype "passive"))
    )
    (net (code "237") (name "Net-(J10-Pad5)") (class "Default")
      (node (ref "J10") (pin "5") (pinfunction "5_5") (pintype "passive"))
      (node (ref "R141") (pin "1") (pinfunction "1_1") (pintype "passive"))
    )
    (net (code "238") (name "Net-(LED1-Pad1)") (class "Default")
      (node (ref "LED1") (pin "1") (pintype "passive"))
      (node (ref "R16") (pin "1") (pinfunction "1_1") (pintype "passive"))
    )
    (net (code "239") (name "Net-(LED2-Pad1)") (class "Default")
      (node (ref "LED2") (pin "1") (pintype "passive"))
      (node (ref "R60") (pin "1") (pinfunction "1_1") (pintype "passive"))
    )
    (net (code "240") (name "Net-(LED3-Pad1)") (class "Default")
      (node (ref "LED3") (pin "1") (pintype "passive"))
      (node (ref "R61") (pin "1") (pinfunction "1_1") (pintype "passive"))
    )
    (net (code "241") (name "Net-(LED4-Pad1)") (class "Default")
      (node (ref "LED4") (pin "1") (pintype "passive"))
      (node (ref "R63") (pin "1") (pinfunction "1_1") (pintype "passive"))
    )
    (net (code "242") (name "Net-(LED5-Pad1)") (class "Default")
      (node (ref "LED5") (pin "1") (pintype "passive"))
      (node (ref "R62") (pin "1") (pinfunction "1_1") (pintype "passive"))
    )
    (net (code "243") (name "Net-(LED6-Pad1)") (class "Default")
      (node (ref "LED6") (pin "1") (pintype "passive"))
      (node (ref "R93") (pin "1") (pinfunction "1_1") (pintype "passive"))
    )
    (net (code "244") (name "Net-(LED7-Pad1)") (class "Default")
      (node (ref "LED7") (pin "1") (pintype "passive"))
      (node (ref "R94") (pin "1") (pinfunction "1_1") (pintype "passive"))
    )
    (net (code "245") (name "Net-(LED8-Pad1)") (class "Default")
      (node (ref "LED8") (pin "1") (pintype "passive"))
      (node (ref "R95") (pin "1") (pinfunction "1_1") (pintype "passive"))
    )
    (net (code "246") (name "Net-(LED9-Pad1)") (class "Default")
      (node (ref "LED9") (pin "1") (pintype "passive"))
      (node (ref "R96") (pin "1") (pinfunction "1_1") (pintype "passive"))
    )
    (net (code "247") (name "Net-(LED10-Pad1)") (class "Default")
      (node (ref "LED10") (pin "1") (pintype "passive"))
      (node (ref "R121") (pin "1") (pinfunction "1_1") (pintype "passive"))
    )
    (net (code "248") (name "Net-(LED11-Pad1)") (class "Default")
      (node (ref "LED11") (pin "1") (pintype "passive"))
      (node (ref "R122") (pin "1") (pinfunction "1_1") (pintype "passive"))
    )
    (net (code "249") (name "Net-(LED12-Pad1)") (class "Default")
      (node (ref "LED12") (pin "1") (pintype "passive"))
      (node (ref "R131") (pin "1") (pinfunction "1_1") (pintype "passive"))
    )
    (net (code "250") (name "Net-(LED13-Pad1)") (class "Default")
      (node (ref "LED13") (pin "1") (pintype "passive"))
      (node (ref "R132") (pin "1") (pinfunction "1_1") (pintype "passive"))
    )
    (net (code "251") (name "Net-(LED14-Pad1)") (class "Default")
      (node (ref "LED14") (pin "1") (pintype "passive"))
      (node (ref "R64") (pin "1") (pinfunction "1_1") (pintype "passive"))
    )
    (net (code "252") (name "Net-(LED15-Pad1)") (class "Default")
      (node (ref "LED15") (pin "1") (pintype "passive"))
      (node (ref "R135") (pin "1") (pinfunction "1_1") (pintype "passive"))
    )
    (net (code "253") (name "Net-(LED16-Pad1)") (class "Default")
      (node (ref "LED16") (pin "1") (pintype "passive"))
      (node (ref "R143") (pin "1") (pinfunction "1_1") (pintype "passive"))
    )
    (net (code "254") (name "Net-(LED17-Pad1)") (class "Default")
      (node (ref "LED17") (pin "1") (pintype "passive"))
      (node (ref "R81") (pin "1") (pinfunction "1_1") (pintype "passive"))
    )
    (net (code "255") (name "Net-(LED18-Pad1)") (class "Default")
      (node (ref "LED18") (pin "1") (pintype "passive"))
      (node (ref "R147") (pin "1") (pinfunction "1_1") (pintype "passive"))
    )
    (net (code "256") (name "Net-(LED19-Pad1)") (class "Default")
      (node (ref "LED19") (pin "1") (pintype "passive"))
      (node (ref "R155") (pin "1") (pinfunction "1_1") (pintype "passive"))
    )
    (net (code "257") (name "Net-(LED20-Pad1)") (class "Default")
      (node (ref "LED20") (pin "1") (pintype "passive"))
      (node (ref "R158") (pin "1") (pinfunction "1_1") (pintype "passive"))
    )
    (net (code "258") (name "Net-(LED21-Pad1)") (class "Default")
      (node (ref "LED21") (pin "1") (pintype "passive"))
      (node (ref "R161") (pin "1") (pinfunction "1_1") (pintype "passive"))
    )
    (net (code "259") (name "Net-(LED23-Pad1)") (class "Default")
      (node (ref "LED23") (pin "1") (pintype "passive"))
      (node (ref "R221") (pin "1") (pinfunction "1_1") (pintype "passive"))
    )
    (net (code "260") (name "Net-(Q1-B)") (class "Default")
      (node (ref "Q1") (pin "1") (pinfunction "B_1") (pintype "input"))
      (node (ref "R29") (pin "2") (pinfunction "2_2") (pintype "passive"))
      (node (ref "R33") (pin "2") (pinfunction "2_2") (pintype "passive"))
    )
    (net (code "261") (name "Net-(Q1-C)") (class "Default")
      (node (ref "LED1") (pin "2") (pintype "passive"))
      (node (ref "Q1") (pin "2") (pinfunction "C_2") (pintype "input"))
    )
    (net (code "262") (name "Net-(Q2-B)") (class "Default")
      (node (ref "Q2") (pin "1") (pinfunction "B_1") (pintype "input"))
      (node (ref "R55") (pin "1") (pinfunction "1_1") (pintype "passive"))
      (node (ref "U11") (pin "3") (pinfunction "C_3") (pintype "passive"))
    )
    (net (code "263") (name "Net-(Q3-B)") (class "Default")
      (node (ref "C65") (pin "1") (pintype "passive"))
      (node (ref "Q3") (pin "1") (pinfunction "B_1") (pintype "input"))
      (node (ref "R77") (pin "2") (pinfunction "2_2") (pintype "passive"))
      (node (ref "R83") (pin "2") (pinfunction "2_2") (pintype "passive"))
    )
    (net (code "264") (name "Net-(Q4-B)") (class "Default")
      (node (ref "C67") (pin "1") (pintype "passive"))
      (node (ref "Q4") (pin "1") (pinfunction "B_1") (pintype "input"))
      (node (ref "R79") (pin "2") (pinfunction "2_2") (pintype "passive"))
      (node (ref "R85") (pin "2") (pinfunction "2_2") (pintype "passive"))
    )
    (net (code "265") (name "Net-(Q5-B)") (class "Default")
      (node (ref "C68") (pin "2") (pinfunction "2_2") (pintype "passive"))
      (node (ref "Q5") (pin "1") (pinfunction "B_1") (pintype "input"))
      (node (ref "R78") (pin "2") (pinfunction "2_2") (pintype "passive"))
      (node (ref "R82") (pin "2") (pinfunction "2_2") (pintype "passive"))
    )
    (net (code "266") (name "Net-(Q6-B)") (class "Default")
      (node (ref "C66") (pin "2") (pinfunction "2_2") (pintype "passive"))
      (node (ref "Q6") (pin "1") (pinfunction "B_1") (pintype "input"))
      (node (ref "R80") (pin "2") (pinfunction "2_2") (pintype "passive"))
      (node (ref "R84") (pin "2") (pinfunction "2_2") (pintype "passive"))
    )
    (net (code "267") (name "Net-(Q7-B)") (class "Default")
      (node (ref "C88") (pin "1") (pintype "passive"))
      (node (ref "Q7") (pin "1") (pinfunction "B_1") (pintype "input"))
      (node (ref "R107") (pin "2") (pinfunction "2_2") (pintype "passive"))
      (node (ref "R98") (pin "2") (pinfunction "2_2") (pintype "passive"))
    )
    (net (code "268") (name "Net-(Q8-B)") (class "Default")
      (node (ref "C90") (pin "2") (pinfunction "2_2") (pintype "passive"))
      (node (ref "Q8") (pin "1") (pinfunction "B_1") (pintype "input"))
      (node (ref "R106") (pin "2") (pinfunction "2_2") (pintype "passive"))
      (node (ref "R99") (pin "2") (pinfunction "2_2") (pintype "passive"))
    )
    (net (code "269") (name "Net-(Q9-B)") (class "Default")
      (node (ref "C89") (pin "2") (pinfunction "2_2") (pintype "passive"))
      (node (ref "Q9") (pin "1") (pinfunction "B_1") (pintype "input"))
      (node (ref "R100") (pin "2") (pinfunction "2_2") (pintype "passive"))
      (node (ref "R108") (pin "2") (pinfunction "2_2") (pintype "passive"))
    )
    (net (code "270") (name "Net-(Q10-B)") (class "Default")
      (node (ref "C91") (pin "2") (pinfunction "2_2") (pintype "passive"))
      (node (ref "Q10") (pin "1") (pinfunction "B_1") (pintype "input"))
      (node (ref "R102") (pin "2") (pinfunction "2_2") (pintype "passive"))
      (node (ref "R111") (pin "2") (pinfunction "2_2") (pintype "passive"))
    )
    (net (code "271") (name "Net-(Q11-B)") (class "Default")
      (node (ref "C108") (pin "2") (pinfunction "2_2") (pintype "passive"))
      (node (ref "Q11") (pin "1") (pinfunction "B_1") (pintype "input"))
      (node (ref "R123") (pin "2") (pinfunction "2_2") (pintype "passive"))
      (node (ref "R125") (pin "2") (pinfunction "2_2") (pintype "passive"))
    )
    (net (code "272") (name "Net-(Q12-B)") (class "Default")
      (node (ref "C109") (pin "2") (pinfunction "2_2") (pintype "passive"))
      (node (ref "Q12") (pin "1") (pinfunction "B_1") (pintype "input"))
      (node (ref "R124") (pin "2") (pinfunction "2_2") (pintype "passive"))
      (node (ref "R126") (pin "2") (pinfunction "2_2") (pintype "passive"))
    )
    (net (code "273") (name "Net-(Q13-B)") (class "Default")
      (node (ref "C53") (pin "1") (pintype "passive"))
      (node (ref "Q13") (pin "1") (pinfunction "B_1") (pintype "input"))
      (node (ref "R68") (pin "2") (pinfunction "2_2") (pintype "passive"))
      (node (ref "R75") (pin "2") (pinfunction "2_2") (pintype "passive"))
    )
    (net (code "274") (name "Net-(Q14-B)") (class "Default")
      (node (ref "C110") (pin "2") (pintype "passive"))
      (node (ref "Q14") (pin "1") (pinfunction "B_1") (pintype "input"))
      (node (ref "R177") (pin "1") (pinfunction "1_1") (pintype "passive"))
      (node (ref "R178") (pin "2") (pinfunction "2_2") (pintype "passive"))
    )
    (net (code "275") (name "Net-(Q14-C)") (class "Default")
      (node (ref "Q14") (pin "2") (pinfunction "C_2") (pintype "input"))
      (node (ref "UG17") (pin "2") (pintype "passive"))
    )
    (net (code "276") (name "Net-(Q15-G)") (class "Default")
      (node (ref "Q15") (pin "1") (pinfunction "G_1") (pintype "passive"))
      (node (ref "R183") (pin "2") (pinfunction "2_2") (pintype "passive"))
    )
    (net (code "277") (name "Net-(Q16-B)") (class "Default")
      (node (ref "C111") (pin "2") (pintype "passive"))
      (node (ref "Q16") (pin "1") (pinfunction "B_1") (pintype "input"))
      (node (ref "R184") (pin "1") (pinfunction "1_1") (pintype "passive"))
      (node (ref "R185") (pin "2") (pinfunction "2_2") (pintype "passive"))
    )
    (net (code "278") (name "Net-(Q16-C)") (class "Default")
      (node (ref "Q16") (pin "2") (pinfunction "C_2") (pintype "input"))
      (node (ref "UG18") (pin "2") (pintype "passive"))
    )
    (net (code "279") (name "Net-(Q17-G)") (class "Default")
      (node (ref "Q17") (pin "1") (pinfunction "G_1") (pintype "passive"))
      (node (ref "R187") (pin "2") (pinfunction "2_2") (pintype "passive"))
    )
    (net (code "280") (name "Net-(Q18-B)") (class "Default")
      (node (ref "C54") (pin "2") (pinfunction "2_2") (pintype "passive"))
      (node (ref "Q18") (pin "1") (pinfunction "B_1") (pintype "input"))
      (node (ref "R70") (pin "2") (pinfunction "2_2") (pintype "passive"))
      (node (ref "R74") (pin "2") (pinfunction "2_2") (pintype "passive"))
    )
    (net (code "281") (name "Net-(Q19-B)") (class "Default")
      (node (ref "C55") (pin "2") (pinfunction "2_2") (pintype "passive"))
      (node (ref "Q19") (pin "1") (pinfunction "B_1") (pintype "input"))
      (node (ref "R134") (pin "2") (pinfunction "2_2") (pintype "passive"))
      (node (ref "R69") (pin "2") (pinfunction "2_2") (pintype "passive"))
    )
    (net (code "282") (name "Net-(Q20-B)") (class "Default")
      (node (ref "C75") (pin "2") (pinfunction "2_2") (pintype "passive"))
      (node (ref "Q20") (pin "1") (pinfunction "B_1") (pintype "input"))
      (node (ref "R133") (pin "2") (pinfunction "2_2") (pintype "passive"))
      (node (ref "R136") (pin "2") (pinfunction "2_2") (pintype "passive"))
    )
    (net (code "283") (name "Net-(Q21-B)") (class "Default")
      (node (ref "C126") (pin "1") (pintype "passive"))
      (node (ref "Q21") (pin "1") (pinfunction "B_1") (pintype "input"))
      (node (ref "R144") (pin "2") (pinfunction "2_2") (pintype "passive"))
      (node (ref "R145") (pin "2") (pinfunction "2_2") (pintype "passive"))
    )
    (net (code "284") (name "Net-(Q22-B)") (class "Default")
      (node (ref "C70") (pin "2") (pinfunction "2_2") (pintype "passive"))
      (node (ref "Q22") (pin "1") (pinfunction "B_1") (pintype "input"))
      (node (ref "R146") (pin "2") (pinfunction "2_2") (pintype "passive"))
      (node (ref "R97") (pin "2") (pinfunction "2_2") (pintype "passive"))
    )
    (net (code "285") (name "Net-(Q23-B)") (class "Default")
      (node (ref "C123") (pin "2") (pinfunction "2_2") (pintype "passive"))
      (node (ref "Q23") (pin "1") (pinfunction "B_1") (pintype "input"))
      (node (ref "R149") (pin "2") (pinfunction "2_2") (pintype "passive"))
      (node (ref "R73") (pin "2") (pinfunction "2_2") (pintype "passive"))
    )
    (net (code "286") (name "Net-(Q24-B)") (class "Default")
      (node (ref "C122") (pin "1") (pintype "passive"))
      (node (ref "Q24") (pin "1") (pinfunction "B_1") (pintype "input"))
      (node (ref "R156") (pin "2") (pinfunction "2_2") (pintype "passive"))
      (node (ref "R157") (pin "2") (pinfunction "2_2") (pintype "passive"))
    )
    (net (code "287") (name "Net-(Q25-B)") (class "Default")
      (node (ref "C130") (pin "2") (pinfunction "2_2") (pintype "passive"))
      (node (ref "Q25") (pin "1") (pinfunction "B_1") (pintype "input"))
      (node (ref "R159") (pin "2") (pinfunction "2_2") (pintype "passive"))
      (node (ref "R160") (pin "2") (pinfunction "2_2") (pintype "passive"))
    )
    (net (code "288") (name "Net-(Q26-B)") (class "Default")
      (node (ref "C129") (pin "2") (pinfunction "2_2") (pintype "passive"))
      (node (ref "Q26") (pin "1") (pinfunction "B_1") (pintype "input"))
      (node (ref "R162") (pin "2") (pinfunction "2_2") (pintype "passive"))
      (node (ref "R163") (pin "2") (pinfunction "2_2") (pintype "passive"))
    )
    (net (code "289") (name "Net-(Q27-B)") (class "Default")
      (node (ref "C149") (pin "2") (pinfunction "2_2") (pintype "passive"))
      (node (ref "Q27") (pin "1") (pinfunction "B_1") (pintype "input"))
      (node (ref "R222") (pin "2") (pinfunction "2_2") (pintype "passive"))
      (node (ref "R223") (pin "2") (pinfunction "2_2") (pintype "passive"))
    )
    (net (code "290") (name "Net-(Q28-B)") (class "Default")
      (node (ref "Q28") (pin "1") (pinfunction "B_1") (pintype "input"))
      (node (ref "R110") (pin "1") (pintype "passive"))
    )
    (net (code "291") (name "Net-(R1-Pad1)") (class "Default")
      (node (ref "R1") (pin "1") (pintype "passive"))
      (node (ref "R4") (pin "2") (pintype "passive"))
    )
    (net (code "292") (name "Net-(R10-Pad2)") (class "Default")
      (node (ref "R10") (pin "2") (pintype "passive"))
      (node (ref "TVS1") (pin "1") (pintype "passive"))
    )
    (net (code "293") (name "Net-(R24-Pad2)") (class "Default")
      (node (ref "R24") (pin "2") (pintype "passive"))
      (node (ref "TVS3") (pin "1") (pintype "passive"))
    )
    (net (code "294") (name "Net-(R179-Pad1)") (class "Default")
      (node (ref "R179") (pin "1") (pinfunction "1_1") (pintype "passive"))
      (node (ref "R183") (pin "1") (pinfunction "1_1") (pintype "passive"))
      (node (ref "UG17") (pin "4") (pintype "passive"))
    )
    (net (code "295") (name "Net-(R186-Pad1)") (class "Default")
      (node (ref "R186") (pin "1") (pinfunction "1_1") (pintype "passive"))
      (node (ref "R187") (pin "1") (pinfunction "1_1") (pintype "passive"))
      (node (ref "UG18") (pin "4") (pintype "passive"))
    )
    (net (code "296") (name "Net-(SW1-COMMON)") (class "Default")
      (node (ref "C24") (pin "2") (pinfunction "2_2") (pintype "passive"))
      (node (ref "R18") (pin "1") (pinfunction "1_1") (pintype "passive"))
      (node (ref "SW1") (pin "1") (pinfunction "COMMON_1") (pintype "passive"))
      (node (ref "SW3") (pin "1") (pinfunction "1_1") (pintype "passive"))
      (node (ref "U5") (pin "1") (pinfunction "~{MR}_1") (pintype "passive"))
    )
    (net (code "297") (name "Net-(SW1-NO)") (class "Default")
      (node (ref "SW1") (pin "2") (pinfunction "NO_2") (pintype "passive"))
      (node (ref "U5") (pin "8") (pinfunction "~{WDO}_8") (pintype "passive"))
    )
    (net (code "298") (name "Net-(U1-BS)") (class "Default")
      (node (ref "C17") (pin "2") (pintype "passive"))
      (node (ref "U1") (pin "1") (pinfunction "BS_1") (pintype "passive"))
    )
    (net (code "299") (name "Net-(U1-FB)") (class "Default")
      (node (ref "R1") (pin "2") (pintype "passive"))
      (node (ref "R5") (pin "1") (pintype "passive"))
      (node (ref "U1") (pin "5") (pinfunction "FB_5") (pintype "passive"))
    )
    (net (code "300") (name "Net-(U1-comp)") (class "Default")
      (node (ref "C21") (pin "1") (pintype "passive"))
      (node (ref "U1") (pin "6") (pinfunction "comp_6") (pintype "passive"))
    )
    (net (code "301") (name "Net-(U2-Adj)") (class "Default")
      (node (ref "R3") (pin "1") (pinfunction "1_1") (pintype "passive"))
      (node (ref "R6") (pin "2") (pinfunction "2_2") (pintype "passive"))
      (node (ref "U2") (pin "5") (pinfunction "Adj_5") (pintype "passive"))
    )
    (net (code "302") (name "Net-(U2-EN)") (class "Default")
      (node (ref "R2") (pin "2") (pinfunction "2_2") (pintype "passive"))
      (node (ref "U2") (pin "1") (pinfunction "EN_1") (pintype "passive"))
    )
    (net (code "303") (name "Net-(U4-CANH{slash}485B)") (class "Default")
      (node (ref "R14") (pin "1") (pintype "passive"))
      (node (ref "U4") (pin "8") (pinfunction "CANH/485B_8") (pintype "passive"))
    )
    (net (code "304") (name "Net-(U4-CANL{slash}485A)") (class "Default")
      (node (ref "R11") (pin "1") (pintype "passive"))
      (node (ref "U4") (pin "9") (pinfunction "CANL/485A_9") (pintype "passive"))
    )
    (net (code "305") (name "Net-(U4-RG)") (class "Default")
      (node (ref "R10") (pin "1") (pintype "passive"))
      (node (ref "U4") (pin "10") (pinfunction "RG_10") (pintype "passive"))
    )
    (net (code "306") (name "Net-(U4-RXD)") (class "Default")
      (node (ref "R13") (pin "2") (pintype "passive"))
      (node (ref "U4") (pin "4") (pinfunction "RXD_4") (pintype "passive"))
    )
    (net (code "307") (name "Net-(U4-TXD)") (class "Default")
      (node (ref "R12") (pin "2") (pintype "passive"))
      (node (ref "U4") (pin "3") (pinfunction "TXD_3") (pintype "passive"))
    )
    (net (code "308") (name "Net-(U5-~{RST})") (class "Default")
      (node (ref "C27") (pin "2") (pinfunction "2_2") (pintype "passive"))
      (node (ref "R20") (pin "2") (pinfunction "2_2") (pintype "passive"))
      (node (ref "R27") (pin "1") (pinfunction "1_1") (pintype "passive"))
      (node (ref "U5") (pin "7") (pinfunction "~{RST}_7") (pintype "passive"))
    )
    (net (code "309") (name "Net-(U6-CANH{slash}485B)") (class "Default")
      (node (ref "R35") (pin "1") (pintype "passive"))
      (node (ref "U6") (pin "8") (pinfunction "CANH/485B_8") (pintype "passive"))
    )
    (net (code "310") (name "Net-(U6-CANL{slash}485A)") (class "Default")
      (node (ref "R28") (pin "1") (pintype "passive"))
      (node (ref "U6") (pin "9") (pinfunction "CANL/485A_9") (pintype "passive"))
    )
    (net (code "311") (name "Net-(U6-RG)") (class "Default")
      (node (ref "R24") (pin "1") (pintype "passive"))
      (node (ref "U6") (pin "10") (pinfunction "RG_10") (pintype "passive"))
    )
    (net (code "312") (name "Net-(U6-RXD)") (class "Default")
      (node (ref "R34") (pin "2") (pintype "passive"))
      (node (ref "U6") (pin "4") (pinfunction "RXD_4") (pintype "passive"))
    )
    (net (code "313") (name "Net-(U6-TXD)") (class "Default")
      (node (ref "R32") (pin "2") (pintype "passive"))
      (node (ref "U6") (pin "3") (pinfunction "TXD_3") (pintype "passive"))
    )
    (net (code "314") (name "Net-(U7-C-)") (class "Default")
      (node (ref "C31") (pin "1") (pintype "passive"))
      (node (ref "U7") (pin "3") (pinfunction "C-_3") (pintype "passive"))
    )
    (net (code "315") (name "Net-(U7-C1+)") (class "Default")
      (node (ref "C31") (pin "2") (pintype "passive"))
      (node (ref "U7") (pin "1") (pinfunction "C1+_1") (pintype "passive"))
    )
    (net (code "316") (name "Net-(U7-C2+)") (class "Default")
      (node (ref "C36") (pin "2") (pintype "passive"))
      (node (ref "U7") (pin "4") (pinfunction "C2+_4") (pintype "passive"))
    )
    (net (code "317") (name "Net-(U7-C2-)") (class "Default")
      (node (ref "C36") (pin "1") (pintype "passive"))
      (node (ref "U7") (pin "5") (pinfunction "C2-_5") (pintype "passive"))
    )
    (net (code "318") (name "Net-(U7-R1IN)") (class "Default")
      (node (ref "R138") (pin "1") (pintype "passive"))
      (node (ref "U7") (pin "13") (pinfunction "R1IN_13") (pintype "passive"))
    )
    (net (code "319") (name "Net-(U7-R1OUT)") (class "Default")
      (node (ref "R40") (pin "2") (pintype "passive"))
      (node (ref "U7") (pin "12") (pinfunction "R1OUT_12") (pintype "passive"))
    )
    (net (code "320") (name "Net-(U7-R2IN)") (class "Default")
      (node (ref "R37") (pin "1") (pintype "passive"))
      (node (ref "U7") (pin "8") (pinfunction "R2IN_8") (pintype "passive"))
    )
    (net (code "321") (name "Net-(U7-R2OUT)") (class "Default")
      (node (ref "R42") (pin "2") (pintype "passive"))
      (node (ref "U7") (pin "9") (pinfunction "R2OUT_9") (pintype "passive"))
    )
    (net (code "322") (name "Net-(U7-T1IN)") (class "Default")
      (node (ref "R43") (pin "2") (pintype "passive"))
      (node (ref "U7") (pin "11") (pinfunction "T1IN_11") (pintype "passive"))
    )
    (net (code "323") (name "Net-(U7-T1OUT)") (class "Default")
      (node (ref "R139") (pin "1") (pintype "passive"))
      (node (ref "U7") (pin "14") (pinfunction "T1OUT_14") (pintype "passive"))
    )
    (net (code "324") (name "Net-(U7-T2IN)") (class "Default")
      (node (ref "R44") (pin "2") (pintype "passive"))
      (node (ref "U7") (pin "10") (pinfunction "T2IN_10") (pintype "passive"))
    )
    (net (code "325") (name "Net-(U7-T2OUT)") (class "Default")
      (node (ref "R45") (pin "1") (pintype "passive"))
      (node (ref "U7") (pin "7") (pinfunction "T2OUT_7") (pintype "passive"))
    )
    (net (code "326") (name "Net-(U7-V+)") (class "Default")
      (node (ref "C32") (pin "1") (pintype "passive"))
      (node (ref "U7") (pin "2") (pinfunction "V+_2") (pintype "passive"))
    )
    (net (code "327") (name "Net-(U7-V-)") (class "Default")
      (node (ref "C37") (pin "2") (pintype "passive"))
      (node (ref "U7") (pin "6") (pinfunction "V-_6") (pintype "passive"))
    )
    (net (code "328") (name "Net-(U8-RG)") (class "Default")
      (node (ref "C30") (pin "2") (pinfunction "2_2") (pintype "passive"))
      (node (ref "R36") (pin "2") (pinfunction "2_2") (pintype "passive"))
      (node (ref "U8") (pin "8") (pinfunction "RG_8") (pintype "passive"))
    )
    (net (code "329") (name "Net-(U9-RG)") (class "Default")
      (node (ref "C38") (pin "1") (pinfunction "1_1") (pintype "passive"))
      (node (ref "R46") (pin "1") (pinfunction "1_1") (pintype "passive"))
      (node (ref "U9") (pin "8") (pinfunction "RG_8") (pintype "passive"))
    )
    (net (code "330") (name "Net-(U10-~{HOLD})") (class "Default")
      (node (ref "R47") (pin "2") (pinfunction "2_2") (pintype "passive"))
      (node (ref "U10") (pin "7") (pinfunction "~{HOLD}_7") (pintype "passive"))
    )
    (net (code "331") (name "Net-(U10-~{WP})") (class "Default")
      (node (ref "R54") (pin "2") (pinfunction "2_2") (pintype "passive"))
      (node (ref "U10") (pin "3") (pinfunction "~{WP}_3") (pintype "passive"))
    )
    (net (code "332") (name "Net-(U11-R)") (class "Default")
      (node (ref "R57") (pin "1") (pinfunction "1_1") (pintype "passive"))
      (node (ref "R58") (pin "2") (pinfunction "2_2") (pintype "passive"))
      (node (ref "U11") (pin "1") (pinfunction "R_1") (pintype "passive"))
    )
    (net (code "333") (name "Net-(U15-I{slash}O1)") (class "Default")
      (node (ref "J12") (pin "2") (pinfunction "2_2") (pintype "passive"))
      (node (ref "R216") (pin "1") (pinfunction "1_1") (pintype "passive"))
      (node (ref "R218") (pin "2") (pinfunction "2_2") (pintype "passive"))
      (node (ref "U15") (pin "2") (pinfunction "I/O1_2") (pintype "passive"))
    )
    (net (code "334") (name "Net-(U15-I{slash}O2)") (class "Default")
      (node (ref "J12") (pin "3") (pinfunction "3_3") (pintype "passive"))
      (node (ref "R217") (pin "1") (pinfunction "1_1") (pintype "passive"))
      (node (ref "R219") (pin "2") (pinfunction "2_2") (pintype "passive"))
      (node (ref "U15") (pin "3") (pinfunction "I/O2_3") (pintype "passive"))
    )
    (net (code "335") (name "Net-(U15-VCC)") (class "Default")
      (node (ref "F1") (pin "2") (pinfunction "2_2") (pintype "passive"))
      (node (ref "J12") (pin "1") (pinfunction "1_1") (pintype "passive"))
      (node (ref "U15") (pin "4") (pinfunction "VCC_4") (pintype "passive"))
    )
    (net (code "336") (name "Net-(U37-C)") (class "Default")
      (node (ref "R196") (pin "1") (pintype "passive"))
      (node (ref "R197") (pin "2") (pinfunction "2_2") (pintype "passive"))
      (node (ref "R198") (pin "2") (pinfunction "2_2") (pintype "passive"))
      (node (ref "U37") (pin "1") (pinfunction "R_1") (pintype "passive"))
      (node (ref "U37") (pin "3") (pinfunction "C_3") (pintype "passive"))
    )
    (net (code "337") (name "Net-(U38-C)") (class "Default")
      (node (ref "R201") (pin "1") (pintype "passive"))
      (node (ref "R202") (pin "2") (pinfunction "2_2") (pintype "passive"))
      (node (ref "R203") (pin "2") (pinfunction "2_2") (pintype "passive"))
      (node (ref "U38") (pin "1") (pinfunction "R_1") (pintype "passive"))
      (node (ref "U38") (pin "3") (pinfunction "C_3") (pintype "passive"))
    )
    (net (code "338") (name "Net-(U40-C)") (class "Default")
      (node (ref "R206") (pin "1") (pintype "passive"))
      (node (ref "R207") (pin "2") (pinfunction "2_2") (pintype "passive"))
      (node (ref "R208") (pin "2") (pinfunction "2_2") (pintype "passive"))
      (node (ref "U40") (pin "1") (pinfunction "R_1") (pintype "passive"))
      (node (ref "U40") (pin "3") (pinfunction "C_3") (pintype "passive"))
    )
    (net (code "339") (name "Net-(U41-C)") (class "Default")
      (node (ref "R211") (pin "1") (pintype "passive"))
      (node (ref "R212") (pin "2") (pinfunction "2_2") (pintype "passive"))
      (node (ref "R213") (pin "2") (pinfunction "2_2") (pintype "passive"))
      (node (ref "U41") (pin "1") (pinfunction "R_1") (pintype "passive"))
      (node (ref "U41") (pin "3") (pinfunction "C_3") (pintype "passive"))
    )
    (net (code "340") (name "Net-(U43A-IN-)") (class "Default")
      (node (ref "R199") (pin "2") (pinfunction "2_2") (pintype "passive"))
      (node (ref "U43") (pin "1") (pinfunction "OUT_1") (pintype "passive"))
      (node (ref "U43") (pin "2") (pinfunction "IN-_2") (pintype "passive"))
    )
    (net (code "341") (name "Net-(U43B-IN-)") (class "Default")
      (node (ref "R204") (pin "2") (pinfunction "2_2") (pintype "passive"))
      (node (ref "U43") (pin "6") (pinfunction "IN-_6") (pintype "passive"))
      (node (ref "U43") (pin "7") (pinfunction "OUT_7") (pintype "passive"))
    )
    (net (code "342") (name "Net-(U44A-IN-)") (class "Default")
      (node (ref "R209") (pin "2") (pinfunction "2_2") (pintype "passive"))
      (node (ref "U44") (pin "1") (pinfunction "OUT_1") (pintype "passive"))
      (node (ref "U44") (pin "2") (pinfunction "IN-_2") (pintype "passive"))
    )
    (net (code "343") (name "Net-(U44B-IN-)") (class "Default")
      (node (ref "R214") (pin "2") (pinfunction "2_2") (pintype "passive"))
      (node (ref "U44") (pin "6") (pinfunction "IN-_6") (pintype "passive"))
      (node (ref "U44") (pin "7") (pinfunction "OUT_7") (pintype "passive"))
    )
    (net (code "344") (name "PE") (class "Default")
      (node (ref "C154") (pin "2") (pinfunction "2_2") (pintype "passive"))
    )
    (net (code "345") (name "SGND") (class "Default")
      (node (ref "C112") (pin "2") (pintype "passive"))
      (node (ref "C113") (pin "2") (pintype "passive"))
      (node (ref "J1") (pin "11") (pinfunction "11_11") (pintype "passive"))
      (node (ref "J5") (pin "1") (pinfunction "1_1") (pintype "passive"))
      (node (ref "J5") (pin "12") (pinfunction "12_12") (pintype "passive"))
      (node (ref "JP2") (pin "1") (pinfunction "1_1") (pintype "passive"))
      (node (ref "JP2") (pin "5") (pinfunction "5_5") (pintype "passive"))
      (node (ref "UG17") (pin "3") (pintype "passive"))
      (node (ref "UG18") (pin "3") (pintype "passive"))
    )
    (net (code "346") (name "VA3.3") (class "Default")
      (node (ref "C42") (pin "1") (pintype "passive"))
      (node (ref "C43") (pin "1") (pintype "passive"))
      (node (ref "C44") (pin "1") (pinfunction "1_1") (pintype "passive"))
      (node (ref "Q2") (pin "3") (pinfunction "E_3") (pintype "input"))
      (node (ref "R57") (pin "2") (pinfunction "2_2") (pintype "passive"))
      (node (ref "U3") (pin "14") (pinfunction "VDDA_14") (pintype "bidirectional"))
      (node (ref "U3") (pin "17") (pinfunction "VREFP_17") (pintype "bidirectional"))
    )
    (net (code "347") (name "VDD5V") (class "Default")
      (node (ref "C19") (pin "2") (pintype "passive"))
      (node (ref "C20") (pin "2") (pintype "passive"))
      (node (ref "DC2") (pin "1") (pinfunction "1_1") (pintype "passive"))
      (node (ref "F1") (pin "1") (pinfunction "1_1") (pintype "passive"))
      (node (ref "J10") (pin "3") (pinfunction "3_3") (pintype "passive"))
      (node (ref "J6") (pin "12") (pinfunction "12_12") (pintype "passive"))
      (node (ref "L1") (pin "2") (pinfunction "2_2") (pintype "passive"))
      (node (ref "Q2") (pin "2") (pinfunction "C_2") (pintype "input"))
      (node (ref "R2") (pin "1") (pinfunction "1_1") (pintype "passive"))
      (node (ref "R220") (pin "2") (pintype "passive"))
      (node (ref "R4") (pin "1") (pintype "passive"))
      (node (ref "R55") (pin "2") (pinfunction "2_2") (pintype "passive"))
      (node (ref "U2") (pin "2") (pinfunction "Vin_2") (pintype "passive"))
    )
    (net (code "348") (name "VDD12V") (class "Default")
      (node (ref "C106") (pin "2") (pinfunction "2_2") (pintype "passive"))
      (node (ref "C107") (pin "2") (pinfunction "2_2") (pintype "passive"))
      (node (ref "C124") (pin "2") (pinfunction "2_2") (pintype "passive"))
      (node (ref "C125") (pin "2") (pinfunction "2_2") (pintype "passive"))
      (node (ref "C127") (pin "2") (pinfunction "2_2") (pintype "passive"))
      (node (ref "C128") (pin "2") (pinfunction "2_2") (pintype "passive"))
      (node (ref "C131") (pin "2") (pinfunction "2_2") (pintype "passive"))
      (node (ref "C148") (pin "2") (pinfunction "2_2") (pintype "passive"))
      (node (ref "C18") (pin "2") (pintype "passive"))
      (node (ref "C49") (pin "1") (pintype "passive"))
      (node (ref "C50") (pin "1") (pintype "passive"))
      (node (ref "C51") (pin "2") (pinfunction "2_2") (pintype "passive"))
      (node (ref "C52") (pin "2") (pinfunction "2_2") (pintype "passive"))
      (node (ref "C58") (pin "1") (pintype "passive"))
      (node (ref "C59") (pin "1") (pintype "passive"))
      (node (ref "C60") (pin "2") (pinfunction "2_2") (pintype "passive"))
      (node (ref "C79") (pin "1") (pintype "passive"))
      (node (ref "C84") (pin "2") (pinfunction "2_2") (pintype "passive"))
      (node (ref "C85") (pin "2") (pinfunction "2_2") (pintype "passive"))
      (node (ref "C86") (pin "2") (pinfunction "2_2") (pintype "passive"))
      (node (ref "C93") (pin "1") (pintype "passive"))
      (node (ref "C95") (pin "2") (pinfunction "2_2") (pintype "passive"))
      (node (ref "D1") (pin "2") (pinfunction "K_2") (pintype "passive"))
      (node (ref "D12") (pin "2") (pinfunction "K_2") (pintype "passive"))
      (node (ref "D13") (pin "2") (pinfunction "K_2") (pintype "passive"))
      (node (ref "D14") (pin "2") (pinfunction "K_2") (pintype "passive"))
      (node (ref "D15") (pin "2") (pinfunction "K_2") (pintype "passive"))
      (node (ref "D16") (pin "2") (pinfunction "K_2") (pintype "passive"))
      (node (ref "D17") (pin "2") (pinfunction "K_2") (pintype "passive"))
      (node (ref "D18") (pin "2") (pinfunction "K_2") (pintype "passive"))
      (node (ref "D19") (pin "2") (pinfunction "K_2") (pintype "passive"))
      (node (ref "D2") (pin "2") (pinfunction "K_2") (pintype "passive"))
      (node (ref "D20") (pin "2") (pinfunction "K_2") (pintype "passive"))
      (node (ref "D21") (pin "2") (pinfunction "K_2") (pintype "passive"))
      (node (ref "D22") (pin "2") (pinfunction "K_2") (pintype "passive"))
      (node (ref "D23") (pin "2") (pinfunction "K_2") (pintype "passive"))
      (node (ref "D24") (pin "2") (pinfunction "K_2") (pintype "passive"))
      (node (ref "D25") (pin "2") (pinfunction "K_2") (pintype "passive"))
      (node (ref "D26") (pin "2") (pinfunction "K_2") (pintype "passive"))
      (node (ref "D27") (pin "2") (pinfunction "K_2") (pintype "passive"))
      (node (ref "D28") (pin "2") (pinfunction "K_2") (pintype "passive"))
      (node (ref "D29") (pin "2") (pinfunction "K_2") (pintype "passive"))
      (node (ref "D30") (pin "2") (pinfunction "K_2") (pintype "passive"))
      (node (ref "D31") (pin "2") (pinfunction "K_2") (pintype "passive"))
      (node (ref "D32") (pin "2") (pinfunction "K_2") (pintype "passive"))
      (node (ref "DC1") (pin "1") (pinfunction "1_1") (pintype "passive"))
      (node (ref "J10") (pin "1") (pinfunction "1_1") (pintype "passive"))
      (node (ref "J6") (pin "8") (pinfunction "8_8") (pintype "passive"))
      (node (ref "R121") (pin "2") (pinfunction "2_2") (pintype "passive"))
      (node (ref "R122") (pin "2") (pinfunction "2_2") (pintype "passive"))
      (node (ref "R131") (pin "2") (pinfunction "2_2") (pintype "passive"))
      (node (ref "R132") (pin "2") (pinfunction "2_2") (pintype "passive"))
      (node (ref "R135") (pin "2") (pinfunction "2_2") (pintype "passive"))
      (node (ref "R143") (pin "2") (pinfunction "2_2") (pintype "passive"))
      (node (ref "R147") (pin "2") (pinfunction "2_2") (pintype "passive"))
      (node (ref "R155") (pin "2") (pinfunction "2_2") (pintype "passive"))
      (node (ref "R158") (pin "2") (pinfunction "2_2") (pintype "passive"))
      (node (ref "R161") (pin "2") (pinfunction "2_2") (pintype "passive"))
      (node (ref "R221") (pin "2") (pinfunction "2_2") (pintype "passive"))
      (node (ref "R60") (pin "2") (pinfunction "2_2") (pintype "passive"))
      (node (ref "R61") (pin "2") (pinfunction "2_2") (pintype "passive"))
      (node (ref "R62") (pin "2") (pinfunction "2_2") (pintype "passive"))
      (node (ref "R63") (pin "2") (pinfunction "2_2") (pintype "passive"))
      (node (ref "R64") (pin "2") (pinfunction "2_2") (pintype "passive"))
      (node (ref "R81") (pin "2") (pinfunction "2_2") (pintype "passive"))
      (node (ref "R93") (pin "2") (pinfunction "2_2") (pintype "passive"))
      (node (ref "R94") (pin "2") (pinfunction "2_2") (pintype "passive"))
      (node (ref "R95") (pin "2") (pinfunction "2_2") (pintype "passive"))
      (node (ref "R96") (pin "2") (pinfunction "2_2") (pintype "passive"))
      (node (ref "RL1") (pin "2") (pinfunction "-_2") (pintype "passive"))
      (node (ref "RL10") (pin "2") (pinfunction "-_2") (pintype "passive"))
      (node (ref "RL11") (pin "2") (pinfunction "-_2") (pintype "passive"))
      (node (ref "RL12") (pin "2") (pinfunction "-_2") (pintype "passive"))
      (node (ref "RL13") (pin "2") (pinfunction "-_2") (pintype "passive"))
      (node (ref "RL14") (pin "2") (pinfunction "-_2") (pintype "passive"))
      (node (ref "RL15") (pin "2") (pinfunction "-_2") (pintype "passive"))
      (node (ref "RL16") (pin "2") (pinfunction "-_2") (pintype "passive"))
      (node (ref "RL17") (pin "2") (pinfunction "-_2") (pintype "passive"))
      (node (ref "RL18") (pin "2") (pinfunction "-_2") (pintype "passive"))
      (node (ref "RL19") (pin "2") (pinfunction "-_2") (pintype "passive"))
      (node (ref "RL2") (pin "2") (pinfunction "-_2") (pintype "passive"))
      (node (ref "RL20") (pin "2") (pinfunction "-_2") (pintype "passive"))
      (node (ref "RL21") (pin "2") (pinfunction "-_2") (pintype "passive"))
      (node (ref "RL3") (pin "2") (pinfunction "-_2") (pintype "passive"))
      (node (ref "RL4") (pin "2") (pinfunction "-_2") (pintype "passive"))
      (node (ref "RL5") (pin "2") (pinfunction "-_2") (pintype "passive"))
      (node (ref "RL6") (pin "2") (pinfunction "-_2") (pintype "passive"))
      (node (ref "RL7") (pin "2") (pinfunction "-_2") (pintype "passive"))
      (node (ref "RL8") (pin "2") (pinfunction "-_2") (pintype "passive"))
      (node (ref "RL9") (pin "2") (pinfunction "-_2") (pintype "passive"))
      (node (ref "U1") (pin "2") (pinfunction "Vi_2") (pintype "passive"))
      (node (ref "U1") (pin "7") (pinfunction "EN_7") (pintype "passive"))
    )
    (net (code "349") (name "unconnected-(J12-Pad5)") (class "Default")
      (node (ref "J12") (pin "5") (pinfunction "5_5") (pintype "passive"))
    )
    (net (code "350") (name "unconnected-(J13-Pad9)") (class "Default")
      (node (ref "J13") (pin "9") (pinfunction "9_9") (pintype "passive"))
    )
    (net (code "351") (name "unconnected-(J13-Pad10)") (class "Default")
      (node (ref "J13") (pin "10") (pinfunction "10_10") (pintype "passive"))
    )
    (net (code "352") (name "unconnected-(MAKE1-Pad1)") (class "Default")
      (node (ref "MAKE1") (pin "1") (pinfunction "1_1") (pintype "passive"))
    )
    (net (code "353") (name "unconnected-(MARKE1-Pad1)") (class "Default")
      (node (ref "MARKE1") (pin "1") (pinfunction "1_1") (pintype "passive"))
    )
    (net (code "354") (name "unconnected-(MARKE3-Pad1)") (class "Default")
      (node (ref "MARKE3") (pin "1") (pinfunction "1_1") (pintype "passive"))
    )
    (net (code "355") (name "unconnected-(U1-SS-Pad8)") (class "Default")
      (node (ref "U1") (pin "8") (pinfunction "SS_8") (pintype "passive"))
    )
    (net (code "356") (name "unconnected-(U3-JTAG_TDI-Pad3)") (class "Default")
      (node (ref "U3") (pin "3") (pinfunction "JTAG_TDI_3") (pintype "bidirectional"))
    )
    (net (code "357") (name "unconnected-(U3-JTAG_TRST-Pad5)") (class "Default")
      (node (ref "U3") (pin "5") (pinfunction "JTAG_TRST_5") (pintype "bidirectional"))
    )
    (net (code "358") (name "unconnected-(U3-P0[0]{slash}CAN_RD1{slash}U3_TXD{slash}I2C1_SDA{slash}U0_TXD-Pad66)") (class "Default")
      (node (ref "U3") (pin "66") (pinfunction "P0[0]/CAN_RD1/U3_TXD/I2C1_SDA/U0_TXD_66") (pintype "bidirectional"))
    )
    (net (code "359") (name "unconnected-(U3-P0[1]{slash}CAN_TD1{slash}U3_RXD{slash}I2C1_SCL{slash}U0_RXD-Pad67)") (class "Default")
      (node (ref "U3") (pin "67") (pinfunction "P0[1]/CAN_TD1/U3_RXD/I2C1_SCL/U0_RXD_67") (pintype "bidirectional"))
    )
    (net (code "360") (name "unconnected-(U3-P0[4]{slash}I2C_RX_SCK{slash}RD2{slash}T2_CAP0-Pad116)") (class "Default")
      (node (ref "U3") (pin "116") (pinfunction "P0[4]/I2C_RX_SCK/RD2/T2_CAP0_116") (pintype "bidirectional"))
    )
    (net (code "361") (name "unconnected-(U3-P0[5]{slash}I2S_RX_WS{slash}TD2{slash}T2CAP1-Pad115)") (class "Default")
      (node (ref "U3") (pin "115") (pinfunction "P0[5]/I2S_RX_WS/TD2/T2CAP1_115") (pintype "bidirectional"))
    )
    (net (code "362") (name "unconnected-(U3-P0[13]{slash}USB_UP_LED2{slash}SSP1_MOSI{slash}ADC0_IN7-Pad32)") (class "Default")
      (node (ref "U3") (pin "32") (pinfunction "P0[13]/USB_UP_LED2/SSP1_MOSI/ADC0_IN7_32") (pintype "bidirectional"))
    )
    (net (code "363") (name "unconnected-(U3-P0[28]{slash}I2C0_SCL{slash}USB_SCL1-Pad34)") (class "Default")
      (node (ref "U3") (pin "34") (pinfunction "P0[28]/I2C0_SCL/USB_SCL1_34") (pintype "bidirectional"))
    )
    (net (code "364") (name "unconnected-(U3-P1[0]{slash}ENET_TXD0{slash}T3_CAP1{slash}SSP2_SCK-Pad136)") (class "Default")
      (node (ref "U3") (pin "136") (pinfunction "P1[0]/ENET_TXD0/T3_CAP1/SSP2_SCK_136") (pintype "bidirectional"))
    )
    (net (code "365") (name "unconnected-(U3-P1[1]{slash}ENET_TXD1{slash}T3_MAT3{slash}SSP2_MOSI-Pad135)") (class "Default")
      (node (ref "U3") (pin "135") (pinfunction "P1[1]/ENET_TXD1/T3_MAT3/SSP2_MOSI_135") (pintype "bidirectional"))
    )
    (net (code "366") (name "unconnected-(U3-P1[4]{slash}ENET_TX_EN{slash}T3_MAT2{slash}SSP2_MISO-Pad133)") (class "Default")
      (node (ref "U3") (pin "133") (pinfunction "P1[4]/ENET_TX_EN/T3_MAT2/SSP2_MISO_133") (pintype "bidirectional"))
    )
    (net (code "367") (name "unconnected-(U3-P1[8]{slash}ENET_CRS{slash}T3_MAT1{slash}SSP2_SSEL-Pad132)") (class "Default")
      (node (ref "U3") (pin "132") (pinfunction "P1[8]/ENET_CRS/T3_MAT1/SSP2_SSEL_132") (pintype "bidirectional"))
    )
    (net (code "368") (name "unconnected-(U3-P1[9]{slash}ENET_RXD0{slash}T3_MAT0-Pad131)") (class "Default")
      (node (ref "U3") (pin "131") (pinfunction "P1[9]/ENET_RXD0/T3_MAT0_131") (pintype "bidirectional"))
    )
    (net (code "369") (name "unconnected-(U3-P1[10]{slash}ENET_RXD1{slash}T3_CAP0-Pad129)") (class "Default")
      (node (ref "U3") (pin "129") (pinfunction "P1[10]/ENET_RXD1/T3_CAP0_129") (pintype "bidirectional"))
    )
    (net (code "370") (name "unconnected-(U3-P1[14]{slash}ENET_RX_ER{slash}T2_CAP0-Pad128)") (class "Default")
      (node (ref "U3") (pin "128") (pinfunction "P1[14]/ENET_RX_ER/T2_CAP0_128") (pintype "bidirectional"))
    )
    (net (code "371") (name "unconnected-(U3-P1[15]{slash}ENET_RX_CLK{slash}I2C2_SDA-Pad126)") (class "Default")
      (node (ref "U3") (pin "126") (pinfunction "P1[15]/ENET_RX_CLK/I2C2_SDA_126") (pintype "bidirectional"))
    )
    (net (code "372") (name "unconnected-(U3-P1[16]{slash}ENET_MDC{slash}I2S_TX_MCLK-Pad125)") (class "Default")
      (node (ref "U3") (pin "125") (pinfunction "P1[16]/ENET_MDC/I2S_TX_MCLK_125") (pintype "bidirectional"))
    )
    (net (code "373") (name "unconnected-(U3-P1[17]{slash}ENET_MDIO{slash}I2S_RX_MCLK-Pad123)") (class "Default")
      (node (ref "U3") (pin "123") (pinfunction "P1[17]/ENET_MDIO/I2S_RX_MCLK_123") (pintype "bidirectional"))
    )
    (net (code "374") (name "unconnected-(U3-P3[0]{slash}EMC_D[0]-Pad137)") (class "Default")
      (node (ref "U3") (pin "137") (pinfunction "P3[0]/EMC_D[0]_137") (pintype "bidirectional"))
    )
    (net (code "375") (name "unconnected-(U3-P3[1]{slash}EMC_D[1]-Pad140)") (class "Default")
      (node (ref "U3") (pin "140") (pinfunction "P3[1]/EMC_D[1]_140") (pintype "bidirectional"))
    )
    (net (code "376") (name "unconnected-(U3-P3[2]{slash}EMC_D[2]-Pad144)") (class "Default")
      (node (ref "U3") (pin "144") (pinfunction "P3[2]/EMC_D[2]_144") (pintype "bidirectional"))
    )
    (net (code "377") (name "unconnected-(U3-P3[3]{slash}EMC_D[3]-Pad2)") (class "Default")
      (node (ref "U3") (pin "2") (pinfunction "P3[3]/EMC_D[3]_2") (pintype "bidirectional"))
    )
    (net (code "378") (name "unconnected-(U3-P3[4]{slash}EMC_D[4]-Pad9)") (class "Default")
      (node (ref "U3") (pin "9") (pinfunction "P3[4]/EMC_D[4]_9") (pintype "bidirectional"))
    )
    (net (code "379") (name "unconnected-(U3-P3[5]{slash}EMC_D[5]-Pad12)") (class "Default")
      (node (ref "U3") (pin "12") (pinfunction "P3[5]/EMC_D[5]_12") (pintype "bidirectional"))
    )
    (net (code "380") (name "unconnected-(U3-P3[6]{slash}EMC_D[6]-Pad16)") (class "Default")
      (node (ref "U3") (pin "16") (pinfunction "P3[6]/EMC_D[6]_16") (pintype "bidirectional"))
    )
    (net (code "381") (name "unconnected-(U3-P3[7]{slash}EMC_D[7]-Pad19)") (class "Default")
      (node (ref "U3") (pin "19") (pinfunction "P3[7]/EMC_D[7]_19") (pintype "bidirectional"))
    )
    (net (code "382") (name "unconnected-(U3-P4[8]{slash}EMC_A[8]-Pad88)") (class "Default")
      (node (ref "U3") (pin "88") (pinfunction "P4[8]/EMC_A[8]_88") (pintype "bidirectional"))
    )
    (net (code "383") (name "unconnected-(U3-P4[11]{slash}EMC_A[11]-Pad101)") (class "Default")
      (node (ref "U3") (pin "101") (pinfunction "P4[11]/EMC_A[11]_101") (pintype "bidirectional"))
    )
    (net (code "384") (name "unconnected-(U3-P4[15]{slash}EMC_A[15]-Pad120)") (class "Default")
      (node (ref "U3") (pin "120") (pinfunction "P4[15]/EMC_A[15]_120") (pintype "bidirectional"))
    )
    (net (code "385") (name "unconnected-(U3-P4[24]{slash}EMC_OE-Pad127)") (class "Default")
      (node (ref "U3") (pin "127") (pinfunction "P4[24]/EMC_OE_127") (pintype "bidirectional"))
    )
    (net (code "386") (name "unconnected-(U3-P4[25]{slash}EMC_WE-Pad124)") (class "Default")
      (node (ref "U3") (pin "124") (pinfunction "P4[25]/EMC_WE_124") (pintype "bidirectional"))
    )
    (net (code "387") (name "unconnected-(U3-P5[0]{slash}EMC_A[24]{slash}SSP2_MOSI{slash}T2_MAT2-Pad6)") (class "Default")
      (node (ref "U3") (pin "6") (pinfunction "P5[0]/EMC_A[24]/SSP2_MOSI/T2_MAT2_6") (pintype "bidirectional"))
    )
    (net (code "388") (name "unconnected-(U3-P5[1]{slash}EMC_BLS3{slash}U3_RXD{slash}T2_MAT1{slash}I2C2_SCL-Pad21)") (class "Default")
      (node (ref "U3") (pin "21") (pinfunction "P5[1]/EMC_BLS3/U3_RXD/T2_MAT1/I2C2_SCL_21") (pintype "bidirectional"))
    )
    (net (code "389") (name "unconnected-(U3-P5[2]{slash}T3_MAT2{slash}I2C0{slash}SDA-Pad81)") (class "Default")
      (node (ref "U3") (pin "81") (pinfunction "P5[2]/T3_MAT2/I2C0/SDA_81") (pintype "bidirectional"))
    )
    (net (code "390") (name "unconnected-(U3-RSTOUT-Pad20)") (class "Default")
      (node (ref "U3") (pin "20") (pinfunction "RSTOUT_20") (pintype "bidirectional"))
    )
    (net (code "391") (name "unconnected-(U3-RTC_ALARM-Pad26)") (class "Default")
      (node (ref "U3") (pin "26") (pinfunction "RTC_ALARM_26") (pintype "bidirectional"))
    )
    (net (code "392") (name "unconnected-(U5-~{PFO}-Pad5)") (class "Default")
      (node (ref "U5") (pin "5") (pinfunction "~{PFO}_5") (pintype "passive+no_connect"))
    )
  )
)
